# pandashield12-lga.net
KiCad netlist of a schematic drawn in EAGLE
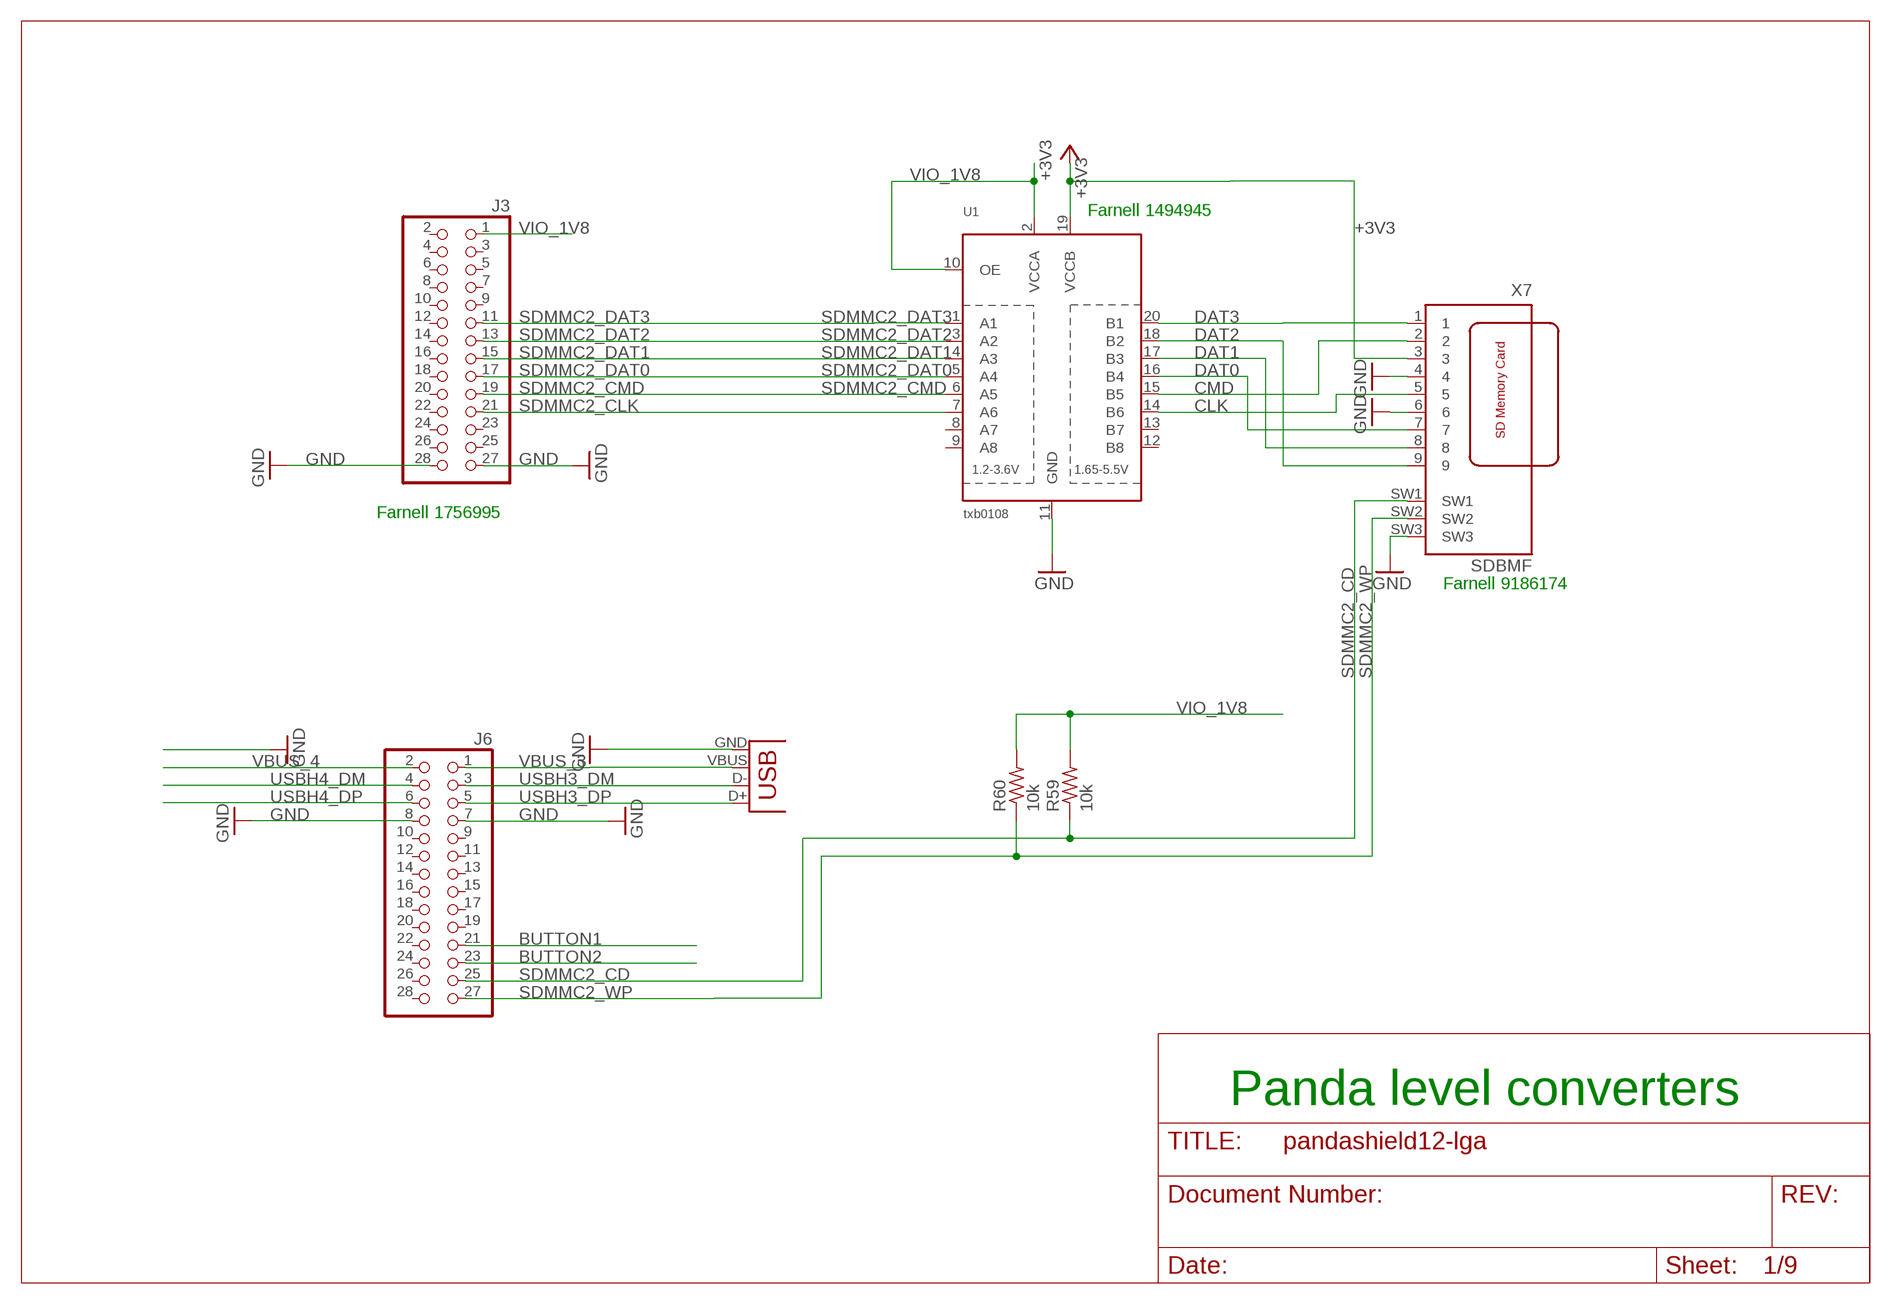
[diagram p0: schematic, sheet 1]
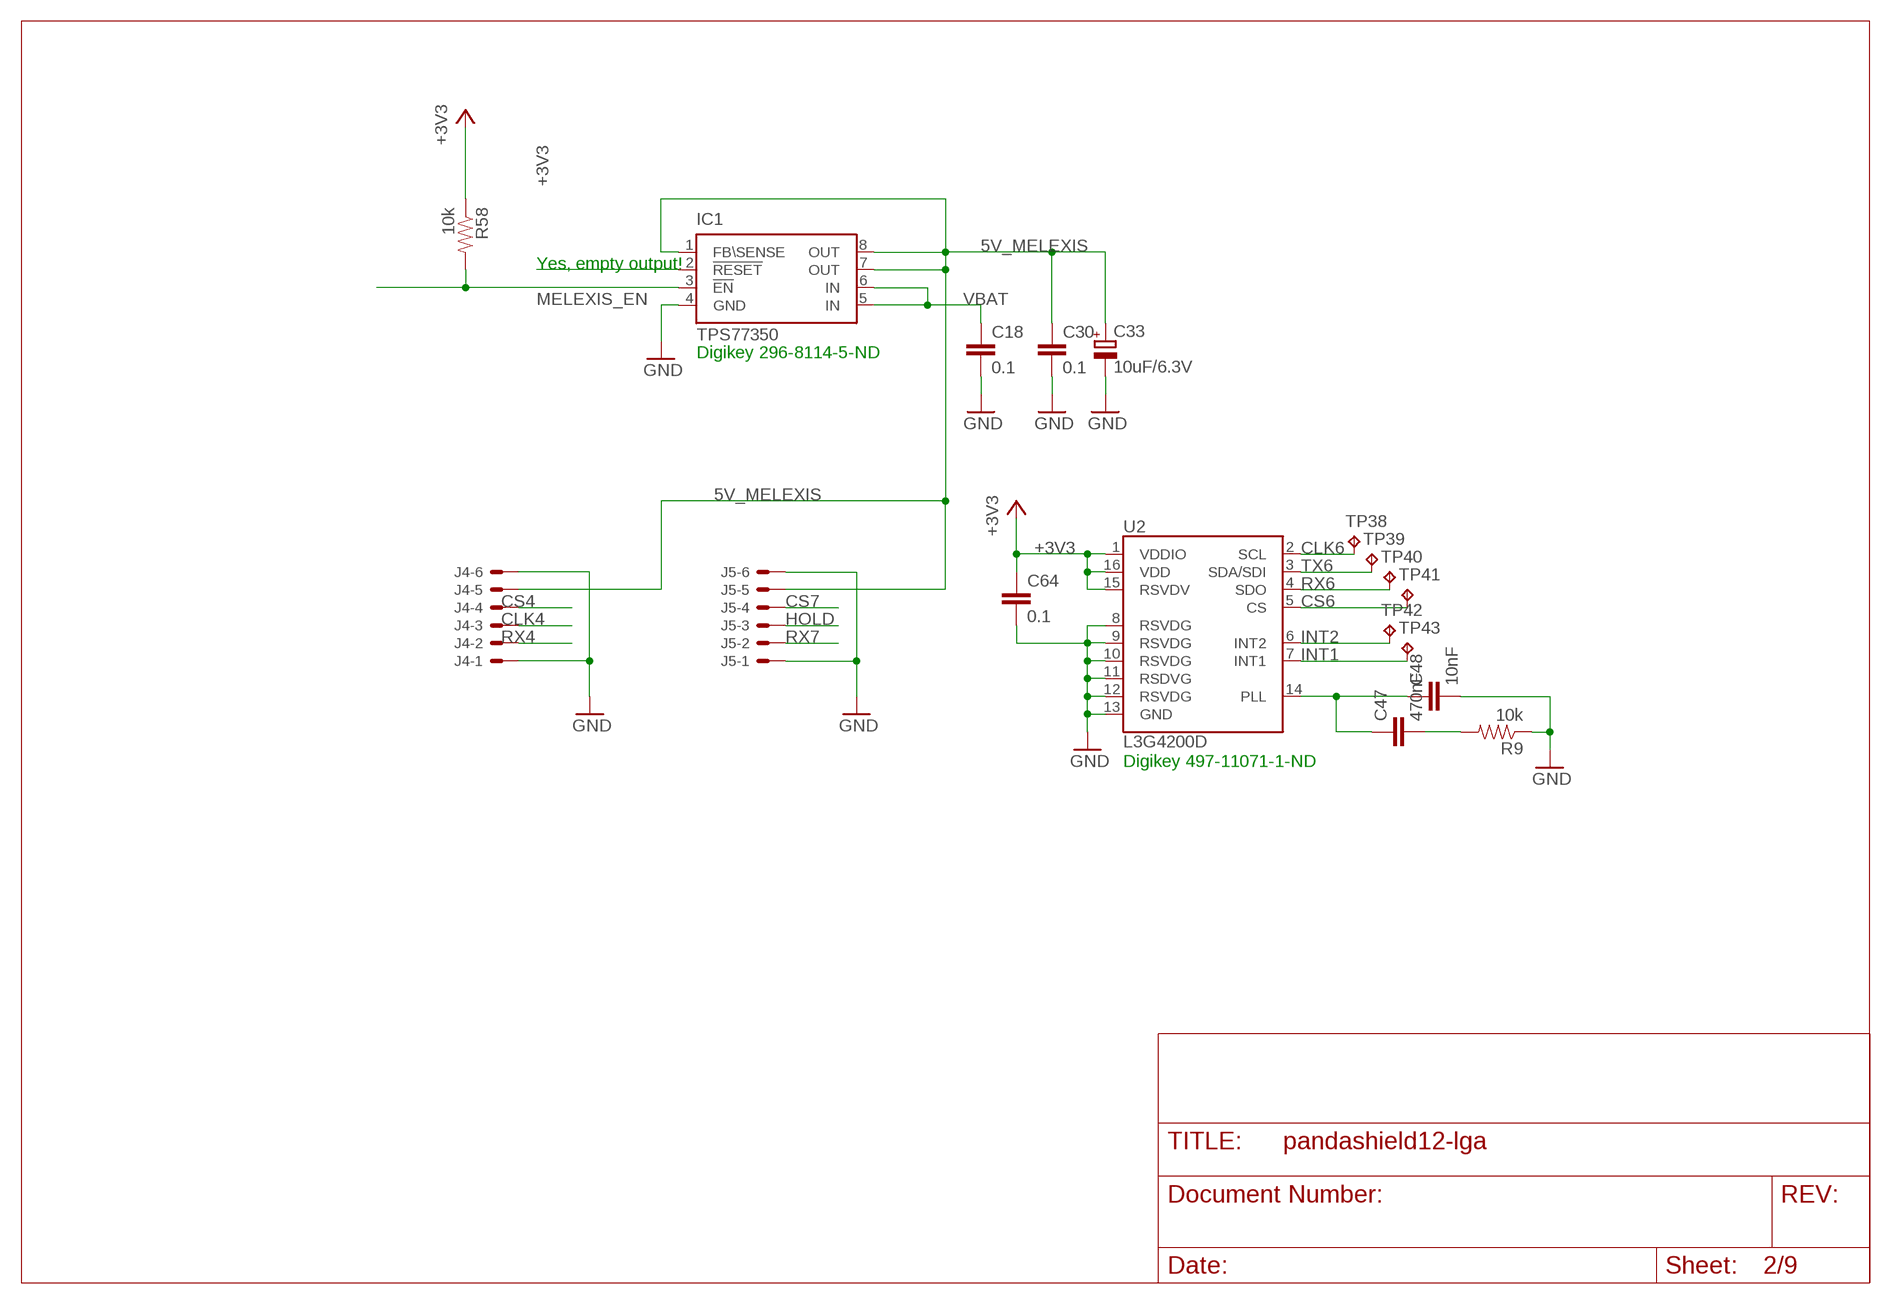
[diagram p1: schematic, sheet 2]
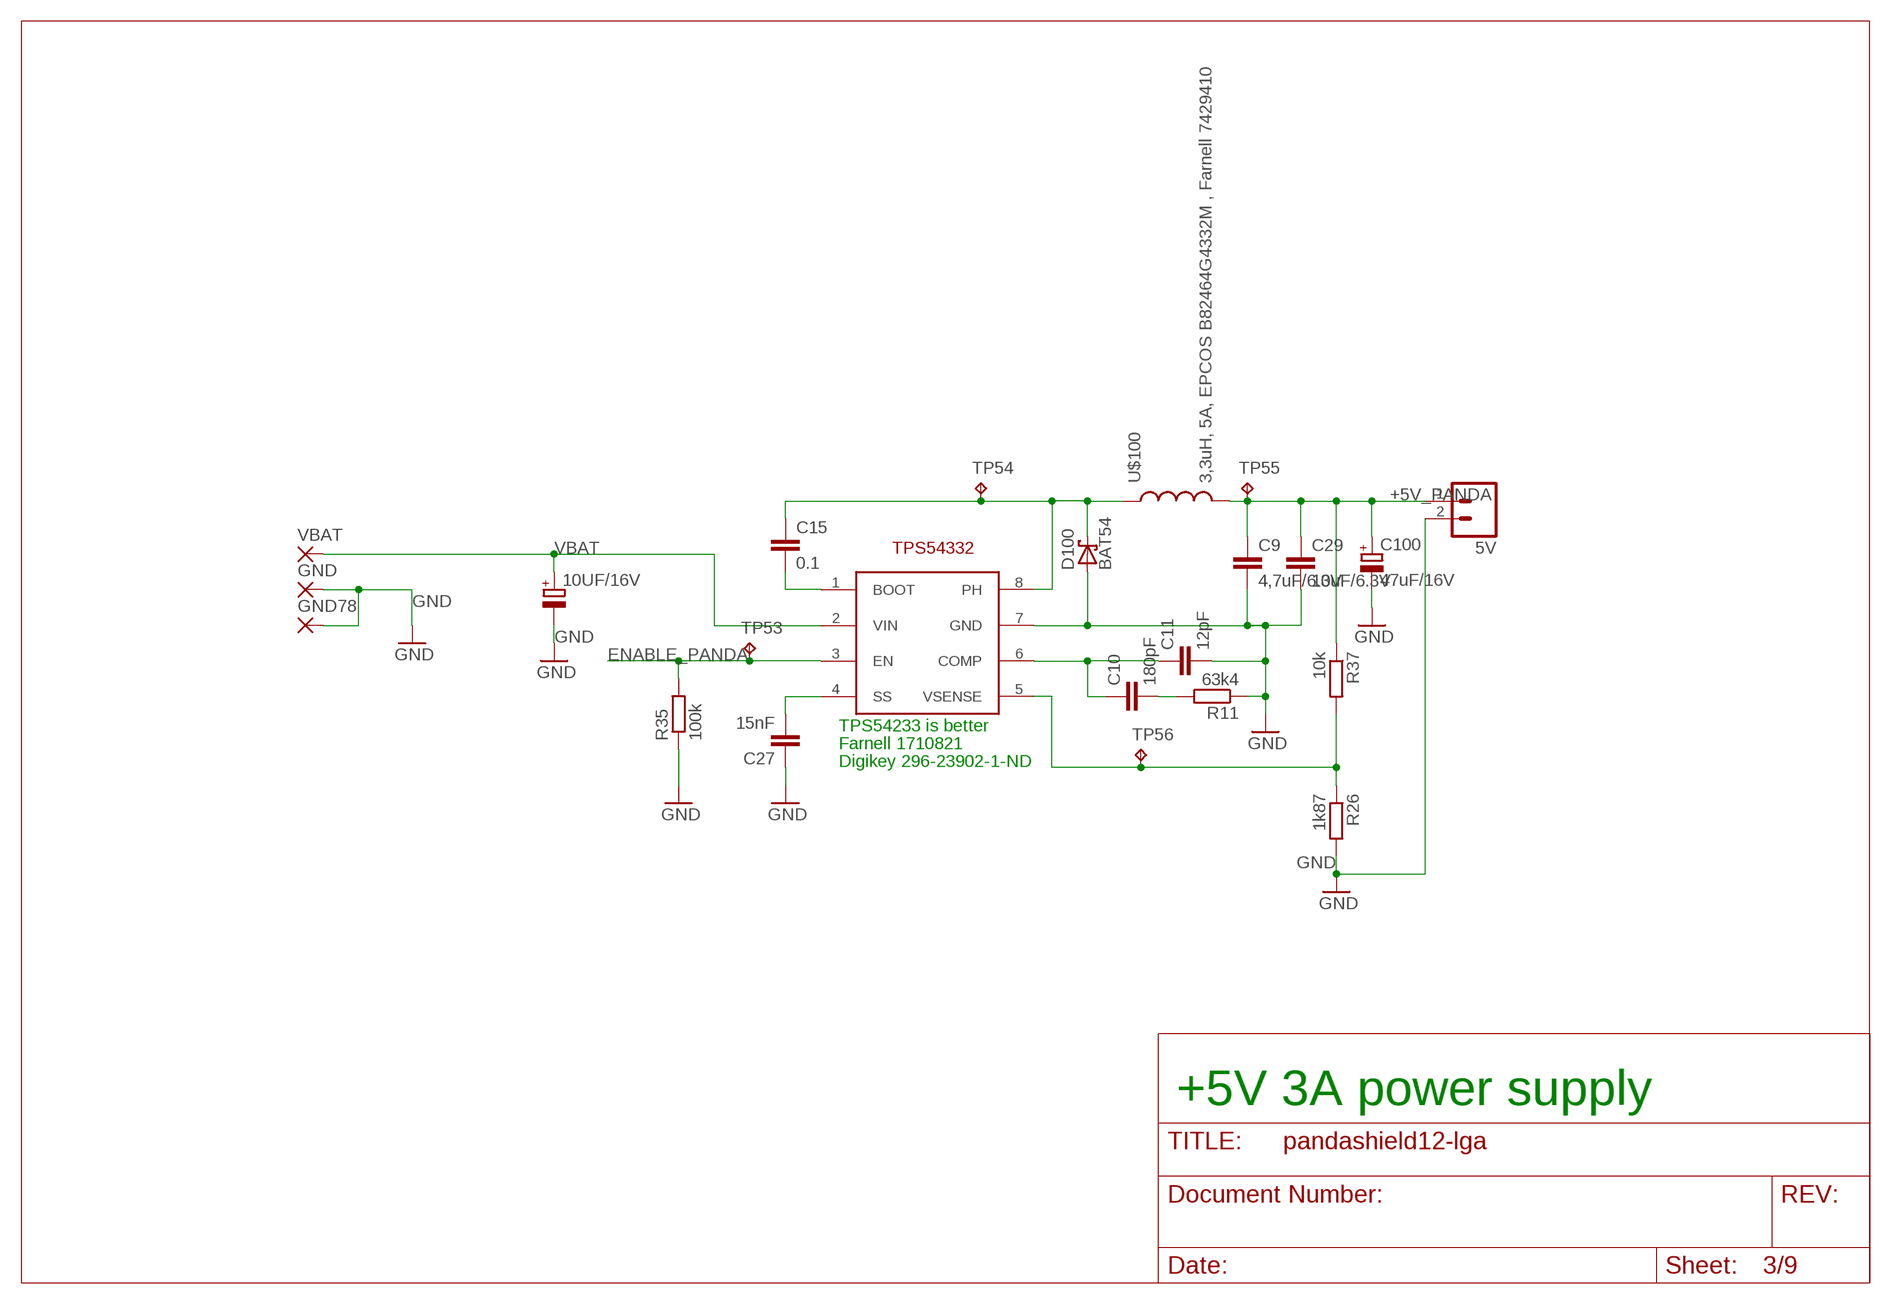
[diagram p2: schematic, sheet 3]
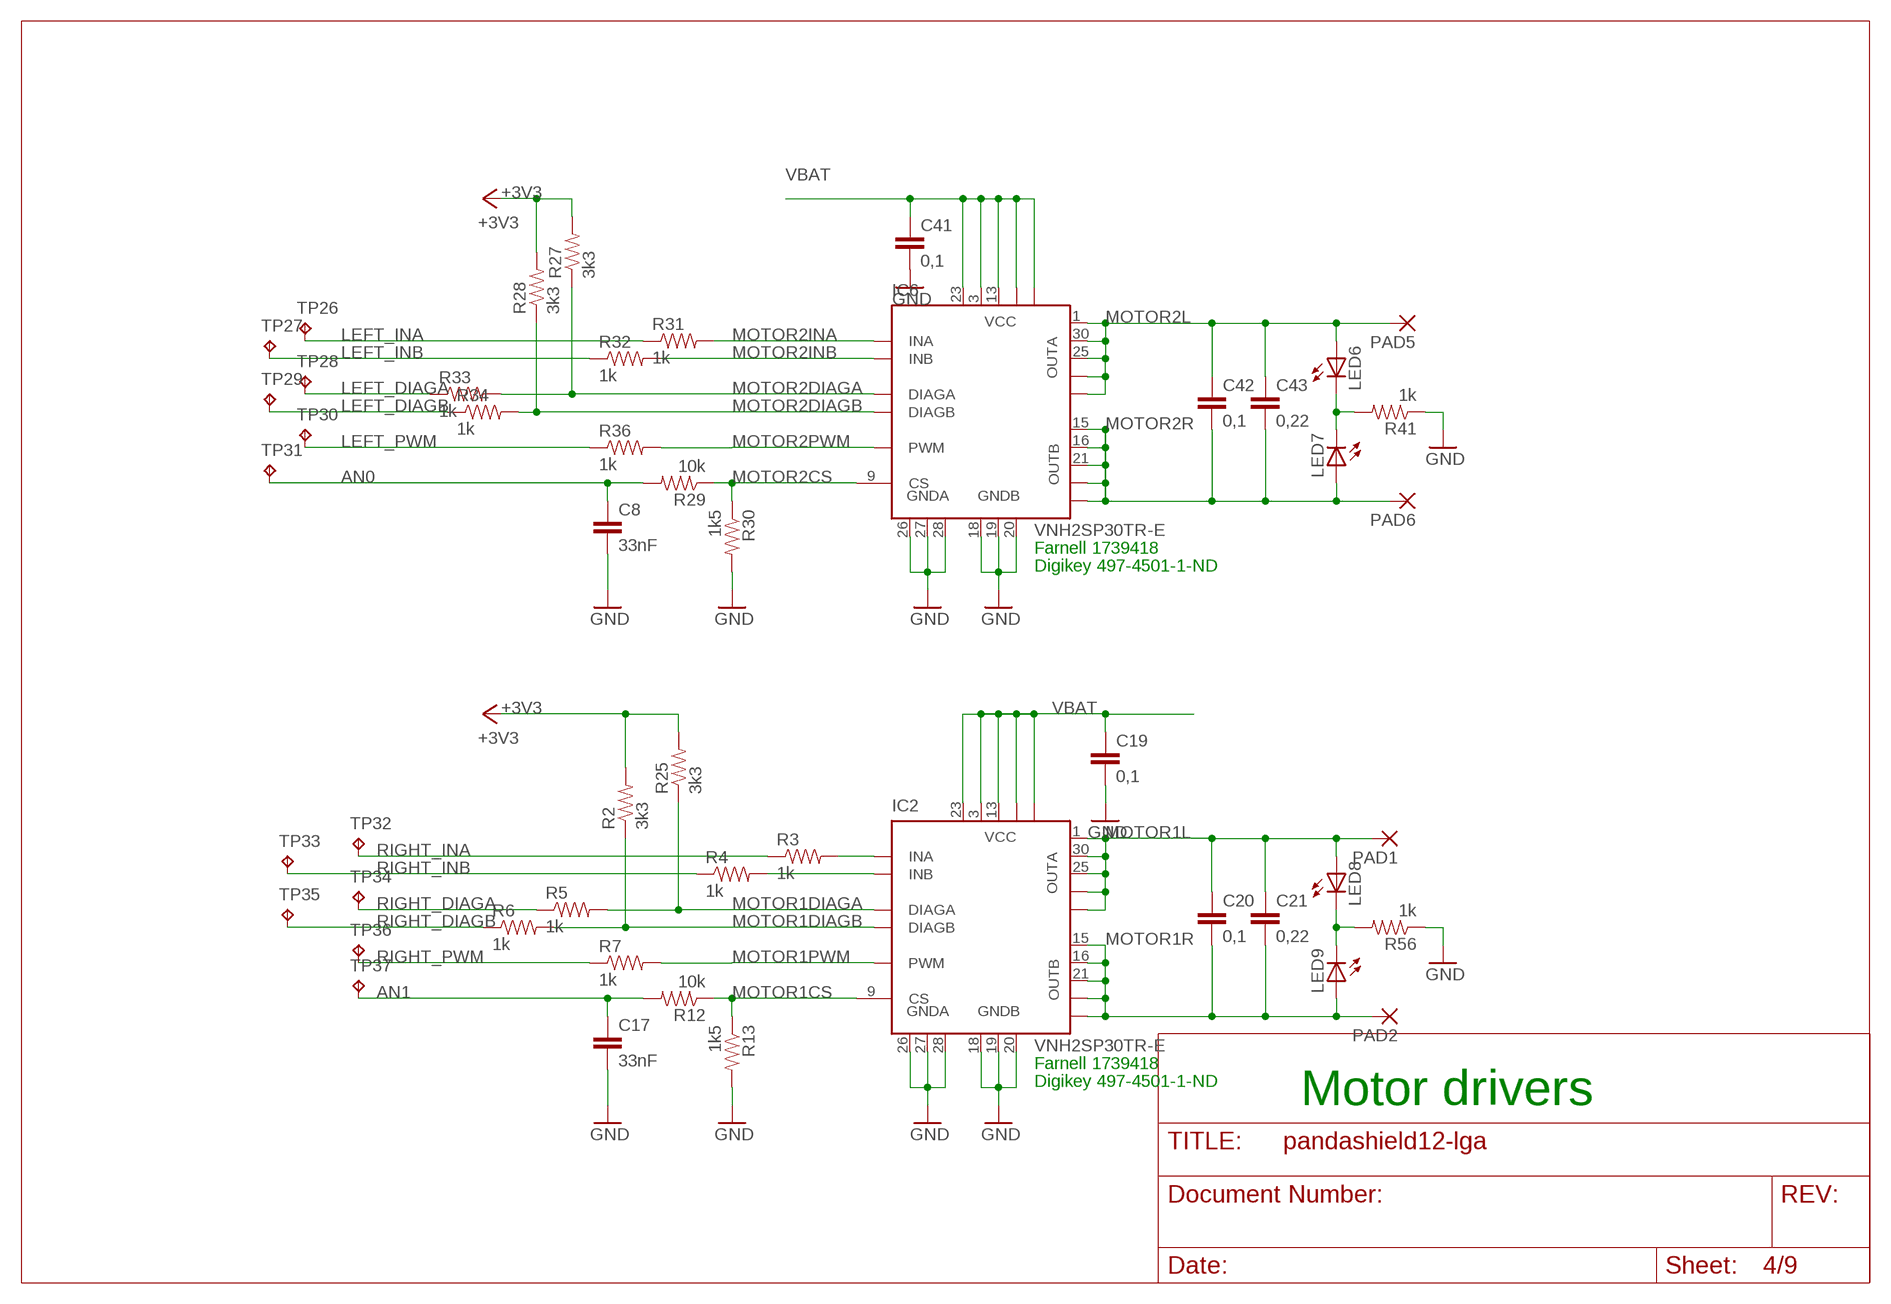
[diagram p3: schematic, sheet 4]
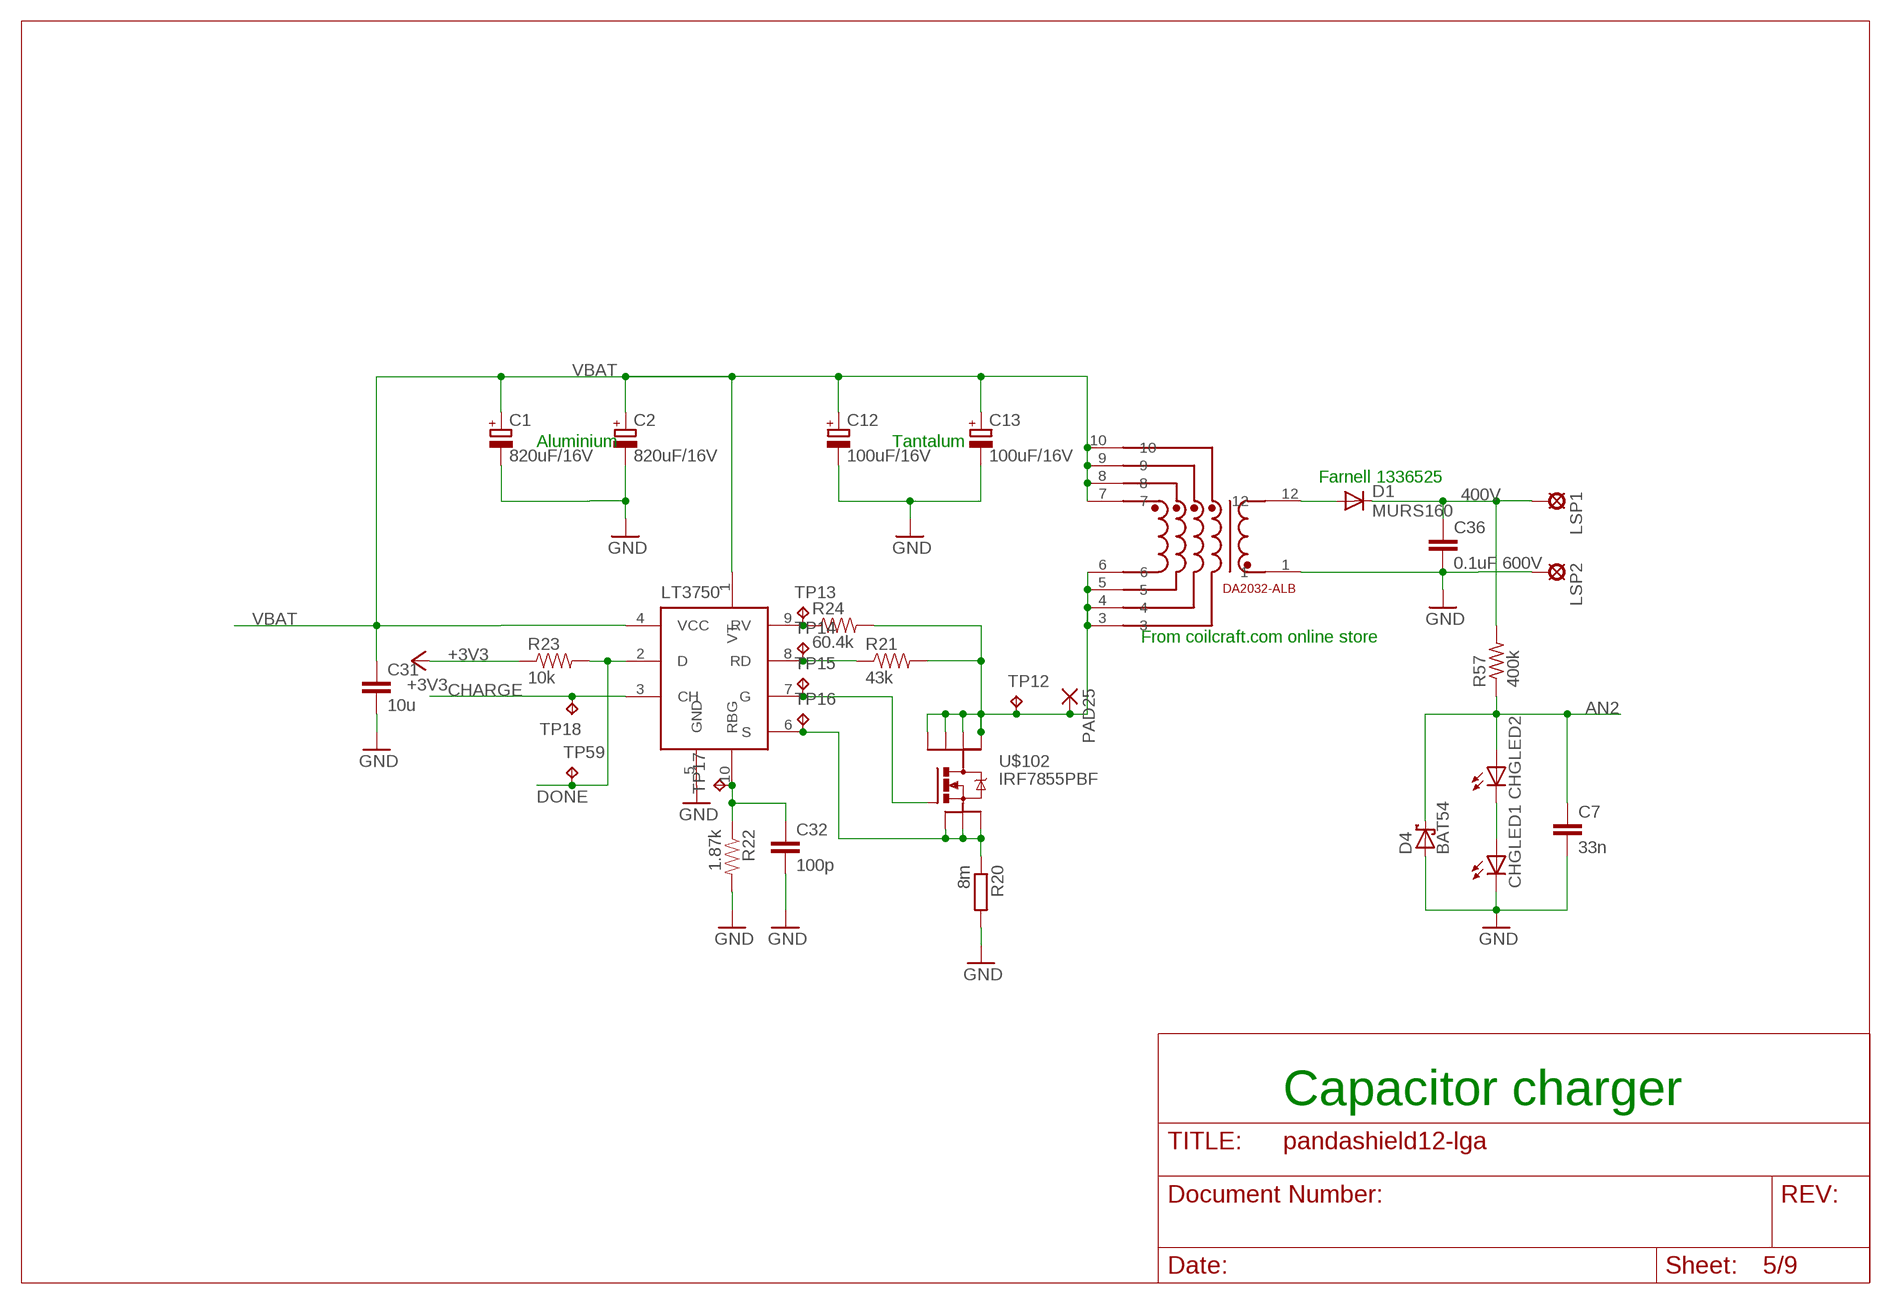
[diagram p4: schematic, sheet 5]
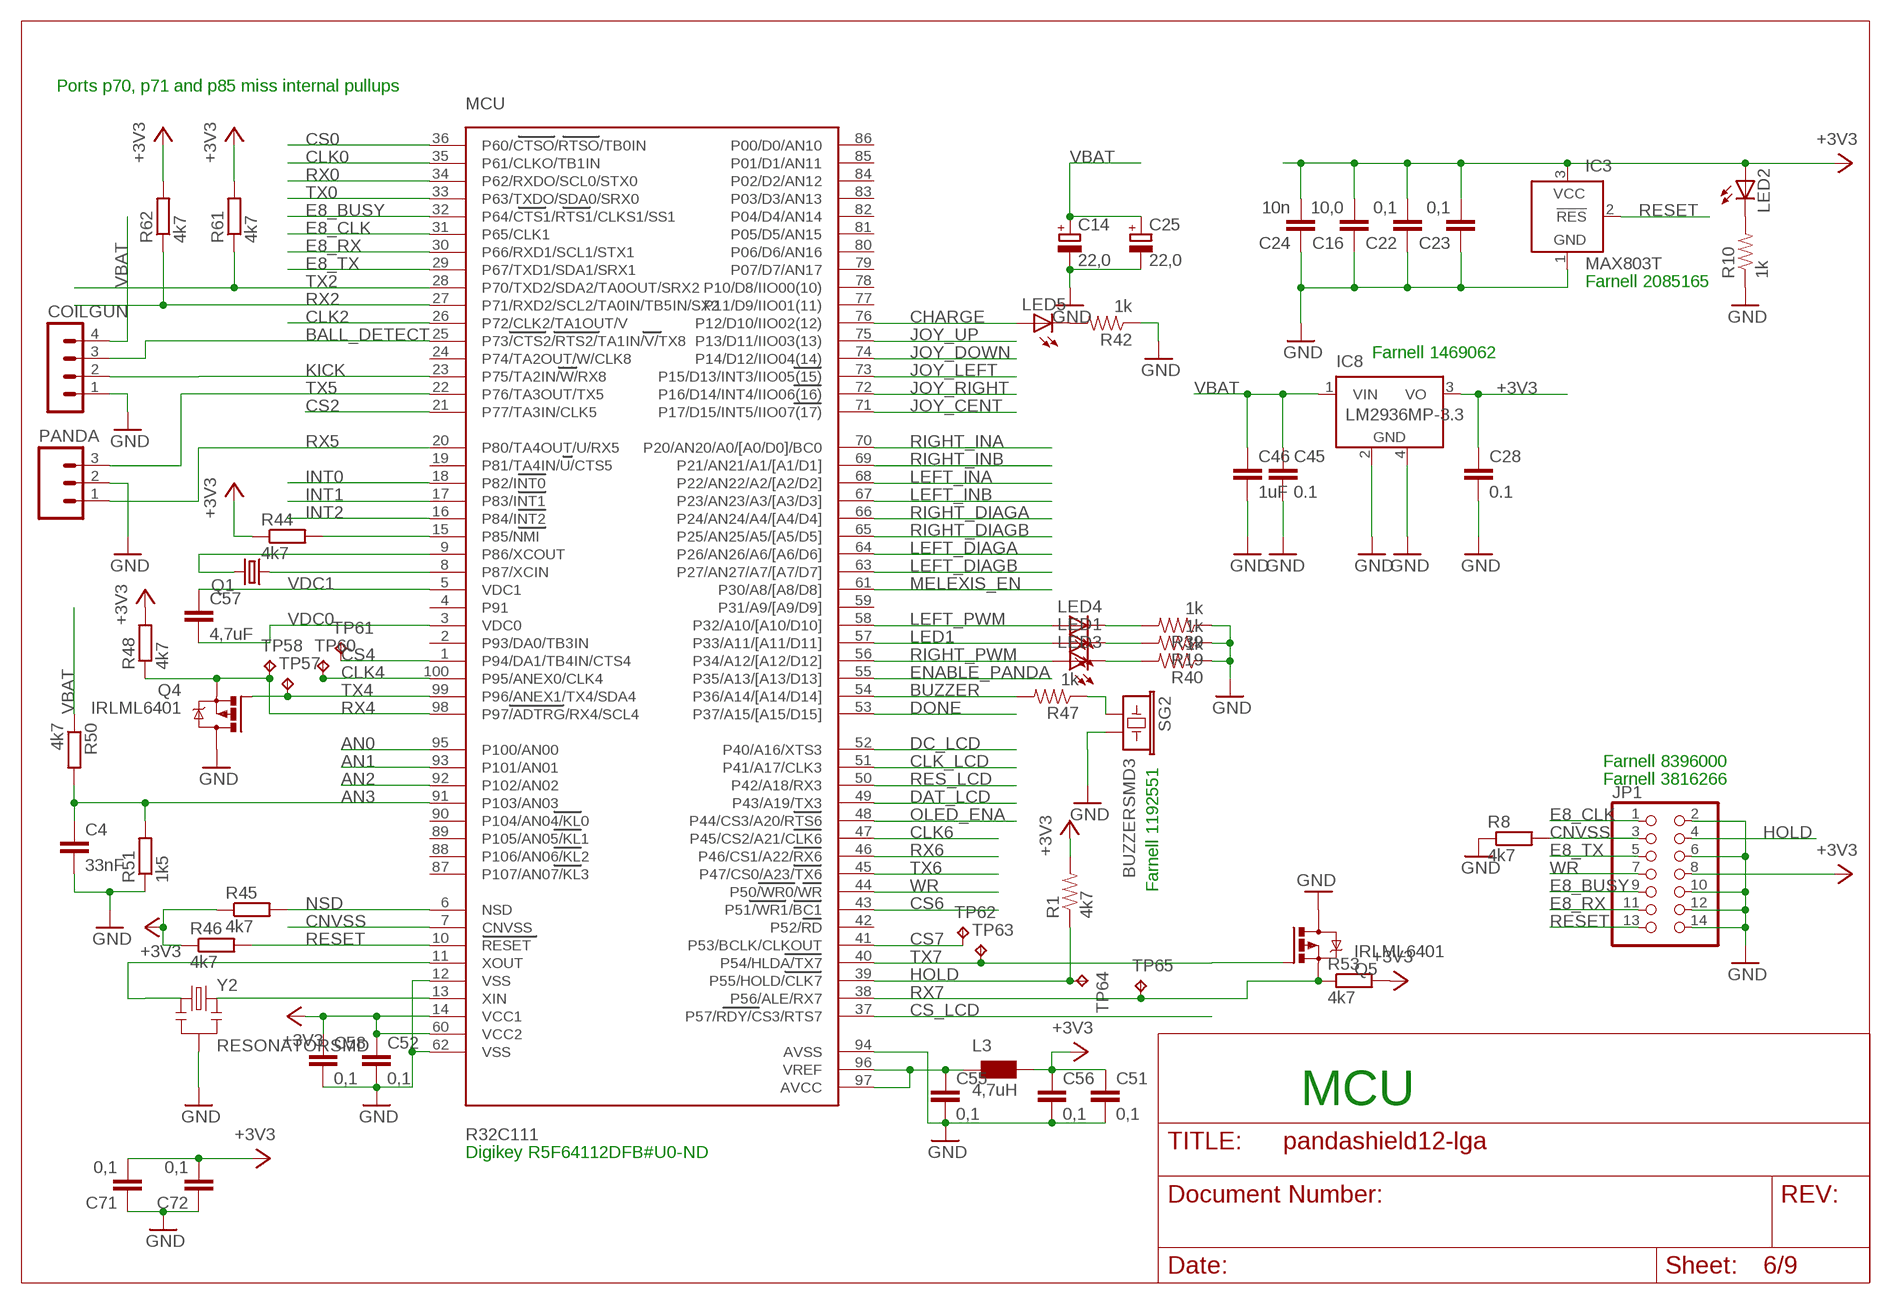
[diagram p5: schematic, sheet 6]
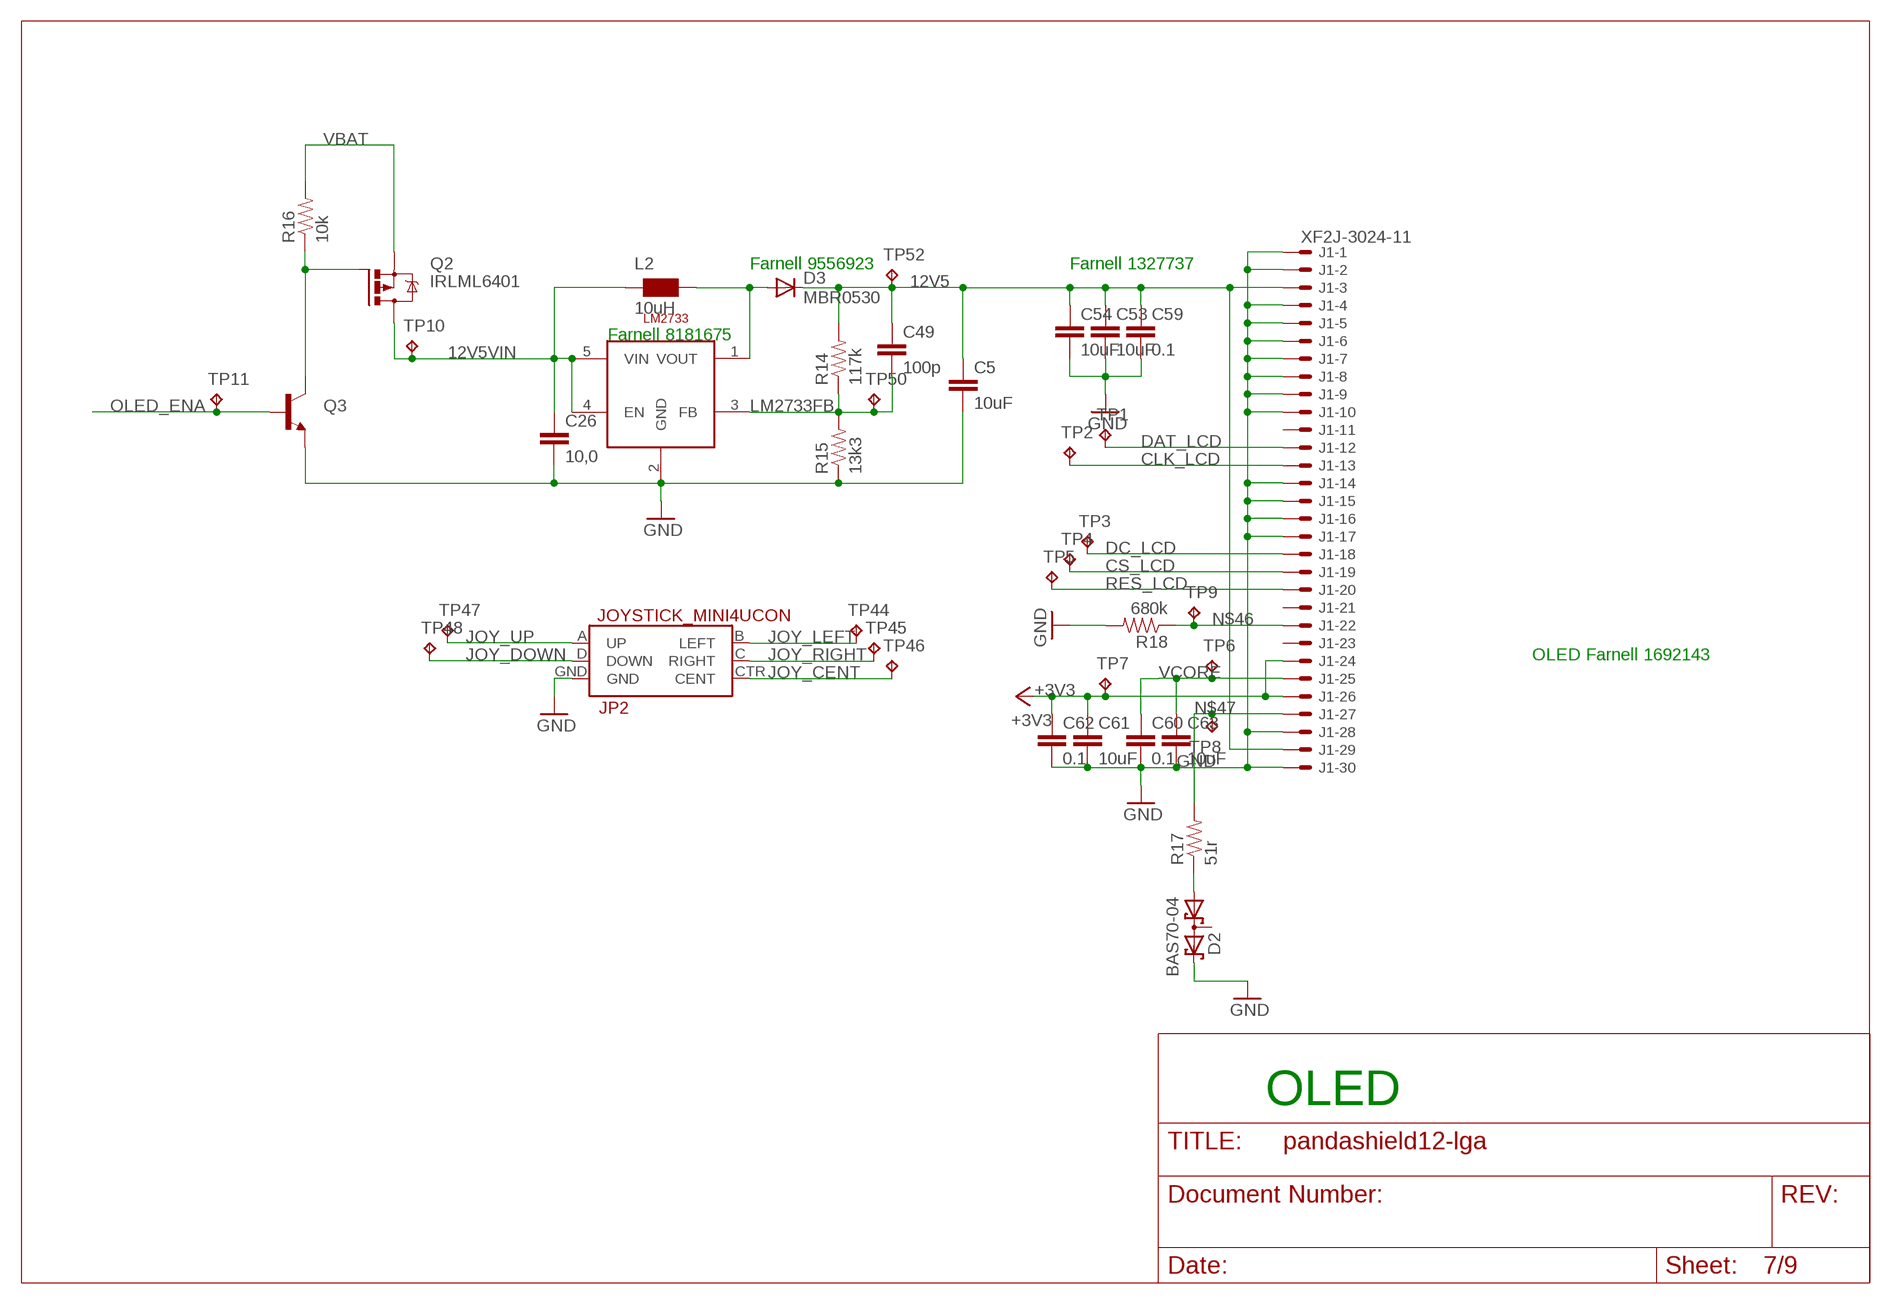
[diagram p6: schematic, sheet 7]
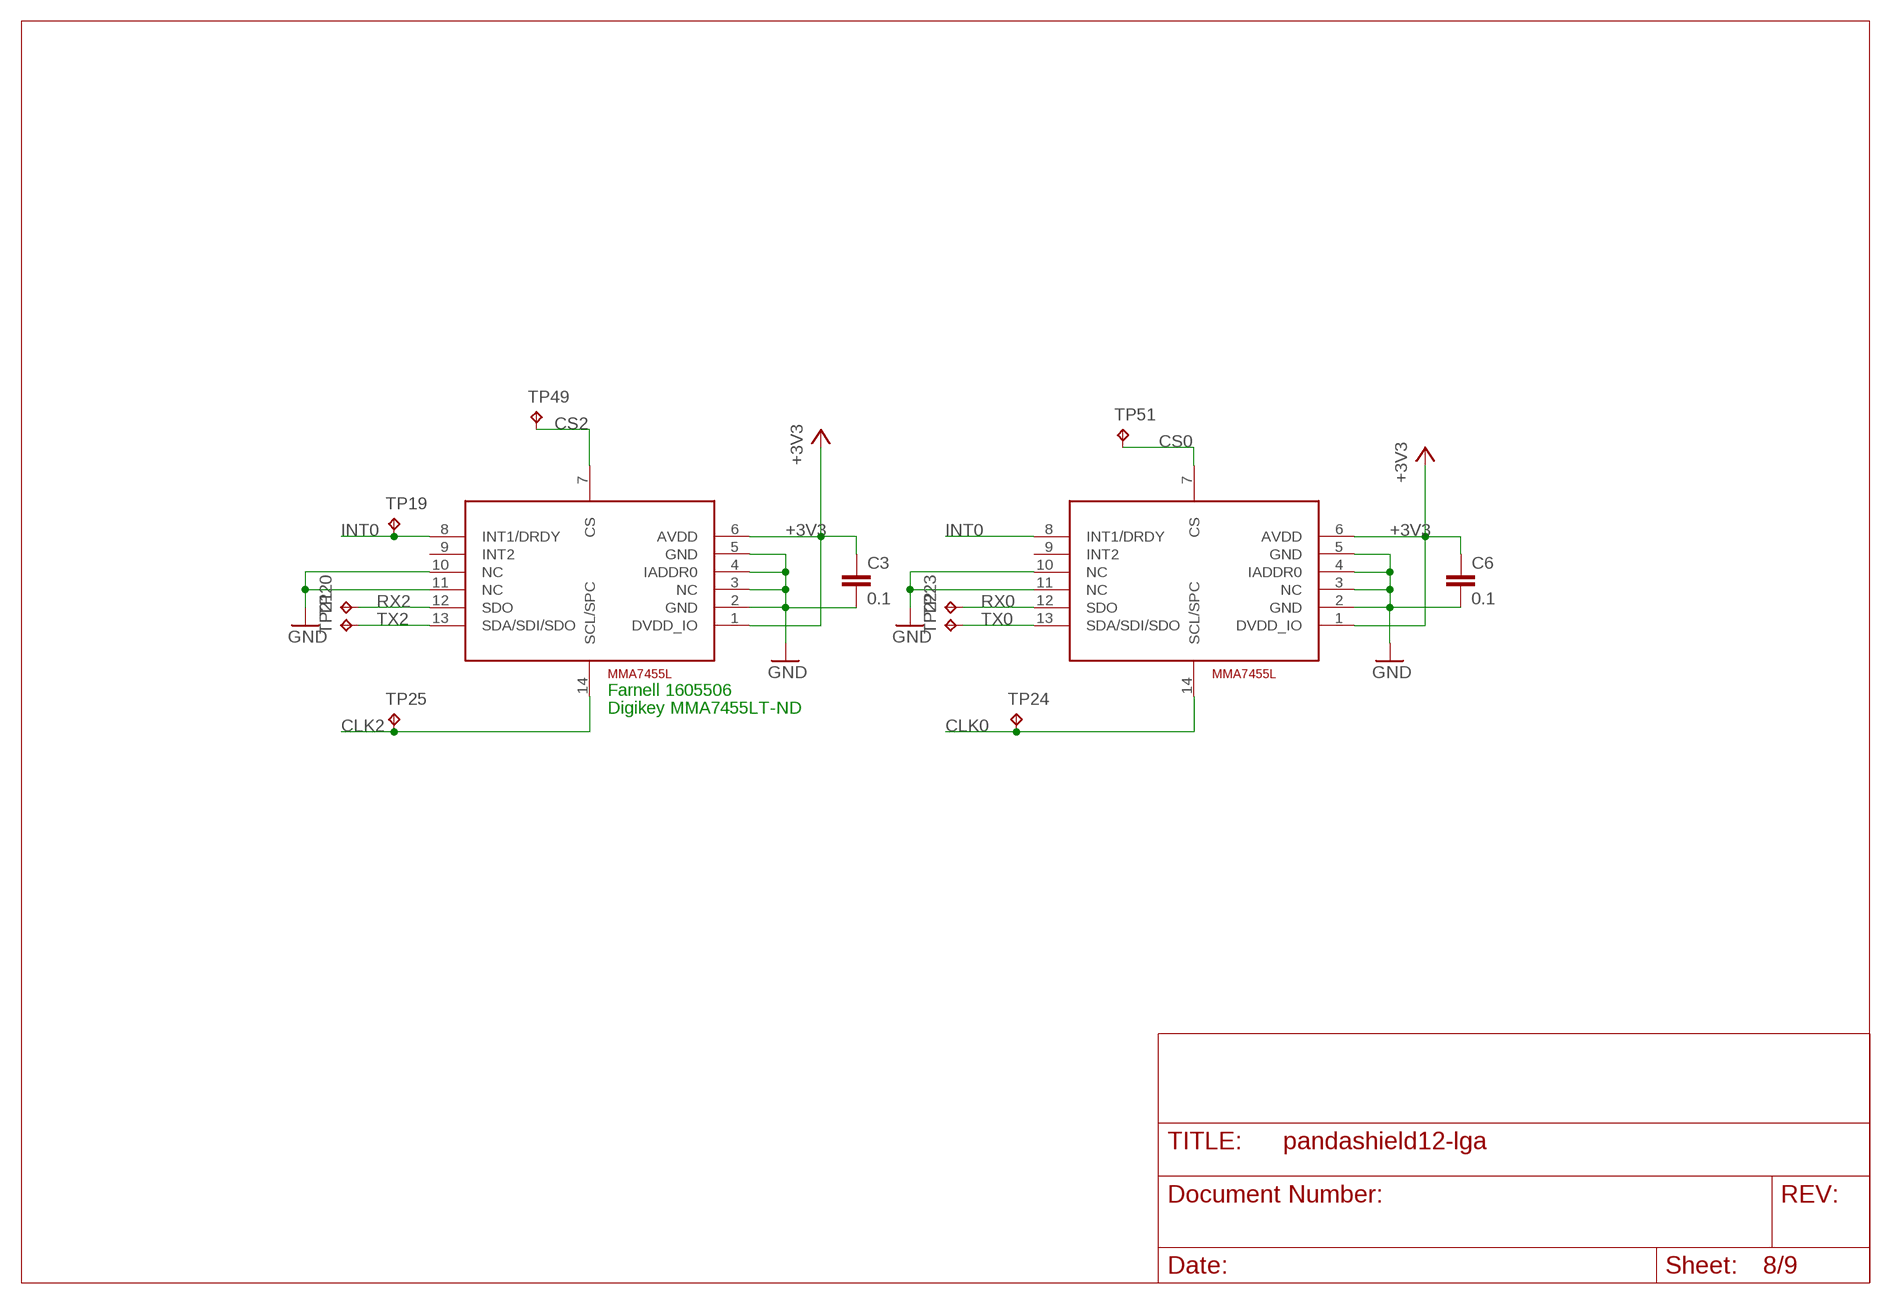
[diagram p7: schematic, sheet 8]
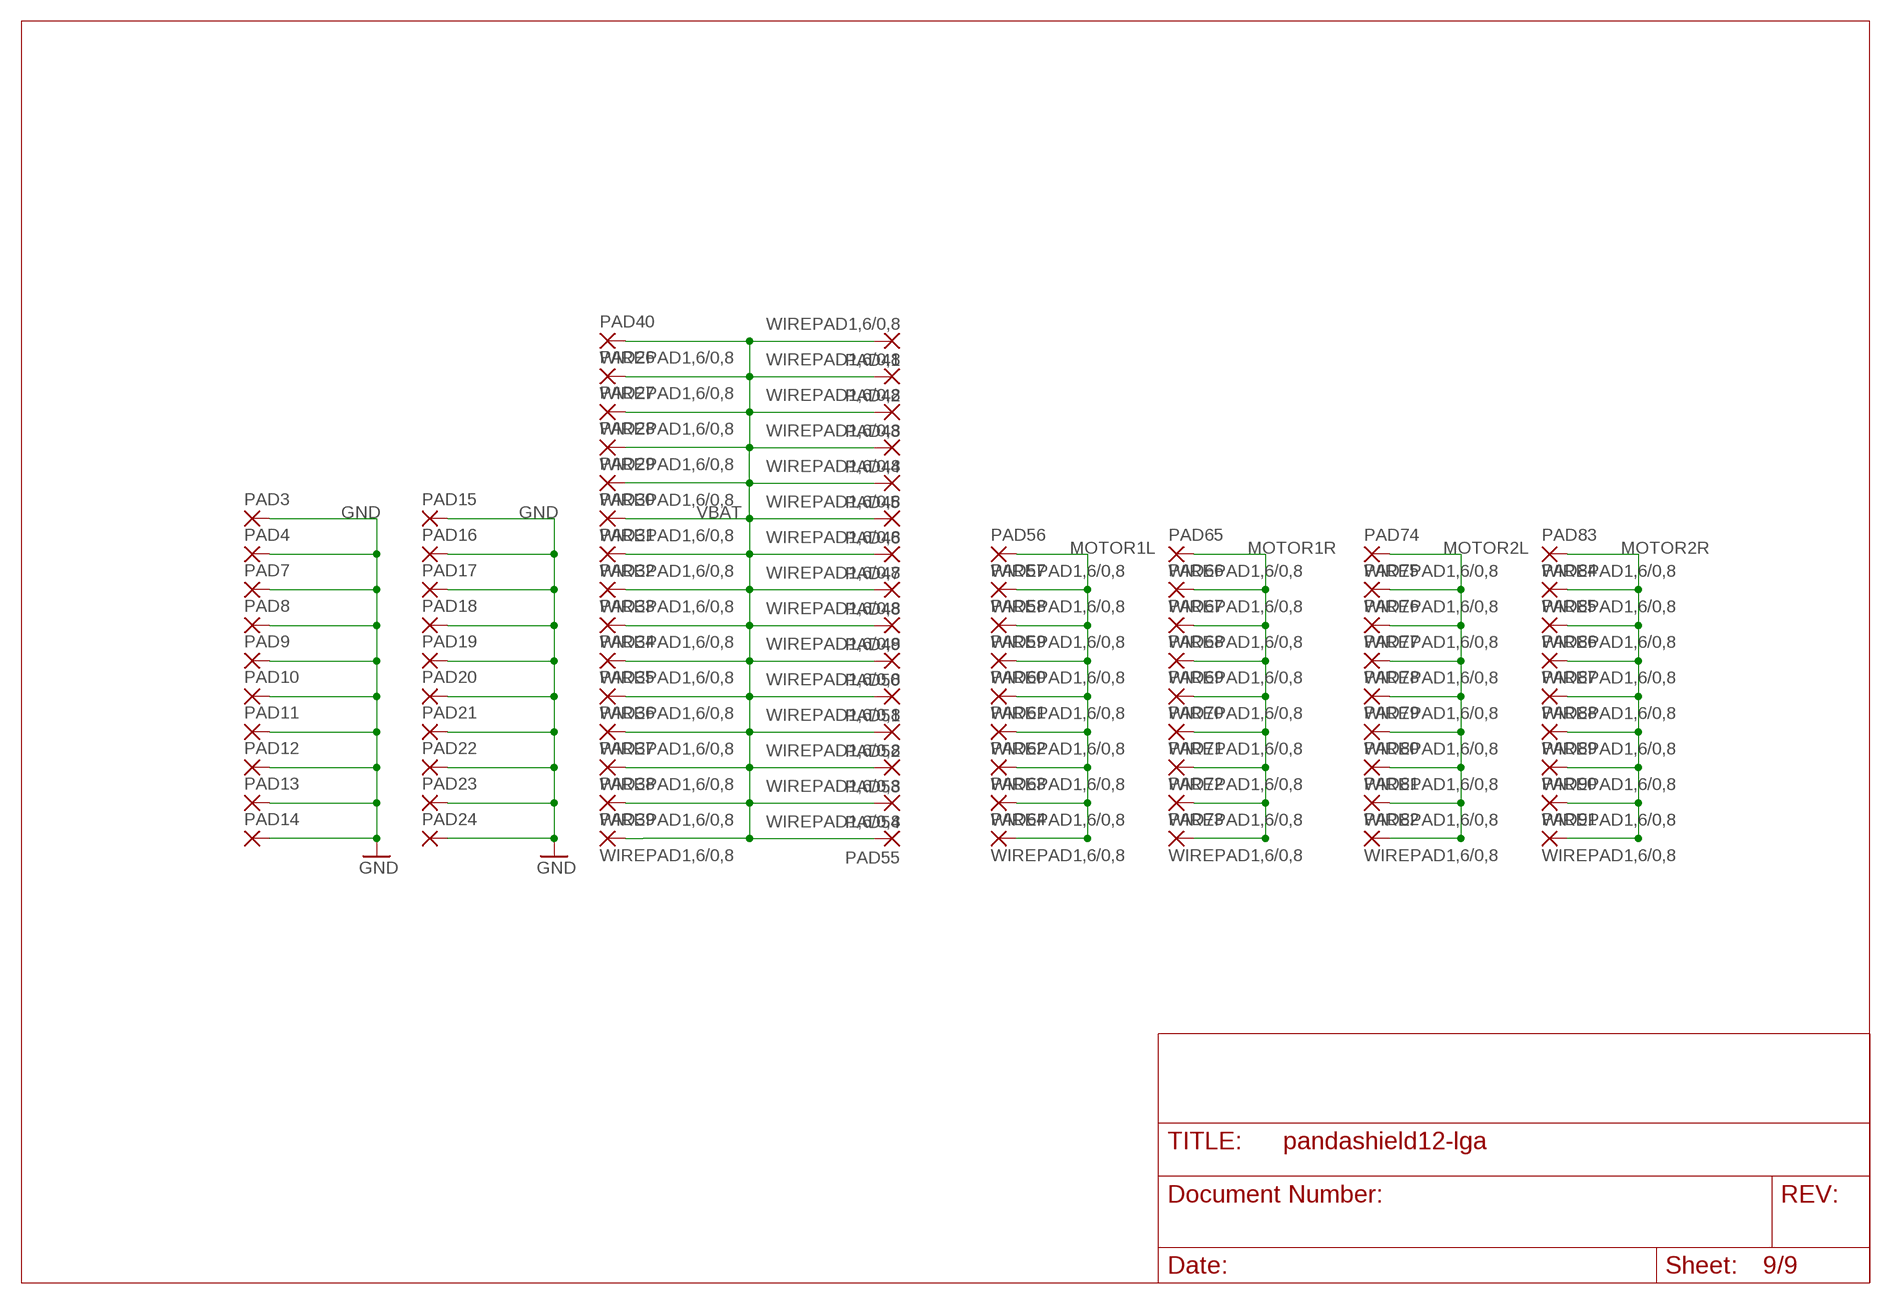
[diagram p8: schematic, sheet 9]

(export (version "E")
  (design (tool "Eeschema 10.0.6"))
  (components
    (comp (ref "C8")
      (value "33nF")
      (footprint "eagle-import:0603-CAP")
      (libsource (lib "eagle-import") (part "CAP0603-CAP"))
    )
    (comp (ref "C17")
      (value "33nF")
      (footprint "eagle-import:0603-CAP")
      (libsource (lib "eagle-import") (part "CAP0603-CAP"))
    )
    (comp (ref "C19")
      (value "0,1")
      (footprint "eagle-import:0603-CAP")
      (libsource (lib "eagle-import") (part "CAP0603-CAP"))
    )
    (comp (ref "C20")
      (value "0,1")
      (footprint "eagle-import:0603-CAP")
      (libsource (lib "eagle-import") (part "CAP0603-CAP"))
    )
    (comp (ref "C21")
      (value "0,22")
      (footprint "eagle-import:0603-CAP")
      (libsource (lib "eagle-import") (part "CAP0603-CAP"))
    )
    (comp (ref "C41")
      (value "0,1")
      (footprint "eagle-import:0603-CAP")
      (libsource (lib "eagle-import") (part "CAP0603-CAP"))
    )
    (comp (ref "C42")
      (value "0,1")
      (footprint "eagle-import:0603-CAP")
      (libsource (lib "eagle-import") (part "CAP0603-CAP"))
    )
    (comp (ref "C43")
      (value "0,22")
      (footprint "eagle-import:0603-CAP")
      (libsource (lib "eagle-import") (part "CAP0603-CAP"))
    )
    (comp (ref "IC2")
      (value "VNH2SP30TR-E")
      (footprint "eagle-import:MULTIPOWERSO-30")
      (libsource (lib "eagle-import") (part "VNH3ASP30-E"))
    )
    (comp (ref "IC6")
      (value "VNH2SP30TR-E")
      (footprint "eagle-import:MULTIPOWERSO-30")
      (libsource (lib "eagle-import") (part "VNH3ASP30-E"))
    )
    (comp (ref "LED6")
      (value "LEDCHIP-LED0603")
      (footprint "eagle-import:CHIP-LED0603")
      (libsource (lib "eagle-import") (part "LEDCHIP-LED0603"))
    )
    (comp (ref "LED7")
      (value "LEDCHIP-LED0603")
      (footprint "eagle-import:CHIP-LED0603")
      (libsource (lib "eagle-import") (part "LEDCHIP-LED0603"))
    )
    (comp (ref "LED8")
      (value "LEDCHIP-LED0603")
      (footprint "eagle-import:CHIP-LED0603")
      (libsource (lib "eagle-import") (part "LEDCHIP-LED0603"))
    )
    (comp (ref "LED9")
      (value "LEDCHIP-LED0603")
      (footprint "eagle-import:CHIP-LED0603")
      (libsource (lib "eagle-import") (part "LEDCHIP-LED0603"))
    )
    (comp (ref "PAD1")
      (value "3,81/1,4")
      (footprint "eagle-import:3,81_1,4")
      (libsource (lib "eagle-import") (part "3,81/1,4"))
    )
    (comp (ref "PAD2")
      (value "3,81/1,4")
      (footprint "eagle-import:3,81_1,4")
      (libsource (lib "eagle-import") (part "3,81/1,4"))
    )
    (comp (ref "PAD5")
      (value "3,81/1,4")
      (footprint "eagle-import:3,81_1,4")
      (libsource (lib "eagle-import") (part "3,81/1,4"))
    )
    (comp (ref "PAD6")
      (value "3,81/1,4")
      (footprint "eagle-import:3,81_1,4")
      (libsource (lib "eagle-import") (part "3,81/1,4"))
    )
    (comp (ref "R2")
      (value "3k3")
      (footprint "eagle-import:0603-RES")
      (libsource (lib "eagle-import") (part "RESISTOR0603-RES"))
    )
    (comp (ref "R3")
      (value "1k")
      (footprint "eagle-import:0603-RES")
      (libsource (lib "eagle-import") (part "RESISTOR0603-RES"))
    )
    (comp (ref "R4")
      (value "1k")
      (footprint "eagle-import:0603-RES")
      (libsource (lib "eagle-import") (part "RESISTOR0603-RES"))
    )
    (comp (ref "R5")
      (value "1k")
      (footprint "eagle-import:0603-RES")
      (libsource (lib "eagle-import") (part "RESISTOR0603-RES"))
    )
    (comp (ref "R6")
      (value "1k")
      (footprint "eagle-import:0603-RES")
      (libsource (lib "eagle-import") (part "RESISTOR0603-RES"))
    )
    (comp (ref "R7")
      (value "1k")
      (footprint "eagle-import:0603-RES")
      (libsource (lib "eagle-import") (part "RESISTOR0603-RES"))
    )
    (comp (ref "R12")
      (value "10k")
      (footprint "eagle-import:0603-RES")
      (libsource (lib "eagle-import") (part "RESISTOR0603-RES"))
    )
    (comp (ref "R13")
      (value "1k5")
      (footprint "eagle-import:0603-RES")
      (libsource (lib "eagle-import") (part "RESISTOR0603-RES"))
    )
    (comp (ref "R25")
      (value "3k3")
      (footprint "eagle-import:0603-RES")
      (libsource (lib "eagle-import") (part "RESISTOR0603-RES"))
    )
    (comp (ref "R27")
      (value "3k3")
      (footprint "eagle-import:0603-RES")
      (libsource (lib "eagle-import") (part "RESISTOR0603-RES"))
    )
    (comp (ref "R28")
      (value "3k3")
      (footprint "eagle-import:0603-RES")
      (libsource (lib "eagle-import") (part "RESISTOR0603-RES"))
    )
    (comp (ref "R29")
      (value "10k")
      (footprint "eagle-import:0603-RES")
      (libsource (lib "eagle-import") (part "RESISTOR0603-RES"))
    )
    (comp (ref "R30")
      (value "1k5")
      (footprint "eagle-import:0603-RES")
      (libsource (lib "eagle-import") (part "RESISTOR0603-RES"))
    )
    (comp (ref "R31")
      (value "1k")
      (footprint "eagle-import:0603-RES")
      (libsource (lib "eagle-import") (part "RESISTOR0603-RES"))
    )
    (comp (ref "R32")
      (value "1k")
      (footprint "eagle-import:0603-RES")
      (libsource (lib "eagle-import") (part "RESISTOR0603-RES"))
    )
    (comp (ref "R33")
      (value "1k")
      (footprint "eagle-import:0603-RES")
      (libsource (lib "eagle-import") (part "RESISTOR0603-RES"))
    )
    (comp (ref "R34")
      (value "1k")
      (footprint "eagle-import:0603-RES")
      (libsource (lib "eagle-import") (part "RESISTOR0603-RES"))
    )
    (comp (ref "R36")
      (value "1k")
      (footprint "eagle-import:0603-RES")
      (libsource (lib "eagle-import") (part "RESISTOR0603-RES"))
    )
    (comp (ref "R41")
      (value "1k")
      (footprint "eagle-import:0603-RES")
      (libsource (lib "eagle-import") (part "RESISTOR0603-RES"))
    )
    (comp (ref "R56")
      (value "1k")
      (footprint "eagle-import:0603-RES")
      (libsource (lib "eagle-import") (part "RESISTOR0603-RES"))
    )
    (comp (ref "TP26")
      (value "TPB1,27")
      (footprint "eagle-import:B1,27")
      (libsource (lib "eagle-import") (part "TPB1,27"))
    )
    (comp (ref "TP27")
      (value "TPB1,27")
      (footprint "eagle-import:B1,27")
      (libsource (lib "eagle-import") (part "TPB1,27"))
    )
    (comp (ref "TP28")
      (value "TPB1,27")
      (footprint "eagle-import:B1,27")
      (libsource (lib "eagle-import") (part "TPB1,27"))
    )
    (comp (ref "TP29")
      (value "TPB1,27")
      (footprint "eagle-import:B1,27")
      (libsource (lib "eagle-import") (part "TPB1,27"))
    )
    (comp (ref "TP30")
      (value "TPB1,27")
      (footprint "eagle-import:B1,27")
      (libsource (lib "eagle-import") (part "TPB1,27"))
    )
    (comp (ref "TP31")
      (value "TPB1,27")
      (footprint "eagle-import:B1,27")
      (libsource (lib "eagle-import") (part "TPB1,27"))
    )
    (comp (ref "TP32")
      (value "TPB1,27")
      (footprint "eagle-import:B1,27")
      (libsource (lib "eagle-import") (part "TPB1,27"))
    )
    (comp (ref "TP33")
      (value "TPB1,27")
      (footprint "eagle-import:B1,27")
      (libsource (lib "eagle-import") (part "TPB1,27"))
    )
    (comp (ref "TP34")
      (value "TPB1,27")
      (footprint "eagle-import:B1,27")
      (libsource (lib "eagle-import") (part "TPB1,27"))
    )
    (comp (ref "TP35")
      (value "TPB1,27")
      (footprint "eagle-import:B1,27")
      (libsource (lib "eagle-import") (part "TPB1,27"))
    )
    (comp (ref "TP36")
      (value "TPB1,27")
      (footprint "eagle-import:B1,27")
      (libsource (lib "eagle-import") (part "TPB1,27"))
    )
    (comp (ref "TP37")
      (value "TPB1,27")
      (footprint "eagle-import:B1,27")
      (libsource (lib "eagle-import") (part "TPB1,27"))
    )
    (comp (ref "C3")
      (value "0.1")
      (footprint "eagle-import:0603-CAP")
      (libsource (lib "eagle-import") (part "CAP0603-CAP"))
    )
    (comp (ref "C6")
      (value "0.1")
      (footprint "eagle-import:0603-CAP")
      (libsource (lib "eagle-import") (part "CAP0603-CAP"))
    )
    (comp (ref "TP19")
      (value "TPB1,27")
      (footprint "eagle-import:B1,27")
      (libsource (lib "eagle-import") (part "TPB1,27"))
    )
    (comp (ref "TP20")
      (value "TPB1,27")
      (footprint "eagle-import:B1,27")
      (libsource (lib "eagle-import") (part "TPB1,27"))
    )
    (comp (ref "TP21")
      (value "TPB1,27")
      (footprint "eagle-import:B1,27")
      (libsource (lib "eagle-import") (part "TPB1,27"))
    )
    (comp (ref "TP22")
      (value "TPB1,27")
      (footprint "eagle-import:B1,27")
      (libsource (lib "eagle-import") (part "TPB1,27"))
    )
    (comp (ref "TP23")
      (value "TPB1,27")
      (footprint "eagle-import:B1,27")
      (libsource (lib "eagle-import") (part "TPB1,27"))
    )
    (comp (ref "TP24")
      (value "TPB1,27")
      (footprint "eagle-import:B1,27")
      (libsource (lib "eagle-import") (part "TPB1,27"))
    )
    (comp (ref "TP25")
      (value "TPB1,27")
      (footprint "eagle-import:B1,27")
      (libsource (lib "eagle-import") (part "TPB1,27"))
    )
    (comp (ref "TP49")
      (value "TPB1,27")
      (footprint "eagle-import:B1,27")
      (libsource (lib "eagle-import") (part "TPB1,27"))
    )
    (comp (ref "TP51")
      (value "TPB1,27")
      (footprint "eagle-import:B1,27")
      (libsource (lib "eagle-import") (part "TPB1,27"))
    )
    (comp (ref "U$5")
      (value "MMA7455L")
      (footprint "eagle-import:LGA14")
      (libsource (lib "eagle-import") (part "MMA7455L"))
    )
    (comp (ref "U$6")
      (value "MMA7455L")
      (footprint "eagle-import:LGA14")
      (libsource (lib "eagle-import") (part "MMA7455L"))
    )
    (comp (ref "C5")
      (value "10uF")
      (footprint "eagle-import:1210")
      (libsource (lib "eagle-import") (part "CAP1210"))
    )
    (comp (ref "C26")
      (value "10,0")
      (footprint "eagle-import:1210")
      (libsource (lib "eagle-import") (part "CAP1210"))
    )
    (comp (ref "C49")
      (value "100p")
      (footprint "eagle-import:0603-CAP")
      (libsource (lib "eagle-import") (part "CAP0603-CAP"))
    )
    (comp (ref "C53")
      (value "10uF")
      (footprint "eagle-import:1210")
      (libsource (lib "eagle-import") (part "CAP1210"))
    )
    (comp (ref "C54")
      (value "10uF")
      (footprint "eagle-import:1210")
      (libsource (lib "eagle-import") (part "CAP1210"))
    )
    (comp (ref "C59")
      (value "0.1")
      (footprint "eagle-import:0603-CAP")
      (libsource (lib "eagle-import") (part "CAP0603-CAP"))
    )
    (comp (ref "C60")
      (value "0.1")
      (footprint "eagle-import:0603-CAP")
      (libsource (lib "eagle-import") (part "CAP0603-CAP"))
    )
    (comp (ref "C61")
      (value "10uF")
      (footprint "eagle-import:1210")
      (libsource (lib "eagle-import") (part "CAP1210"))
    )
    (comp (ref "C62")
      (value "0.1")
      (footprint "eagle-import:0603-CAP")
      (libsource (lib "eagle-import") (part "CAP0603-CAP"))
    )
    (comp (ref "C63")
      (value "10uF")
      (footprint "eagle-import:1210")
      (libsource (lib "eagle-import") (part "CAP1210"))
    )
    (comp (ref "D2")
      (value "BAS70-04")
      (footprint "eagle-import:SOT23")
      (libsource (lib "eagle-import") (part "BAS70-04"))
    )
    (comp (ref "D3")
      (value "MBR0530")
      (footprint "eagle-import:SOD123")
      (libsource (lib "eagle-import") (part "MBR0520LT"))
    )
    (comp (ref "J1")
      (value "XF2J-3024-11")
      (footprint "eagle-import:XF2J-3024-11")
      (libsource (lib "eagle-import") (part "XF2-30?24-11J"))
    )
    (comp (ref "JP2")
      (value "JOYSTICK_MINI4UCON")
      (footprint "eagle-import:JOYSTICK_MINI")
      (libsource (lib "eagle-import") (part "JOYSTICK_MINI4UCON"))
    )
    (comp (ref "L2")
      (value "10uH")
      (footprint "eagle-import:WE-KI_0805_B")
      (libsource (lib "eagle-import") (part "WE-KIHQ_0805"))
    )
    (comp (ref "Q2")
      (value "IRLML6401")
      (footprint "eagle-import:MICRO3")
      (libsource (lib "eagle-import") (part "IRLML5203"))
    )
    (comp (ref "Q3")
      (value "TRANSISTOR_NPNSOT23-3")
      (footprint "eagle-import:SOT23-3")
      (libsource (lib "eagle-import") (part "TRANSISTOR_NPNSOT23-3"))
    )
    (comp (ref "R14")
      (value "117k")
      (footprint "eagle-import:0603-RES")
      (libsource (lib "eagle-import") (part "RESISTOR0603-RES"))
    )
    (comp (ref "R15")
      (value "13k3")
      (footprint "eagle-import:0603-RES")
      (libsource (lib "eagle-import") (part "RESISTOR0603-RES"))
    )
    (comp (ref "R16")
      (value "10k")
      (footprint "eagle-import:0603-RES")
      (libsource (lib "eagle-import") (part "RESISTOR0603-RES"))
    )
    (comp (ref "R17")
      (value "51r")
      (footprint "eagle-import:0603-RES")
      (libsource (lib "eagle-import") (part "RESISTOR0603-RES"))
    )
    (comp (ref "R18")
      (value "680k")
      (footprint "eagle-import:0603-RES")
      (libsource (lib "eagle-import") (part "RESISTOR0603-RES"))
    )
    (comp (ref "TP1")
      (value "TPB1,27")
      (footprint "eagle-import:B1,27")
      (libsource (lib "eagle-import") (part "TPB1,27"))
    )
    (comp (ref "TP2")
      (value "TPB1,27")
      (footprint "eagle-import:B1,27")
      (libsource (lib "eagle-import") (part "TPB1,27"))
    )
    (comp (ref "TP3")
      (value "TPB1,27")
      (footprint "eagle-import:B1,27")
      (libsource (lib "eagle-import") (part "TPB1,27"))
    )
    (comp (ref "TP4")
      (value "TPB1,27")
      (footprint "eagle-import:B1,27")
      (libsource (lib "eagle-import") (part "TPB1,27"))
    )
    (comp (ref "TP5")
      (value "TPB1,27")
      (footprint "eagle-import:B1,27")
      (libsource (lib "eagle-import") (part "TPB1,27"))
    )
    (comp (ref "TP6")
      (value "TPB1,27")
      (footprint "eagle-import:B1,27")
      (libsource (lib "eagle-import") (part "TPB1,27"))
    )
    (comp (ref "TP7")
      (value "TPB1,27")
      (footprint "eagle-import:B1,27")
      (libsource (lib "eagle-import") (part "TPB1,27"))
    )
    (comp (ref "TP8")
      (value "TPB1,27")
      (footprint "eagle-import:B1,27")
      (libsource (lib "eagle-import") (part "TPB1,27"))
    )
    (comp (ref "TP9")
      (value "TPB1,27")
      (footprint "eagle-import:B1,27")
      (libsource (lib "eagle-import") (part "TPB1,27"))
    )
    (comp (ref "TP10")
      (value "TPB1,27")
      (footprint "eagle-import:B1,27")
      (libsource (lib "eagle-import") (part "TPB1,27"))
    )
    (comp (ref "TP11")
      (value "TPB1,27")
      (footprint "eagle-import:B1,27")
      (libsource (lib "eagle-import") (part "TPB1,27"))
    )
    (comp (ref "TP44")
      (value "TPB1,27")
      (footprint "eagle-import:B1,27")
      (libsource (lib "eagle-import") (part "TPB1,27"))
    )
    (comp (ref "TP45")
      (value "TPB1,27")
      (footprint "eagle-import:B1,27")
      (libsource (lib "eagle-import") (part "TPB1,27"))
    )
    (comp (ref "TP46")
      (value "TPB1,27")
      (footprint "eagle-import:B1,27")
      (libsource (lib "eagle-import") (part "TPB1,27"))
    )
    (comp (ref "TP47")
      (value "TPB1,27")
      (footprint "eagle-import:B1,27")
      (libsource (lib "eagle-import") (part "TPB1,27"))
    )
    (comp (ref "TP48")
      (value "TPB1,27")
      (footprint "eagle-import:B1,27")
      (libsource (lib "eagle-import") (part "TPB1,27"))
    )
    (comp (ref "TP50")
      (value "TPB1,27")
      (footprint "eagle-import:B1,27")
      (libsource (lib "eagle-import") (part "TPB1,27"))
    )
    (comp (ref "TP52")
      (value "TPB1,27")
      (footprint "eagle-import:B1,27")
      (libsource (lib "eagle-import") (part "TPB1,27"))
    )
    (comp (ref "U$2")
      (value "LM2733")
      (footprint "eagle-import:SOT23-DBV")
      (libsource (lib "eagle-import") (part "LM2733"))
    )
    (comp (ref "C4")
      (value "33nF")
      (footprint "eagle-import:C0603")
      (libsource (lib "eagle-import") (part "C-EUC0603"))
    )
    (comp (ref "C14")
      (value "22,0")
      (footprint "eagle-import:SMC_C")
      (libsource (lib "eagle-import") (part "CPOL-EUSMCC"))
    )
    (comp (ref "C16")
      (value "10,0")
      (footprint "eagle-import:C1210")
      (libsource (lib "eagle-import") (part "C-EUC1210"))
    )
    (comp (ref "C22")
      (value "0,1")
      (footprint "eagle-import:C0603")
      (libsource (lib "eagle-import") (part "C-EUC0603"))
    )
    (comp (ref "C23")
      (value "0,1")
      (footprint "eagle-import:C0603")
      (libsource (lib "eagle-import") (part "C-EUC0603"))
    )
    (comp (ref "C24")
      (value "10n")
      (footprint "eagle-import:C0603")
      (libsource (lib "eagle-import") (part "C-EUC0603"))
    )
    (comp (ref "C25")
      (value "22,0")
      (footprint "eagle-import:SMC_C")
      (libsource (lib "eagle-import") (part "CPOL-EUSMCC"))
    )
    (comp (ref "C28")
      (value "0.1")
      (footprint "eagle-import:0603-CAP")
      (libsource (lib "eagle-import") (part "CAP0603-CAP"))
    )
    (comp (ref "C45")
      (value "0.1")
      (footprint "eagle-import:0603-CAP")
      (libsource (lib "eagle-import") (part "CAP0603-CAP"))
    )
    (comp (ref "C46")
      (value "1uF")
      (footprint "eagle-import:0603-CAP")
      (libsource (lib "eagle-import") (part "CAP0603-CAP"))
    )
    (comp (ref "C51")
      (value "0,1")
      (footprint "eagle-import:C0603")
      (libsource (lib "eagle-import") (part "C-EUC0603"))
    )
    (comp (ref "C52")
      (value "0,1")
      (footprint "eagle-import:C0603")
      (libsource (lib "eagle-import") (part "C-EUC0603"))
    )
    (comp (ref "C55")
      (value "0,1")
      (footprint "eagle-import:C0603")
      (libsource (lib "eagle-import") (part "C-EUC0603"))
    )
    (comp (ref "C56")
      (value "0,1")
      (footprint "eagle-import:C0603")
      (libsource (lib "eagle-import") (part "C-EUC0603"))
    )
    (comp (ref "C57")
      (value "4,7uF")
      (footprint "eagle-import:C0805K")
      (libsource (lib "eagle-import") (part "C-EUC0805K"))
    )
    (comp (ref "C58")
      (value "0,1")
      (footprint "eagle-import:C0603")
      (libsource (lib "eagle-import") (part "C-EUC0603"))
    )
    (comp (ref "C71")
      (value "0,1")
      (footprint "eagle-import:C0603")
      (libsource (lib "eagle-import") (part "C-EUC0603"))
    )
    (comp (ref "C72")
      (value "0,1")
      (footprint "eagle-import:C0603")
      (libsource (lib "eagle-import") (part "C-EUC0603"))
    )
    (comp (ref "COILGUN")
      (value "MA04-1")
      (footprint "eagle-import:MA04-1")
      (libsource (lib "eagle-import") (part "MA04-1"))
    )
    (comp (ref "IC3")
      (value "MAX803T")
      (footprint "eagle-import:SOT23B-3")
      (libsource (lib "eagle-import") (part "TCM809"))
    )
    (comp (ref "IC8")
      (value "LM2936MP-3.3")
      (footprint "eagle-import:SOT223")
      (fields (field (name "MF") "NATIONAL SEMICONDUCTOR") (field (name "MPN") "LM2936MP-3.0/NOPB"))
      (libsource (lib "eagle-import") (part "LM2936MP?-3.0"))
    )
    (comp (ref "JP1")
      (value "PINHD-2X7")
      (footprint "eagle-import:2X07")
      (libsource (lib "eagle-import") (part "PINHD-2X7"))
    )
    (comp (ref "L3")
      (value "4,7uH")
      (footprint "eagle-import:WE-KI_0805_B")
      (libsource (lib "eagle-import") (part "WE-KIHQ_0805"))
    )
    (comp (ref "LED1")
      (value "LEDCHIP-LED0603")
      (footprint "eagle-import:CHIP-LED0603")
      (libsource (lib "eagle-import") (part "LEDCHIP-LED0603"))
    )
    (comp (ref "LED2")
      (value "LEDCHIP-LED0603")
      (footprint "eagle-import:CHIP-LED0603")
      (libsource (lib "eagle-import") (part "LEDCHIP-LED0603"))
    )
    (comp (ref "LED3")
      (value "LEDCHIP-LED0603")
      (footprint "eagle-import:CHIP-LED0603")
      (libsource (lib "eagle-import") (part "LEDCHIP-LED0603"))
    )
    (comp (ref "LED4")
      (value "LEDCHIP-LED0603")
      (footprint "eagle-import:CHIP-LED0603")
      (libsource (lib "eagle-import") (part "LEDCHIP-LED0603"))
    )
    (comp (ref "LED5")
      (value "LEDCHIP-LED0603")
      (footprint "eagle-import:CHIP-LED0603")
      (libsource (lib "eagle-import") (part "LEDCHIP-LED0603"))
    )
    (comp (ref "MCU")
      (value "R32C111")
      (footprint "eagle-import:100P6Q-A")
      (libsource (lib "eagle-import") (part "R32C111"))
    )
    (comp (ref "PANDA")
      (value "MA03")
      (footprint "eagle-import:03P")
      (libsource (lib "eagle-import") (part "MA03"))
    )
    (comp (ref "Q1")
      (value "CRYSTALMM20SS")
      (footprint "eagle-import:MM20SS")
      (libsource (lib "eagle-import") (part "CRYSTALMM20SS"))
    )
    (comp (ref "Q4")
      (value "IRLML6401")
      (footprint "eagle-import:MICRO3")
      (libsource (lib "eagle-import") (part "IRLML5203"))
    )
    (comp (ref "Q5")
      (value "IRLML6401")
      (footprint "eagle-import:MICRO3")
      (libsource (lib "eagle-import") (part "IRLML5203"))
    )
    (comp (ref "R1")
      (value "4k7")
      (footprint "eagle-import:0603-RES")
      (libsource (lib "eagle-import") (part "RESISTOR0603-RES"))
    )
    (comp (ref "R8")
      (value "4k7")
      (footprint "eagle-import:R0603")
      (libsource (lib "eagle-import") (part "R-EU_R0603"))
    )
    (comp (ref "R10")
      (value "1k")
      (footprint "eagle-import:0603-RES")
      (libsource (lib "eagle-import") (part "RESISTOR0603-RES"))
    )
    (comp (ref "R19")
      (value "1k")
      (footprint "eagle-import:0603-RES")
      (libsource (lib "eagle-import") (part "RESISTOR0603-RES"))
    )
    (comp (ref "R39")
      (value "1k")
      (footprint "eagle-import:0603-RES")
      (libsource (lib "eagle-import") (part "RESISTOR0603-RES"))
    )
    (comp (ref "R40")
      (value "1k")
      (footprint "eagle-import:0603-RES")
      (libsource (lib "eagle-import") (part "RESISTOR0603-RES"))
    )
    (comp (ref "R42")
      (value "1k")
      (footprint "eagle-import:0603-RES")
      (libsource (lib "eagle-import") (part "RESISTOR0603-RES"))
    )
    (comp (ref "R44")
      (value "4k7")
      (footprint "eagle-import:R0603")
      (libsource (lib "eagle-import") (part "R-EU_R0603"))
    )
    (comp (ref "R45")
      (value "4k7")
      (footprint "eagle-import:R0603")
      (libsource (lib "eagle-import") (part "R-EU_R0603"))
    )
    (comp (ref "R46")
      (value "4k7")
      (footprint "eagle-import:R0603")
      (libsource (lib "eagle-import") (part "R-EU_R0603"))
    )
    (comp (ref "R47")
      (value "1k")
      (footprint "eagle-import:0603-RES")
      (libsource (lib "eagle-import") (part "RESISTOR0603-RES"))
    )
    (comp (ref "R48")
      (value "4k7")
      (footprint "eagle-import:R0603")
      (libsource (lib "eagle-import") (part "R-EU_R0603"))
    )
    (comp (ref "R50")
      (value "4k7")
      (footprint "eagle-import:R0603")
      (libsource (lib "eagle-import") (part "R-EU_R0603"))
    )
    (comp (ref "R51")
      (value "1k5")
      (footprint "eagle-import:R0603")
      (libsource (lib "eagle-import") (part "R-EU_R0603"))
    )
    (comp (ref "R53")
      (value "4k7")
      (footprint "eagle-import:R0603")
      (libsource (lib "eagle-import") (part "R-EU_R0603"))
    )
    (comp (ref "R61")
      (value "4k7")
      (footprint "eagle-import:R0603")
      (libsource (lib "eagle-import") (part "R-EU_R0603"))
    )
    (comp (ref "R62")
      (value "4k7")
      (footprint "eagle-import:R0603")
      (libsource (lib "eagle-import") (part "R-EU_R0603"))
    )
    (comp (ref "SG2")
      (value "BUZZERSMD3")
      (footprint "eagle-import:BUZZER-CMT1102")
      (libsource (lib "eagle-import") (part "BUZZERSMD3"))
    )
    (comp (ref "TP57")
      (value "TPB1,27")
      (footprint "eagle-import:B1,27")
      (libsource (lib "eagle-import") (part "TPB1,27"))
    )
    (comp (ref "TP58")
      (value "TPB1,27")
      (footprint "eagle-import:B1,27")
      (libsource (lib "eagle-import") (part "TPB1,27"))
    )
    (comp (ref "TP60")
      (value "TPB1,27")
      (footprint "eagle-import:B1,27")
      (libsource (lib "eagle-import") (part "TPB1,27"))
    )
    (comp (ref "TP61")
      (value "TPB1,27")
      (footprint "eagle-import:B1,27")
      (libsource (lib "eagle-import") (part "TPB1,27"))
    )
    (comp (ref "TP62")
      (value "TPB1,27")
      (footprint "eagle-import:B1,27")
      (libsource (lib "eagle-import") (part "TPB1,27"))
    )
    (comp (ref "TP63")
      (value "TPB1,27")
      (footprint "eagle-import:B1,27")
      (libsource (lib "eagle-import") (part "TPB1,27"))
    )
    (comp (ref "TP64")
      (value "TPB1,27")
      (footprint "eagle-import:B1,27")
      (libsource (lib "eagle-import") (part "TPB1,27"))
    )
    (comp (ref "TP65")
      (value "TPB1,27")
      (footprint "eagle-import:B1,27")
      (libsource (lib "eagle-import") (part "TPB1,27"))
    )
    (comp (ref "Y2")
      (value "RESONATORSMD")
      (footprint "eagle-import:RESONATOR-SMD")
      (libsource (lib "eagle-import") (part "RESONATORSMD"))
    )
    (comp (ref "J3")
      (value "PINHD-2X14")
      (footprint "eagle-import:2X14")
      (libsource (lib "eagle-import") (part "PINHD-2X14"))
    )
    (comp (ref "J6")
      (value "PINHD-2X14")
      (footprint "eagle-import:2X14")
      (libsource (lib "eagle-import") (part "PINHD-2X14"))
    )
    (comp (ref "R59")
      (value "10k")
      (footprint "eagle-import:R0603")
      (libsource (lib "eagle-import") (part "R-US_R0603"))
    )
    (comp (ref "R60")
      (value "10k")
      (footprint "eagle-import:R0603")
      (libsource (lib "eagle-import") (part "R-US_R0603"))
    )
    (comp (ref "U1")
      (value "txb0108")
      (footprint "eagle-import:TSSOP20")
      (libsource (lib "eagle-import") (part "TXB0108PWR"))
    )
    (comp (ref "X4")
      (value "USB-A-S")
      (footprint "eagle-import:USB-A-S")
      (libsource (lib "eagle-import") (part "USB-A-S"))
    )
    (comp (ref "X7")
      (value "SDBMF")
      (footprint "eagle-import:SDBMF-009XXBXX2")
      (libsource (lib "eagle-import") (part "SDBMF"))
    )
    (comp (ref "C1")
      (value "820uF/16V")
      (footprint "eagle-import:153CLV-1014")
      (libsource (lib "eagle-import") (part "CPOL-EU153CLV-1014"))
    )
    (comp (ref "C2")
      (value "820uF/16V")
      (footprint "eagle-import:153CLV-1014")
      (libsource (lib "eagle-import") (part "CPOL-EU153CLV-1014"))
    )
    (comp (ref "C7")
      (value "33n")
      (footprint "eagle-import:0603-CAP")
      (libsource (lib "eagle-import") (part "CAP0603-CAP"))
    )
    (comp (ref "C12")
      (value "100uF/16V")
      (footprint "eagle-import:C_6032-28R")
      (libsource (lib "eagle-import") (part "CPOL-EUC/6032-28R"))
    )
    (comp (ref "C13")
      (value "100uF/16V")
      (footprint "eagle-import:C_6032-28R")
      (libsource (lib "eagle-import") (part "CPOL-EUC/6032-28R"))
    )
    (comp (ref "C31")
      (value "10u")
      (footprint "eagle-import:C1210")
      (libsource (lib "eagle-import") (part "C-EUC1210"))
    )
    (comp (ref "C32")
      (value "100p")
      (footprint "eagle-import:0603-CAP")
      (libsource (lib "eagle-import") (part "CAP0603-CAP"))
    )
    (comp (ref "C36")
      (value "0.1uF 600V")
      (footprint "eagle-import:C1812")
      (libsource (lib "eagle-import") (part "C-EUC1812"))
    )
    (comp (ref "CHGLED1")
      (value "LEDCHIPLED_0603")
      (footprint "eagle-import:CHIPLED_0603")
      (libsource (lib "eagle-import") (part "LEDCHIPLED_0603"))
    )
    (comp (ref "CHGLED2")
      (value "LEDCHIPLED_0603")
      (footprint "eagle-import:CHIPLED_0603")
      (libsource (lib "eagle-import") (part "LEDCHIPLED_0603"))
    )
    (comp (ref "D1")
      (value "MURS160")
      (footprint "eagle-import:SMB")
      (libsource (lib "eagle-import") (part "ES2D"))
    )
    (comp (ref "D4")
      (value "BAT54")
      (footprint "eagle-import:SOT23")
      (libsource (lib "eagle-import") (part "BAT54"))
    )
    (comp (ref "LSP1")
      (value "LSP11")
      (footprint "eagle-import:LSP11")
      (libsource (lib "eagle-import") (part "LSP11"))
    )
    (comp (ref "LSP2")
      (value "LSP11")
      (footprint "eagle-import:LSP11")
      (libsource (lib "eagle-import") (part "LSP11"))
    )
    (comp (ref "LT3750")
      (value "LT3750")
      (footprint "eagle-import:MSOP")
      (libsource (lib "eagle-import") (part "LT3750"))
    )
    (comp (ref "PAD25")
      (value "1,6/0,9")
      (footprint "eagle-import:1,6_0,9")
      (libsource (lib "eagle-import") (part "1,6/0,9"))
    )
    (comp (ref "R20")
      (value "8m")
      (footprint "eagle-import:R1210")
      (libsource (lib "eagle-import") (part "R-EU_R1210"))
    )
    (comp (ref "R21")
      (value "43k")
      (footprint "eagle-import:0603-RES")
      (libsource (lib "eagle-import") (part "RESISTOR0603-RES"))
    )
    (comp (ref "R22")
      (value "1.87k")
      (footprint "eagle-import:0603-RES")
      (libsource (lib "eagle-import") (part "RESISTOR0603-RES"))
    )
    (comp (ref "R23")
      (value "10k")
      (footprint "eagle-import:0603-RES")
      (libsource (lib "eagle-import") (part "RESISTOR0603-RES"))
    )
    (comp (ref "R24")
      (value "60.4k")
      (footprint "eagle-import:0603-RES")
      (libsource (lib "eagle-import") (part "RESISTOR0603-RES"))
    )
    (comp (ref "R57")
      (value "400k")
      (footprint "eagle-import:R1210")
      (libsource (lib "eagle-import") (part "R-US_R1210"))
    )
    (comp (ref "TP12")
      (value "TPB1,27")
      (footprint "eagle-import:B1,27")
      (libsource (lib "eagle-import") (part "TPB1,27"))
    )
    (comp (ref "TP13")
      (value "TPB1,27")
      (footprint "eagle-import:B1,27")
      (libsource (lib "eagle-import") (part "TPB1,27"))
    )
    (comp (ref "TP14")
      (value "TPB1,27")
      (footprint "eagle-import:B1,27")
      (libsource (lib "eagle-import") (part "TPB1,27"))
    )
    (comp (ref "TP15")
      (value "TPB1,27")
      (footprint "eagle-import:B1,27")
      (libsource (lib "eagle-import") (part "TPB1,27"))
    )
    (comp (ref "TP16")
      (value "TPB1,27")
      (footprint "eagle-import:B1,27")
      (libsource (lib "eagle-import") (part "TPB1,27"))
    )
    (comp (ref "TP17")
      (value "TPB1,27")
      (footprint "eagle-import:B1,27")
      (libsource (lib "eagle-import") (part "TPB1,27"))
    )
    (comp (ref "TP18")
      (value "TPB1,27")
      (footprint "eagle-import:B1,27")
      (libsource (lib "eagle-import") (part "TPB1,27"))
    )
    (comp (ref "TP59")
      (value "TPB1,27")
      (footprint "eagle-import:B1,27")
      (libsource (lib "eagle-import") (part "TPB1,27"))
    )
    (comp (ref "U$1")
      (value "DA2032-ALBDA2032-ALB")
      (footprint "eagle-import:DA2032-ALB")
      (libsource (lib "eagle-import") (part "DA2032-ALBDA2032-ALB"))
    )
    (comp (ref "U$102")
      (value "IRF7855PBF")
      (footprint "eagle-import:SO8")
      (libsource (lib "eagle-import") (part "IRF8252"))
    )
    (comp (ref "C18")
      (value "0.1")
      (footprint "eagle-import:C0603")
      (libsource (lib "eagle-import") (part "C-EUC0603"))
    )
    (comp (ref "C30")
      (value "0.1")
      (footprint "eagle-import:C0603")
      (libsource (lib "eagle-import") (part "C-EUC0603"))
    )
    (comp (ref "C33")
      (value "10uF/6.3V")
      (footprint "eagle-import:C_6032-28R")
      (libsource (lib "eagle-import") (part "resistor_CPOL-EUC/6032-28R"))
    )
    (comp (ref "C47")
      (value "470nF")
      (footprint "eagle-import:0603-CAP")
      (libsource (lib "eagle-import") (part "CAP0603-CAP"))
    )
    (comp (ref "C48")
      (value "10nF")
      (footprint "eagle-import:0603-CAP")
      (libsource (lib "eagle-import") (part "CAP0603-CAP"))
    )
    (comp (ref "C64")
      (value "0.1")
      (footprint "eagle-import:0603-CAP")
      (libsource (lib "eagle-import") (part "CAP0603-CAP"))
    )
    (comp (ref "IC1")
      (value "TPS77350")
      (footprint "eagle-import:SOP-08")
      (fields (field (name "MF") "TEXAS INSTRUMENT CONNECTORS") (field (name "MPN") "TPS77350DGK"))
      (libsource (lib "eagle-import") (part "TPS77350"))
    )
    (comp (ref "J4")
      (value "XF2L-0625-1")
      (footprint "eagle-import:XF2L-0625-1")
      (fields (field (name "MF") "OMRON COMPONENTS USA"))
      (libsource (lib "eagle-import") (part "XF2-06?25-1L"))
    )
    (comp (ref "J5")
      (value "XF2L-0625-1")
      (footprint "eagle-import:XF2L-0625-1")
      (fields (field (name "MF") "OMRON COMPONENTS USA"))
      (libsource (lib "eagle-import") (part "XF2-06?25-1L"))
    )
    (comp (ref "R9")
      (value "10k")
      (footprint "eagle-import:0603-RES")
      (libsource (lib "eagle-import") (part "RESISTOR0603-RES"))
    )
    (comp (ref "R58")
      (value "10k")
      (footprint "eagle-import:0603-RES")
      (libsource (lib "eagle-import") (part "RESISTOR0603-RES"))
    )
    (comp (ref "TP38")
      (value "TPB1,27")
      (footprint "eagle-import:B1,27")
      (libsource (lib "eagle-import") (part "TPB1,27"))
    )
    (comp (ref "TP39")
      (value "TPB1,27")
      (footprint "eagle-import:B1,27")
      (libsource (lib "eagle-import") (part "TPB1,27"))
    )
    (comp (ref "TP40")
      (value "TPB1,27")
      (footprint "eagle-import:B1,27")
      (libsource (lib "eagle-import") (part "TPB1,27"))
    )
    (comp (ref "TP41")
      (value "TPB1,27")
      (footprint "eagle-import:B1,27")
      (libsource (lib "eagle-import") (part "TPB1,27"))
    )
    (comp (ref "TP42")
      (value "TPB1,27")
      (footprint "eagle-import:B1,27")
      (libsource (lib "eagle-import") (part "TPB1,27"))
    )
    (comp (ref "TP43")
      (value "TPB1,27")
      (footprint "eagle-import:B1,27")
      (libsource (lib "eagle-import") (part "TPB1,27"))
    )
    (comp (ref "U2")
      (value "L3G4200D")
      (footprint "eagle-import:LGA16-4X4")
      (libsource (lib "eagle-import") (part "L3G4200D"))
    )
    (comp (ref "5V")
      (value "M02")
      (footprint "eagle-import:02P")
      (libsource (lib "eagle-import") (part "M02"))
    )
    (comp (ref "10UF/16V")
      (value "CPOL-EUC/6032-28R")
      (footprint "eagle-import:C_6032-28R")
      (libsource (lib "eagle-import") (part "CPOL-EUC/6032-28R"))
    )
    (comp (ref "C9")
      (value "4,7uF/6.3V")
      (footprint "eagle-import:C0805")
      (libsource (lib "eagle-import") (part "C-EUC0805"))
    )
    (comp (ref "C10")
      (value "180pF")
      (footprint "eagle-import:C0805K")
      (libsource (lib "eagle-import") (part "C-EUC0805K"))
    )
    (comp (ref "C11")
      (value "12pF")
      (footprint "eagle-import:C0805K")
      (libsource (lib "eagle-import") (part "C-EUC0805K"))
    )
    (comp (ref "C15")
      (value "0.1")
      (footprint "eagle-import:C0805K")
      (libsource (lib "eagle-import") (part "C-EUC0805K"))
    )
    (comp (ref "C27")
      (value "15nF")
      (footprint "eagle-import:C0805K")
      (libsource (lib "eagle-import") (part "C-EUC0805K"))
    )
    (comp (ref "C29")
      (value "10uF/6.3V")
      (footprint "eagle-import:1210")
      (libsource (lib "eagle-import") (part "CAP1210"))
    )
    (comp (ref "C100")
      (value "47uF/16V")
      (footprint "eagle-import:C_6032-28R")
      (libsource (lib "eagle-import") (part "CPOL-EUC/6032-28R"))
    )
    (comp (ref "D100")
      (value "BAT54")
      (footprint "eagle-import:SOT23")
      (libsource (lib "eagle-import") (part "BAT54"))
    )
    (comp (ref "GND")
      (value "3,81/1,4")
      (footprint "eagle-import:3,81_1,4")
      (libsource (lib "eagle-import") (part "3,81/1,4"))
    )
    (comp (ref "GND78")
      (value "3,81/1,4")
      (footprint "eagle-import:3,81_1,4")
      (libsource (lib "eagle-import") (part "3,81/1,4"))
    )
    (comp (ref "R11")
      (value "63k4")
      (footprint "eagle-import:R0805")
      (libsource (lib "eagle-import") (part "resistor_R-EU_R0805"))
    )
    (comp (ref "R26")
      (value "1k87")
      (footprint "eagle-import:R0805")
      (libsource (lib "eagle-import") (part "resistor_R-EU_R0805"))
    )
    (comp (ref "R35")
      (value "100k")
      (footprint "eagle-import:R0805")
      (libsource (lib "eagle-import") (part "resistor_R-EU_R0805"))
    )
    (comp (ref "R37")
      (value "10k")
      (footprint "eagle-import:R0805")
      (libsource (lib "eagle-import") (part "resistor_R-EU_R0805"))
    )
    (comp (ref "TP53")
      (value "TPB1,27")
      (footprint "eagle-import:B1,27")
      (libsource (lib "eagle-import") (part "TPB1,27"))
    )
    (comp (ref "TP54")
      (value "TPB1,27")
      (footprint "eagle-import:B1,27")
      (libsource (lib "eagle-import") (part "TPB1,27"))
    )
    (comp (ref "TP55")
      (value "TPB1,27")
      (footprint "eagle-import:B1,27")
      (libsource (lib "eagle-import") (part "TPB1,27"))
    )
    (comp (ref "TP56")
      (value "TPB1,27")
      (footprint "eagle-import:B1,27")
      (libsource (lib "eagle-import") (part "TPB1,27"))
    )
    (comp (ref "U$3")
      (value "TPS54233")
      (footprint "eagle-import:SO8")
      (libsource (lib "eagle-import") (part "TPS54332"))
    )
    (comp (ref "U$100")
      (value "3,3uH, 5A, EPCOS B82464G4332M , Farnell 7429410")
      (footprint "eagle-import:CR54")
      (libsource (lib "eagle-import") (part "INDUCTORCR54"))
    )
    (comp (ref "VBAT")
      (value "3,81/1,4")
      (footprint "eagle-import:3,81_1,4")
      (libsource (lib "eagle-import") (part "3,81/1,4"))
    )
    (comp (ref "PAD3")
      (value "1,6/0,9")
      (footprint "eagle-import:1,6_0,9")
      (libsource (lib "eagle-import") (part "1,6/0,9"))
    )
    (comp (ref "PAD4")
      (value "1,6/0,9")
      (footprint "eagle-import:1,6_0,9")
      (libsource (lib "eagle-import") (part "1,6/0,9"))
    )
    (comp (ref "PAD7")
      (value "1,6/0,9")
      (footprint "eagle-import:1,6_0,9")
      (libsource (lib "eagle-import") (part "1,6/0,9"))
    )
    (comp (ref "PAD8")
      (value "1,6/0,9")
      (footprint "eagle-import:1,6_0,9")
      (libsource (lib "eagle-import") (part "1,6/0,9"))
    )
    (comp (ref "PAD9")
      (value "1,6/0,9")
      (footprint "eagle-import:1,6_0,9")
      (libsource (lib "eagle-import") (part "1,6/0,9"))
    )
    (comp (ref "PAD10")
      (value "1,6/0,9")
      (footprint "eagle-import:1,6_0,9")
      (libsource (lib "eagle-import") (part "1,6/0,9"))
    )
    (comp (ref "PAD11")
      (value "1,6/0,9")
      (footprint "eagle-import:1,6_0,9")
      (libsource (lib "eagle-import") (part "1,6/0,9"))
    )
    (comp (ref "PAD12")
      (value "1,6/0,9")
      (footprint "eagle-import:1,6_0,9")
      (libsource (lib "eagle-import") (part "1,6/0,9"))
    )
    (comp (ref "PAD13")
      (value "1,6/0,9")
      (footprint "eagle-import:1,6_0,9")
      (libsource (lib "eagle-import") (part "1,6/0,9"))
    )
    (comp (ref "PAD14")
      (value "1,6/0,9")
      (footprint "eagle-import:1,6_0,9")
      (libsource (lib "eagle-import") (part "1,6/0,9"))
    )
    (comp (ref "PAD15")
      (value "1,6/0,9")
      (footprint "eagle-import:1,6_0,9")
      (libsource (lib "eagle-import") (part "1,6/0,9"))
    )
    (comp (ref "PAD16")
      (value "1,6/0,9")
      (footprint "eagle-import:1,6_0,9")
      (libsource (lib "eagle-import") (part "1,6/0,9"))
    )
    (comp (ref "PAD17")
      (value "1,6/0,9")
      (footprint "eagle-import:1,6_0,9")
      (libsource (lib "eagle-import") (part "1,6/0,9"))
    )
    (comp (ref "PAD18")
      (value "1,6/0,9")
      (footprint "eagle-import:1,6_0,9")
      (libsource (lib "eagle-import") (part "1,6/0,9"))
    )
    (comp (ref "PAD19")
      (value "1,6/0,9")
      (footprint "eagle-import:1,6_0,9")
      (libsource (lib "eagle-import") (part "1,6/0,9"))
    )
    (comp (ref "PAD20")
      (value "1,6/0,9")
      (footprint "eagle-import:1,6_0,9")
      (libsource (lib "eagle-import") (part "1,6/0,9"))
    )
    (comp (ref "PAD21")
      (value "1,6/0,9")
      (footprint "eagle-import:1,6_0,9")
      (libsource (lib "eagle-import") (part "1,6/0,9"))
    )
    (comp (ref "PAD22")
      (value "1,6/0,9")
      (footprint "eagle-import:1,6_0,9")
      (libsource (lib "eagle-import") (part "1,6/0,9"))
    )
    (comp (ref "PAD23")
      (value "1,6/0,9")
      (footprint "eagle-import:1,6_0,9")
      (libsource (lib "eagle-import") (part "1,6/0,9"))
    )
    (comp (ref "PAD24")
      (value "1,6/0,9")
      (footprint "eagle-import:1,6_0,9")
      (libsource (lib "eagle-import") (part "1,6/0,9"))
    )
    (comp (ref "PAD26")
      (value "WIREPAD1,6/0,8")
      (footprint "eagle-import:1,6_0,8")
      (libsource (lib "eagle-import") (part "WIREPAD1,6/0,8"))
    )
    (comp (ref "PAD27")
      (value "WIREPAD1,6/0,8")
      (footprint "eagle-import:1,6_0,8")
      (libsource (lib "eagle-import") (part "WIREPAD1,6/0,8"))
    )
    (comp (ref "PAD28")
      (value "WIREPAD1,6/0,8")
      (footprint "eagle-import:1,6_0,8")
      (libsource (lib "eagle-import") (part "WIREPAD1,6/0,8"))
    )
    (comp (ref "PAD29")
      (value "WIREPAD1,6/0,8")
      (footprint "eagle-import:1,6_0,8")
      (libsource (lib "eagle-import") (part "WIREPAD1,6/0,8"))
    )
    (comp (ref "PAD30")
      (value "WIREPAD1,6/0,8")
      (footprint "eagle-import:1,6_0,8")
      (libsource (lib "eagle-import") (part "WIREPAD1,6/0,8"))
    )
    (comp (ref "PAD31")
      (value "WIREPAD1,6/0,8")
      (footprint "eagle-import:1,6_0,8")
      (libsource (lib "eagle-import") (part "WIREPAD1,6/0,8"))
    )
    (comp (ref "PAD32")
      (value "WIREPAD1,6/0,8")
      (footprint "eagle-import:1,6_0,8")
      (libsource (lib "eagle-import") (part "WIREPAD1,6/0,8"))
    )
    (comp (ref "PAD33")
      (value "WIREPAD1,6/0,8")
      (footprint "eagle-import:1,6_0,8")
      (libsource (lib "eagle-import") (part "WIREPAD1,6/0,8"))
    )
    (comp (ref "PAD34")
      (value "WIREPAD1,6/0,8")
      (footprint "eagle-import:1,6_0,8")
      (libsource (lib "eagle-import") (part "WIREPAD1,6/0,8"))
    )
    (comp (ref "PAD35")
      (value "WIREPAD1,6/0,8")
      (footprint "eagle-import:1,6_0,8")
      (libsource (lib "eagle-import") (part "WIREPAD1,6/0,8"))
    )
    (comp (ref "PAD36")
      (value "WIREPAD1,6/0,8")
      (footprint "eagle-import:1,6_0,8")
      (libsource (lib "eagle-import") (part "WIREPAD1,6/0,8"))
    )
    (comp (ref "PAD37")
      (value "WIREPAD1,6/0,8")
      (footprint "eagle-import:1,6_0,8")
      (libsource (lib "eagle-import") (part "WIREPAD1,6/0,8"))
    )
    (comp (ref "PAD38")
      (value "WIREPAD1,6/0,8")
      (footprint "eagle-import:1,6_0,8")
      (libsource (lib "eagle-import") (part "WIREPAD1,6/0,8"))
    )
    (comp (ref "PAD39")
      (value "WIREPAD1,6/0,8")
      (footprint "eagle-import:1,6_0,8")
      (libsource (lib "eagle-import") (part "WIREPAD1,6/0,8"))
    )
    (comp (ref "PAD40")
      (value "WIREPAD1,6/0,8")
      (footprint "eagle-import:1,6_0,8")
      (libsource (lib "eagle-import") (part "WIREPAD1,6/0,8"))
    )
    (comp (ref "PAD41")
      (value "WIREPAD1,6/0,8")
      (footprint "eagle-import:1,6_0,8")
      (libsource (lib "eagle-import") (part "WIREPAD1,6/0,8"))
    )
    (comp (ref "PAD42")
      (value "WIREPAD1,6/0,8")
      (footprint "eagle-import:1,6_0,8")
      (libsource (lib "eagle-import") (part "WIREPAD1,6/0,8"))
    )
    (comp (ref "PAD43")
      (value "WIREPAD1,6/0,8")
      (footprint "eagle-import:1,6_0,8")
      (libsource (lib "eagle-import") (part "WIREPAD1,6/0,8"))
    )
    (comp (ref "PAD44")
      (value "WIREPAD1,6/0,8")
      (footprint "eagle-import:1,6_0,8")
      (libsource (lib "eagle-import") (part "WIREPAD1,6/0,8"))
    )
    (comp (ref "PAD45")
      (value "WIREPAD1,6/0,8")
      (footprint "eagle-import:1,6_0,8")
      (libsource (lib "eagle-import") (part "WIREPAD1,6/0,8"))
    )
    (comp (ref "PAD46")
      (value "WIREPAD1,6/0,8")
      (footprint "eagle-import:1,6_0,8")
      (libsource (lib "eagle-import") (part "WIREPAD1,6/0,8"))
    )
    (comp (ref "PAD47")
      (value "WIREPAD1,6/0,8")
      (footprint "eagle-import:1,6_0,8")
      (libsource (lib "eagle-import") (part "WIREPAD1,6/0,8"))
    )
    (comp (ref "PAD48")
      (value "WIREPAD1,6/0,8")
      (footprint "eagle-import:1,6_0,8")
      (libsource (lib "eagle-import") (part "WIREPAD1,6/0,8"))
    )
    (comp (ref "PAD49")
      (value "WIREPAD1,6/0,8")
      (footprint "eagle-import:1,6_0,8")
      (libsource (lib "eagle-import") (part "WIREPAD1,6/0,8"))
    )
    (comp (ref "PAD50")
      (value "WIREPAD1,6/0,8")
      (footprint "eagle-import:1,6_0,8")
      (libsource (lib "eagle-import") (part "WIREPAD1,6/0,8"))
    )
    (comp (ref "PAD51")
      (value "WIREPAD1,6/0,8")
      (footprint "eagle-import:1,6_0,8")
      (libsource (lib "eagle-import") (part "WIREPAD1,6/0,8"))
    )
    (comp (ref "PAD52")
      (value "WIREPAD1,6/0,8")
      (footprint "eagle-import:1,6_0,8")
      (libsource (lib "eagle-import") (part "WIREPAD1,6/0,8"))
    )
    (comp (ref "PAD53")
      (value "WIREPAD1,6/0,8")
      (footprint "eagle-import:1,6_0,8")
      (libsource (lib "eagle-import") (part "WIREPAD1,6/0,8"))
    )
    (comp (ref "PAD54")
      (value "WIREPAD1,6/0,8")
      (footprint "eagle-import:1,6_0,8")
      (libsource (lib "eagle-import") (part "WIREPAD1,6/0,8"))
    )
    (comp (ref "PAD55")
      (value "WIREPAD1,6/0,8")
      (footprint "eagle-import:1,6_0,8")
      (libsource (lib "eagle-import") (part "WIREPAD1,6/0,8"))
    )
    (comp (ref "PAD56")
      (value "WIREPAD1,6/0,8")
      (footprint "eagle-import:1,6_0,8")
      (libsource (lib "eagle-import") (part "WIREPAD1,6/0,8"))
    )
    (comp (ref "PAD57")
      (value "WIREPAD1,6/0,8")
      (footprint "eagle-import:1,6_0,8")
      (libsource (lib "eagle-import") (part "WIREPAD1,6/0,8"))
    )
    (comp (ref "PAD58")
      (value "WIREPAD1,6/0,8")
      (footprint "eagle-import:1,6_0,8")
      (libsource (lib "eagle-import") (part "WIREPAD1,6/0,8"))
    )
    (comp (ref "PAD59")
      (value "WIREPAD1,6/0,8")
      (footprint "eagle-import:1,6_0,8")
      (libsource (lib "eagle-import") (part "WIREPAD1,6/0,8"))
    )
    (comp (ref "PAD60")
      (value "WIREPAD1,6/0,8")
      (footprint "eagle-import:1,6_0,8")
      (libsource (lib "eagle-import") (part "WIREPAD1,6/0,8"))
    )
    (comp (ref "PAD61")
      (value "WIREPAD1,6/0,8")
      (footprint "eagle-import:1,6_0,8")
      (libsource (lib "eagle-import") (part "WIREPAD1,6/0,8"))
    )
    (comp (ref "PAD62")
      (value "WIREPAD1,6/0,8")
      (footprint "eagle-import:1,6_0,8")
      (libsource (lib "eagle-import") (part "WIREPAD1,6/0,8"))
    )
    (comp (ref "PAD63")
      (value "WIREPAD1,6/0,8")
      (footprint "eagle-import:1,6_0,8")
      (libsource (lib "eagle-import") (part "WIREPAD1,6/0,8"))
    )
    (comp (ref "PAD64")
      (value "WIREPAD1,6/0,8")
      (footprint "eagle-import:1,6_0,8")
      (libsource (lib "eagle-import") (part "WIREPAD1,6/0,8"))
    )
    (comp (ref "PAD65")
      (value "WIREPAD1,6/0,8")
      (footprint "eagle-import:1,6_0,8")
      (libsource (lib "eagle-import") (part "WIREPAD1,6/0,8"))
    )
    (comp (ref "PAD66")
      (value "WIREPAD1,6/0,8")
      (footprint "eagle-import:1,6_0,8")
      (libsource (lib "eagle-import") (part "WIREPAD1,6/0,8"))
    )
    (comp (ref "PAD67")
      (value "WIREPAD1,6/0,8")
      (footprint "eagle-import:1,6_0,8")
      (libsource (lib "eagle-import") (part "WIREPAD1,6/0,8"))
    )
    (comp (ref "PAD68")
      (value "WIREPAD1,6/0,8")
      (footprint "eagle-import:1,6_0,8")
      (libsource (lib "eagle-import") (part "WIREPAD1,6/0,8"))
    )
    (comp (ref "PAD69")
      (value "WIREPAD1,6/0,8")
      (footprint "eagle-import:1,6_0,8")
      (libsource (lib "eagle-import") (part "WIREPAD1,6/0,8"))
    )
    (comp (ref "PAD70")
      (value "WIREPAD1,6/0,8")
      (footprint "eagle-import:1,6_0,8")
      (libsource (lib "eagle-import") (part "WIREPAD1,6/0,8"))
    )
    (comp (ref "PAD71")
      (value "WIREPAD1,6/0,8")
      (footprint "eagle-import:1,6_0,8")
      (libsource (lib "eagle-import") (part "WIREPAD1,6/0,8"))
    )
    (comp (ref "PAD72")
      (value "WIREPAD1,6/0,8")
      (footprint "eagle-import:1,6_0,8")
      (libsource (lib "eagle-import") (part "WIREPAD1,6/0,8"))
    )
    (comp (ref "PAD73")
      (value "WIREPAD1,6/0,8")
      (footprint "eagle-import:1,6_0,8")
      (libsource (lib "eagle-import") (part "WIREPAD1,6/0,8"))
    )
    (comp (ref "PAD74")
      (value "WIREPAD1,6/0,8")
      (footprint "eagle-import:1,6_0,8")
      (libsource (lib "eagle-import") (part "WIREPAD1,6/0,8"))
    )
    (comp (ref "PAD75")
      (value "WIREPAD1,6/0,8")
      (footprint "eagle-import:1,6_0,8")
      (libsource (lib "eagle-import") (part "WIREPAD1,6/0,8"))
    )
    (comp (ref "PAD76")
      (value "WIREPAD1,6/0,8")
      (footprint "eagle-import:1,6_0,8")
      (libsource (lib "eagle-import") (part "WIREPAD1,6/0,8"))
    )
    (comp (ref "PAD77")
      (value "WIREPAD1,6/0,8")
      (footprint "eagle-import:1,6_0,8")
      (libsource (lib "eagle-import") (part "WIREPAD1,6/0,8"))
    )
    (comp (ref "PAD78")
      (value "WIREPAD1,6/0,8")
      (footprint "eagle-import:1,6_0,8")
      (libsource (lib "eagle-import") (part "WIREPAD1,6/0,8"))
    )
    (comp (ref "PAD79")
      (value "WIREPAD1,6/0,8")
      (footprint "eagle-import:1,6_0,8")
      (libsource (lib "eagle-import") (part "WIREPAD1,6/0,8"))
    )
    (comp (ref "PAD80")
      (value "WIREPAD1,6/0,8")
      (footprint "eagle-import:1,6_0,8")
      (libsource (lib "eagle-import") (part "WIREPAD1,6/0,8"))
    )
    (comp (ref "PAD81")
      (value "WIREPAD1,6/0,8")
      (footprint "eagle-import:1,6_0,8")
      (libsource (lib "eagle-import") (part "WIREPAD1,6/0,8"))
    )
    (comp (ref "PAD82")
      (value "WIREPAD1,6/0,8")
      (footprint "eagle-import:1,6_0,8")
      (libsource (lib "eagle-import") (part "WIREPAD1,6/0,8"))
    )
    (comp (ref "PAD83")
      (value "WIREPAD1,6/0,8")
      (footprint "eagle-import:1,6_0,8")
      (libsource (lib "eagle-import") (part "WIREPAD1,6/0,8"))
    )
    (comp (ref "PAD84")
      (value "WIREPAD1,6/0,8")
      (footprint "eagle-import:1,6_0,8")
      (libsource (lib "eagle-import") (part "WIREPAD1,6/0,8"))
    )
    (comp (ref "PAD85")
      (value "WIREPAD1,6/0,8")
      (footprint "eagle-import:1,6_0,8")
      (libsource (lib "eagle-import") (part "WIREPAD1,6/0,8"))
    )
    (comp (ref "PAD86")
      (value "WIREPAD1,6/0,8")
      (footprint "eagle-import:1,6_0,8")
      (libsource (lib "eagle-import") (part "WIREPAD1,6/0,8"))
    )
    (comp (ref "PAD87")
      (value "WIREPAD1,6/0,8")
      (footprint "eagle-import:1,6_0,8")
      (libsource (lib "eagle-import") (part "WIREPAD1,6/0,8"))
    )
    (comp (ref "PAD88")
      (value "WIREPAD1,6/0,8")
      (footprint "eagle-import:1,6_0,8")
      (libsource (lib "eagle-import") (part "WIREPAD1,6/0,8"))
    )
    (comp (ref "PAD89")
      (value "WIREPAD1,6/0,8")
      (footprint "eagle-import:1,6_0,8")
      (libsource (lib "eagle-import") (part "WIREPAD1,6/0,8"))
    )
    (comp (ref "PAD90")
      (value "WIREPAD1,6/0,8")
      (footprint "eagle-import:1,6_0,8")
      (libsource (lib "eagle-import") (part "WIREPAD1,6/0,8"))
    )
    (comp (ref "PAD91")
      (value "WIREPAD1,6/0,8")
      (footprint "eagle-import:1,6_0,8")
      (libsource (lib "eagle-import") (part "WIREPAD1,6/0,8"))
    )
  )
  (nets
    (net (code "1") (name "+3V3") (class "Default")
      (node (ref "C16") (pin "2") (pinfunction "2_2") (pintype "passive"))
      (node (ref "C22") (pin "2") (pinfunction "2_2") (pintype "passive"))
      (node (ref "C23") (pin "2") (pinfunction "2_2") (pintype "passive"))
      (node (ref "C24") (pin "2") (pinfunction "2_2") (pintype "passive"))
      (node (ref "C28") (pin "1") (pinfunction "1_1") (pintype "passive"))
      (node (ref "C3") (pin "1") (pinfunction "1_1") (pintype "passive"))
      (node (ref "C51") (pin "1") (pinfunction "1_1") (pintype "passive"))
      (node (ref "C52") (pin "1") (pinfunction "1_1") (pintype "passive"))
      (node (ref "C56") (pin "1") (pinfunction "1_1") (pintype "passive"))
      (node (ref "C58") (pin "1") (pinfunction "1_1") (pintype "passive"))
      (node (ref "C6") (pin "1") (pinfunction "1_1") (pintype "passive"))
      (node (ref "C61") (pin "1") (pinfunction "1_1") (pintype "passive"))
      (node (ref "C62") (pin "1") (pinfunction "1_1") (pintype "passive"))
      (node (ref "C64") (pin "1") (pinfunction "1_1") (pintype "passive"))
      (node (ref "C71") (pin "2") (pinfunction "2_2") (pintype "passive"))
      (node (ref "C72") (pin "2") (pinfunction "2_2") (pintype "passive"))
      (node (ref "IC3") (pin "3") (pinfunction "VCC_3") (pintype "power_in"))
      (node (ref "IC8") (pin "3") (pinfunction "VO_3") (pintype "passive"))
      (node (ref "J1") (pin "24") (pinfunction "MS_24") (pintype "passive"))
      (node (ref "J1") (pin "26") (pinfunction "MS_26") (pintype "passive"))
      (node (ref "JP1") (pin "8") (pinfunction "8_8") (pintype "passive"))
      (node (ref "L3") (pin "1") (pinfunction "2_1") (pintype "passive"))
      (node (ref "LED2") (pin "A") (pinfunction "A_A") (pintype "passive"))
      (node (ref "MCU") (pin "14") (pinfunction "VCC1_14") (pintype "power_in"))
      (node (ref "MCU") (pin "60") (pinfunction "VCC2_60") (pintype "power_in"))
      (node (ref "R1") (pin "2") (pinfunction "2_2") (pintype "passive"))
      (node (ref "R2") (pin "2") (pinfunction "2_2") (pintype "passive"))
      (node (ref "R23") (pin "1") (pinfunction "1_1") (pintype "passive"))
      (node (ref "R25") (pin "2") (pinfunction "2_2") (pintype "passive"))
      (node (ref "R27") (pin "2") (pinfunction "2_2") (pintype "passive"))
      (node (ref "R28") (pin "2") (pinfunction "2_2") (pintype "passive"))
      (node (ref "R44") (pin "1") (pinfunction "1_1") (pintype "passive"))
      (node (ref "R45") (pin "1") (pinfunction "1_1") (pintype "passive"))
      (node (ref "R46") (pin "1") (pinfunction "1_1") (pintype "passive"))
      (node (ref "R48") (pin "2") (pinfunction "2_2") (pintype "passive"))
      (node (ref "R53") (pin "2") (pinfunction "2_2") (pintype "passive"))
      (node (ref "R58") (pin "1") (pinfunction "1_1") (pintype "passive"))
      (node (ref "R61") (pin "2") (pinfunction "2_2") (pintype "passive"))
      (node (ref "R62") (pin "2") (pinfunction "2_2") (pintype "passive"))
      (node (ref "TP7") (pin "TP") (pinfunction "TP_TP") (pintype "input"))
      (node (ref "U$5") (pin "1") (pinfunction "DVDD_IO_1") (pintype "bidirectional"))
      (node (ref "U$5") (pin "6") (pinfunction "AVDD_6") (pintype "bidirectional"))
      (node (ref "U$6") (pin "1") (pinfunction "DVDD_IO_1") (pintype "bidirectional"))
      (node (ref "U$6") (pin "6") (pinfunction "AVDD_6") (pintype "bidirectional"))
      (node (ref "U1") (pin "19") (pinfunction "VCCB_19") (pintype "bidirectional"))
      (node (ref "U2") (pin "1") (pinfunction "VDDIO_1") (pintype "bidirectional"))
      (node (ref "U2") (pin "15") (pinfunction "RSVDV_15") (pintype "bidirectional"))
      (node (ref "U2") (pin "16") (pinfunction "VDD_16") (pintype "bidirectional"))
      (node (ref "X7") (pin "3") (pinfunction "3_3") (pintype "passive"))
    )
    (net (code "2") (name "+5V_PANDA") (class "Default")
      (node (ref "5V") (pin "1") (pinfunction "1_1") (pintype "passive"))
      (node (ref "C100") (pin "+") (pinfunction "+_+") (pintype "passive"))
      (node (ref "C29") (pin "1") (pinfunction "1_1") (pintype "passive"))
      (node (ref "C9") (pin "1") (pinfunction "1_1") (pintype "passive"))
      (node (ref "R37") (pin "1") (pinfunction "1_1") (pintype "passive"))
      (node (ref "TP55") (pin "TP") (pinfunction "TP_TP") (pintype "input"))
      (node (ref "U$100") (pin "P$2") (pinfunction "2_P$2") (pintype "passive"))
    )
    (net (code "3") (name "5V_MELEXIS") (class "Default")
      (node (ref "C30") (pin "1") (pinfunction "1_1") (pintype "passive"))
      (node (ref "C33") (pin "+") (pinfunction "+_+") (pintype "passive"))
      (node (ref "IC1") (pin "1") (pinfunction "FB\\SENSE_1") (pintype "input"))
      (node (ref "IC1") (pin "7") (pinfunction "OUT_7") (pintype "output"))
      (node (ref "IC1") (pin "8") (pinfunction "OUT_8") (pintype "passive"))
      (node (ref "J4") (pin "5") (pinfunction "MS_5") (pintype "passive"))
      (node (ref "J5") (pin "5") (pinfunction "MS_5") (pintype "passive"))
    )
    (net (code "4") (name "12V5") (class "Default")
      (node (ref "C49") (pin "1") (pinfunction "1_1") (pintype "passive"))
      (node (ref "C5") (pin "1") (pinfunction "1_1") (pintype "passive"))
      (node (ref "C53") (pin "1") (pinfunction "1_1") (pintype "passive"))
      (node (ref "C54") (pin "1") (pinfunction "1_1") (pintype "passive"))
      (node (ref "C59") (pin "1") (pinfunction "1_1") (pintype "passive"))
      (node (ref "D3") (pin "C") (pinfunction "C_C") (pintype "passive"))
      (node (ref "J1") (pin "29") (pinfunction "MS_29") (pintype "passive"))
      (node (ref "J1") (pin "3") (pinfunction "MS_3") (pintype "passive"))
      (node (ref "R14") (pin "2") (pinfunction "2_2") (pintype "passive"))
      (node (ref "TP52") (pin "TP") (pinfunction "TP_TP") (pintype "input"))
    )
    (net (code "5") (name "12V5VIN") (class "Default")
      (node (ref "C26") (pin "1") (pinfunction "1_1") (pintype "passive"))
      (node (ref "L2") (pin "2") (pinfunction "1_2") (pintype "passive"))
      (node (ref "Q2") (pin "3") (pinfunction "D_3") (pintype "passive"))
      (node (ref "TP10") (pin "TP") (pinfunction "TP_TP") (pintype "input"))
      (node (ref "U$2") (pin "4") (pinfunction "EN_4") (pintype "input"))
      (node (ref "U$2") (pin "5") (pinfunction "VIN_5") (pintype "power_in"))
    )
    (net (code "6") (name "400V") (class "Default")
      (node (ref "C36") (pin "1") (pinfunction "1_1") (pintype "passive"))
      (node (ref "D1") (pin "C") (pinfunction "C_C") (pintype "passive"))
      (node (ref "LSP1") (pin "MP") (pinfunction "MP_MP") (pintype "passive"))
      (node (ref "R57") (pin "2") (pinfunction "2_2") (pintype "passive"))
    )
    (net (code "7") (name "AN0") (class "Default")
      (node (ref "C8") (pin "1") (pinfunction "1_1") (pintype "passive"))
      (node (ref "MCU") (pin "95") (pinfunction "P100/AN00_95") (pintype "bidirectional"))
      (node (ref "R29") (pin "2") (pinfunction "2_2") (pintype "passive"))
      (node (ref "TP31") (pin "TP") (pinfunction "TP_TP") (pintype "input"))
    )
    (net (code "8") (name "AN1") (class "Default")
      (node (ref "C17") (pin "1") (pinfunction "1_1") (pintype "passive"))
      (node (ref "MCU") (pin "93") (pinfunction "P101/AN01_93") (pintype "bidirectional"))
      (node (ref "R12") (pin "2") (pinfunction "2_2") (pintype "passive"))
      (node (ref "TP37") (pin "TP") (pinfunction "TP_TP") (pintype "input"))
    )
    (net (code "9") (name "AN2") (class "Default")
      (node (ref "C7") (pin "1") (pinfunction "1_1") (pintype "passive"))
      (node (ref "CHGLED2") (pin "A") (pinfunction "A_A") (pintype "passive"))
      (node (ref "D4") (pin "3") (pinfunction "C_3") (pintype "passive"))
      (node (ref "MCU") (pin "92") (pinfunction "P102/AN02_92") (pintype "bidirectional"))
      (node (ref "R57") (pin "1") (pinfunction "1_1") (pintype "passive"))
    )
    (net (code "10") (name "AN3") (class "Default")
      (node (ref "C4") (pin "1") (pinfunction "1_1") (pintype "passive"))
      (node (ref "MCU") (pin "91") (pinfunction "P103/AN03_91") (pintype "bidirectional"))
      (node (ref "R50") (pin "2") (pinfunction "2_2") (pintype "passive"))
      (node (ref "R51") (pin "2") (pinfunction "2_2") (pintype "passive"))
    )
    (net (code "11") (name "BALL_DETECT") (class "Default")
      (node (ref "COILGUN") (pin "3") (pinfunction "3_3") (pintype "passive"))
      (node (ref "MCU") (pin "25") (pinfunction "P73/CTS2/RTS2/TA1IN/V/TX8_25") (pintype "bidirectional"))
    )
    (net (code "12") (name "BUTTON1") (class "Default")
      (node (ref "J6") (pin "21") (pinfunction "21_21") (pintype "passive"))
    )
    (net (code "13") (name "BUTTON2") (class "Default")
      (node (ref "J6") (pin "23") (pinfunction "23_23") (pintype "passive"))
    )
    (net (code "14") (name "BUZZER") (class "Default")
      (node (ref "MCU") (pin "54") (pinfunction "P36/A14/[A14/D14]_54") (pintype "bidirectional"))
      (node (ref "R47") (pin "2") (pinfunction "2_2") (pintype "passive"))
    )
    (net (code "15") (name "CHARGE") (class "Default")
      (node (ref "LED5") (pin "A") (pinfunction "A_A") (pintype "passive"))
      (node (ref "LT3750") (pin "3") (pinfunction "CH_3") (pintype "bidirectional"))
      (node (ref "MCU") (pin "76") (pinfunction "P12/D10/IIO02(12)_76") (pintype "bidirectional"))
      (node (ref "TP18") (pin "TP") (pinfunction "TP_TP") (pintype "input"))
    )
    (net (code "16") (name "CLK") (class "Default")
      (node (ref "U1") (pin "14") (pinfunction "B6_14") (pintype "bidirectional"))
      (node (ref "X7") (pin "5") (pinfunction "5_5") (pintype "passive"))
    )
    (net (code "17") (name "CLK0") (class "Default")
      (node (ref "MCU") (pin "35") (pinfunction "P61/CLKO/TB1IN_35") (pintype "bidirectional"))
      (node (ref "TP24") (pin "TP") (pinfunction "TP_TP") (pintype "input"))
      (node (ref "U$6") (pin "14") (pinfunction "SCL/SPC_14") (pintype "bidirectional"))
    )
    (net (code "18") (name "CLK2") (class "Default")
      (node (ref "MCU") (pin "26") (pinfunction "P72/CLK2/TA1OUT/V_26") (pintype "bidirectional"))
      (node (ref "TP25") (pin "TP") (pinfunction "TP_TP") (pintype "input"))
      (node (ref "U$5") (pin "14") (pinfunction "SCL/SPC_14") (pintype "bidirectional"))
    )
    (net (code "19") (name "CLK4") (class "Default")
      (node (ref "J4") (pin "3") (pinfunction "MS_3") (pintype "passive"))
      (node (ref "MCU") (pin "100") (pinfunction "P95/ANEX0/CLK4_100") (pintype "bidirectional"))
      (node (ref "TP60") (pin "TP") (pinfunction "TP_TP") (pintype "input"))
    )
    (net (code "20") (name "CLK6") (class "Default")
      (node (ref "MCU") (pin "47") (pinfunction "P45/CS2/A21/CLK6_47") (pintype "bidirectional"))
      (node (ref "TP38") (pin "TP") (pinfunction "TP_TP") (pintype "input"))
      (node (ref "U2") (pin "2") (pinfunction "SCL_2") (pintype "bidirectional"))
    )
    (net (code "21") (name "CLK_LCD") (class "Default")
      (node (ref "J1") (pin "13") (pinfunction "MS_13") (pintype "passive"))
      (node (ref "MCU") (pin "51") (pinfunction "P41/A17/CLK3_51") (pintype "bidirectional"))
      (node (ref "TP2") (pin "TP") (pinfunction "TP_TP") (pintype "input"))
    )
    (net (code "22") (name "CMD") (class "Default")
      (node (ref "U1") (pin "15") (pinfunction "B5_15") (pintype "bidirectional"))
      (node (ref "X7") (pin "2") (pinfunction "2_2") (pintype "passive"))
    )
    (net (code "23") (name "CNVSS") (class "Default")
      (node (ref "JP1") (pin "3") (pinfunction "3_3") (pintype "passive"))
      (node (ref "MCU") (pin "7") (pinfunction "CNVSS_7") (pintype "input"))
      (node (ref "R8") (pin "2") (pinfunction "2_2") (pintype "passive"))
    )
    (net (code "24") (name "CS0") (class "Default")
      (node (ref "MCU") (pin "36") (pinfunction "P60/CTSO/RTSO/TB0IN_36") (pintype "bidirectional"))
      (node (ref "TP51") (pin "TP") (pinfunction "TP_TP") (pintype "input"))
      (node (ref "U$6") (pin "7") (pinfunction "CS_7") (pintype "bidirectional"))
    )
    (net (code "25") (name "CS2") (class "Default")
      (node (ref "MCU") (pin "21") (pinfunction "P77/TA3IN/CLK5_21") (pintype "bidirectional"))
      (node (ref "TP49") (pin "TP") (pinfunction "TP_TP") (pintype "input"))
      (node (ref "U$5") (pin "7") (pinfunction "CS_7") (pintype "bidirectional"))
    )
    (net (code "26") (name "CS4") (class "Default")
      (node (ref "J4") (pin "4") (pinfunction "MS_4") (pintype "passive"))
      (node (ref "MCU") (pin "1") (pinfunction "P94/DA1/TB4IN/CTS4_1") (pintype "bidirectional"))
      (node (ref "TP61") (pin "TP") (pinfunction "TP_TP") (pintype "input"))
    )
    (net (code "27") (name "CS6") (class "Default")
      (node (ref "MCU") (pin "43") (pinfunction "P51/WR1/BC1_43") (pintype "bidirectional"))
      (node (ref "TP41") (pin "TP") (pinfunction "TP_TP") (pintype "input"))
      (node (ref "U2") (pin "5") (pinfunction "CS_5") (pintype "bidirectional"))
    )
    (net (code "28") (name "CS7") (class "Default")
      (node (ref "J5") (pin "4") (pinfunction "MS_4") (pintype "passive"))
      (node (ref "MCU") (pin "41") (pinfunction "P53/BCLK/CLKOUT_41") (pintype "bidirectional"))
      (node (ref "TP62") (pin "TP") (pinfunction "TP_TP") (pintype "input"))
    )
    (net (code "29") (name "CS_LCD") (class "Default")
      (node (ref "J1") (pin "19") (pinfunction "MS_19") (pintype "passive"))
      (node (ref "MCU") (pin "37") (pinfunction "P57/RDY/CS3/RTS7_37") (pintype "bidirectional"))
      (node (ref "TP4") (pin "TP") (pinfunction "TP_TP") (pintype "input"))
    )
    (net (code "30") (name "DAT0") (class "Default")
      (node (ref "U1") (pin "16") (pinfunction "B4_16") (pintype "bidirectional"))
      (node (ref "X7") (pin "7") (pinfunction "7_7") (pintype "passive"))
    )
    (net (code "31") (name "DAT1") (class "Default")
      (node (ref "U1") (pin "17") (pinfunction "B3_17") (pintype "bidirectional"))
      (node (ref "X7") (pin "8") (pinfunction "8_8") (pintype "passive"))
    )
    (net (code "32") (name "DAT2") (class "Default")
      (node (ref "U1") (pin "18") (pinfunction "B2_18") (pintype "bidirectional"))
      (node (ref "X7") (pin "9") (pinfunction "9_9") (pintype "passive"))
    )
    (net (code "33") (name "DAT3") (class "Default")
      (node (ref "U1") (pin "20") (pinfunction "B1_20") (pintype "bidirectional"))
      (node (ref "X7") (pin "1") (pinfunction "1_1") (pintype "passive"))
    )
    (net (code "34") (name "DAT_LCD") (class "Default")
      (node (ref "J1") (pin "12") (pinfunction "MS_12") (pintype "passive"))
      (node (ref "MCU") (pin "49") (pinfunction "P43/A19/TX3_49") (pintype "bidirectional"))
      (node (ref "TP1") (pin "TP") (pinfunction "TP_TP") (pintype "input"))
    )
    (net (code "35") (name "DC_LCD") (class "Default")
      (node (ref "J1") (pin "18") (pinfunction "MS_18") (pintype "passive"))
      (node (ref "MCU") (pin "52") (pinfunction "P40/A16/XTS3_52") (pintype "bidirectional"))
      (node (ref "TP3") (pin "TP") (pinfunction "TP_TP") (pintype "input"))
    )
    (net (code "36") (name "DONE") (class "Default")
      (node (ref "LT3750") (pin "2") (pinfunction "D_2") (pintype "bidirectional"))
      (node (ref "MCU") (pin "53") (pinfunction "P37/A15/[A15/D15]_53") (pintype "bidirectional"))
      (node (ref "R23") (pin "2") (pinfunction "2_2") (pintype "passive"))
      (node (ref "TP59") (pin "TP") (pinfunction "TP_TP") (pintype "input"))
    )
    (net (code "37") (name "E8_BUSY") (class "Default")
      (node (ref "JP1") (pin "9") (pinfunction "9_9") (pintype "passive"))
      (node (ref "MCU") (pin "32") (pinfunction "P64/CTS1/RTS1/CLKS1/SS1_32") (pintype "bidirectional"))
    )
    (net (code "38") (name "E8_CLK") (class "Default")
      (node (ref "JP1") (pin "1") (pinfunction "1_1") (pintype "passive"))
      (node (ref "MCU") (pin "31") (pinfunction "P65/CLK1_31") (pintype "bidirectional"))
    )
    (net (code "39") (name "E8_RX") (class "Default")
      (node (ref "JP1") (pin "11") (pinfunction "11_11") (pintype "passive"))
      (node (ref "MCU") (pin "30") (pinfunction "P66/RXD1/SCL1/STX1_30") (pintype "bidirectional"))
    )
    (net (code "40") (name "E8_TX") (class "Default")
      (node (ref "JP1") (pin "5") (pinfunction "5_5") (pintype "passive"))
      (node (ref "MCU") (pin "29") (pinfunction "P67/TXD1/SDA1/SRX1_29") (pintype "bidirectional"))
    )
    (net (code "41") (name "ENABLE_PANDA") (class "Default")
      (node (ref "MCU") (pin "55") (pinfunction "P35/A13/[A13/D13]_55") (pintype "bidirectional"))
      (node (ref "R35") (pin "2") (pinfunction "2_2") (pintype "passive"))
      (node (ref "TP53") (pin "TP") (pinfunction "TP_TP") (pintype "input"))
      (node (ref "U$3") (pin "3") (pinfunction "EN_3") (pintype "bidirectional"))
    )
    (net (code "42") (name "GND") (class "Default")
      (node (ref "10UF/16V") (pin "-") (pinfunction "-_-") (pintype "passive"))
      (node (ref "5V") (pin "2") (pinfunction "2_2") (pintype "passive"))
      (node (ref "C1") (pin "-") (pinfunction "-_-") (pintype "passive"))
      (node (ref "C100") (pin "-") (pinfunction "-_-") (pintype "passive"))
      (node (ref "C11") (pin "2") (pinfunction "2_2") (pintype "passive"))
      (node (ref "C12") (pin "-") (pinfunction "-_-") (pintype "passive"))
      (node (ref "C13") (pin "-") (pinfunction "-_-") (pintype "passive"))
      (node (ref "C14") (pin "-") (pinfunction "-_-") (pintype "passive"))
      (node (ref "C16") (pin "1") (pinfunction "1_1") (pintype "passive"))
      (node (ref "C17") (pin "2") (pinfunction "2_2") (pintype "passive"))
      (node (ref "C18") (pin "2") (pinfunction "2_2") (pintype "passive"))
      (node (ref "C19") (pin "2") (pinfunction "2_2") (pintype "passive"))
      (node (ref "C2") (pin "-") (pinfunction "-_-") (pintype "passive"))
      (node (ref "C22") (pin "1") (pinfunction "1_1") (pintype "passive"))
      (node (ref "C23") (pin "1") (pinfunction "1_1") (pintype "passive"))
      (node (ref "C24") (pin "1") (pinfunction "1_1") (pintype "passive"))
      (node (ref "C25") (pin "-") (pinfunction "-_-") (pintype "passive"))
      (node (ref "C26") (pin "2") (pinfunction "2_2") (pintype "passive"))
      (node (ref "C27") (pin "1") (pinfunction "1_1") (pintype "passive"))
      (node (ref "C28") (pin "2") (pinfunction "2_2") (pintype "passive"))
      (node (ref "C29") (pin "2") (pinfunction "2_2") (pintype "passive"))
      (node (ref "C3") (pin "2") (pinfunction "2_2") (pintype "passive"))
      (node (ref "C30") (pin "2") (pinfunction "2_2") (pintype "passive"))
      (node (ref "C31") (pin "2") (pinfunction "2_2") (pintype "passive"))
      (node (ref "C32") (pin "2") (pinfunction "2_2") (pintype "passive"))
      (node (ref "C33") (pin "-") (pinfunction "-_-") (pintype "passive"))
      (node (ref "C36") (pin "2") (pinfunction "2_2") (pintype "passive"))
      (node (ref "C4") (pin "2") (pinfunction "2_2") (pintype "passive"))
      (node (ref "C41") (pin "2") (pinfunction "2_2") (pintype "passive"))
      (node (ref "C45") (pin "2") (pinfunction "2_2") (pintype "passive"))
      (node (ref "C46") (pin "2") (pinfunction "2_2") (pintype "passive"))
      (node (ref "C48") (pin "2") (pinfunction "2_2") (pintype "passive"))
      (node (ref "C5") (pin "2") (pinfunction "2_2") (pintype "passive"))
      (node (ref "C51") (pin "2") (pinfunction "2_2") (pintype "passive"))
      (node (ref "C52") (pin "2") (pinfunction "2_2") (pintype "passive"))
      (node (ref "C53") (pin "2") (pinfunction "2_2") (pintype "passive"))
      (node (ref "C54") (pin "2") (pinfunction "2_2") (pintype "passive"))
      (node (ref "C55") (pin "2") (pinfunction "2_2") (pintype "passive"))
      (node (ref "C56") (pin "2") (pinfunction "2_2") (pintype "passive"))
      (node (ref "C58") (pin "2") (pinfunction "2_2") (pintype "passive"))
      (node (ref "C59") (pin "2") (pinfunction "2_2") (pintype "passive"))
      (node (ref "C6") (pin "2") (pinfunction "2_2") (pintype "passive"))
      (node (ref "C60") (pin "2") (pinfunction "2_2") (pintype "passive"))
      (node (ref "C61") (pin "2") (pinfunction "2_2") (pintype "passive"))
      (node (ref "C62") (pin "2") (pinfunction "2_2") (pintype "passive"))
      (node (ref "C63") (pin "2") (pinfunction "2_2") (pintype "passive"))
      (node (ref "C64") (pin "2") (pinfunction "2_2") (pintype "passive"))
      (node (ref "C7") (pin "2") (pinfunction "2_2") (pintype "passive"))
      (node (ref "C71") (pin "1") (pinfunction "1_1") (pintype "passive"))
      (node (ref "C72") (pin "1") (pinfunction "1_1") (pintype "passive"))
      (node (ref "C8") (pin "2") (pinfunction "2_2") (pintype "passive"))
      (node (ref "C9") (pin "2") (pinfunction "2_2") (pintype "passive"))
      (node (ref "CHGLED1") (pin "C") (pinfunction "C_C") (pintype "passive"))
      (node (ref "COILGUN") (pin "1") (pinfunction "1_1") (pintype "passive"))
      (node (ref "D100") (pin "1") (pinfunction "A_1") (pintype "passive"))
      (node (ref "D2") (pin "2") (pinfunction "C2_2") (pintype "passive"))
      (node (ref "D4") (pin "1") (pinfunction "A_1") (pintype "passive"))
      (node (ref "GND") (pin "1") (pinfunction "P_1") (pintype "passive"))
      (node (ref "GND78") (pin "1") (pinfunction "P_1") (pintype "passive"))
      (node (ref "IC1") (pin "4") (pinfunction "GND_4") (pintype "power_in"))
      (node (ref "IC2") (pin "18") (pinfunction "GNDB_18") (pintype "power_in"))
      (node (ref "IC2") (pin "19") (pinfunction "GNDB_19") (pintype "power_in"))
      (node (ref "IC2") (pin "20") (pinfunction "GNDB_20") (pintype "power_in"))
      (node (ref "IC2") (pin "26") (pinfunction "GNDA_26") (pintype "power_in"))
      (node (ref "IC2") (pin "27") (pinfunction "GNDA_27") (pintype "power_in"))
      (node (ref "IC2") (pin "28") (pinfunction "GNDA_28") (pintype "power_in"))
      (node (ref "IC3") (pin "1") (pinfunction "GND_1") (pintype "power_in"))
      (node (ref "IC6") (pin "18") (pinfunction "GNDB_18") (pintype "power_in"))
      (node (ref "IC6") (pin "19") (pinfunction "GNDB_19") (pintype "power_in"))
      (node (ref "IC6") (pin "20") (pinfunction "GNDB_20") (pintype "power_in"))
      (node (ref "IC6") (pin "26") (pinfunction "GNDA_26") (pintype "power_in"))
      (node (ref "IC6") (pin "27") (pinfunction "GNDA_27") (pintype "power_in"))
      (node (ref "IC6") (pin "28") (pinfunction "GNDA_28") (pintype "power_in"))
      (node (ref "IC8") (pin "2") (pinfunction "GND_2") (pintype "passive"))
      (node (ref "IC8") (pin "4") (pinfunction "GND_4") (pintype "passive"))
      (node (ref "J1") (pin "1") (pinfunction "MSV_1") (pintype "passive"))
      (node (ref "J1") (pin "10") (pinfunction "MS_10") (pintype "passive"))
      (node (ref "J1") (pin "14") (pinfunction "MS_14") (pintype "passive"))
      (node (ref "J1") (pin "15") (pinfunction "MS_15") (pintype "passive"))
      (node (ref "J1") (pin "16") (pinfunction "MS_16") (pintype "passive"))
      (node (ref "J1") (pin "17") (pinfunction "MS_17") (pintype "passive"))
      (node (ref "J1") (pin "2") (pinfunction "MS_2") (pintype "passive"))
      (node (ref "J1") (pin "28") (pinfunction "MS_28") (pintype "passive"))
      (node (ref "J1") (pin "30") (pinfunction "MS_30") (pintype "passive"))
      (node (ref "J1") (pin "4") (pinfunction "MS_4") (pintype "passive"))
      (node (ref "J1") (pin "5") (pinfunction "MS_5") (pintype "passive"))
      (node (ref "J1") (pin "6") (pinfunction "MS_6") (pintype "passive"))
      (node (ref "J1") (pin "7") (pinfunction "MS_7") (pintype "passive"))
      (node (ref "J1") (pin "8") (pinfunction "MS_8") (pintype "passive"))
      (node (ref "J1") (pin "9") (pinfunction "MS_9") (pintype "passive"))
      (node (ref "J3") (pin "27") (pinfunction "27_27") (pintype "passive"))
      (node (ref "J3") (pin "28") (pinfunction "28_28") (pintype "passive"))
      (node (ref "J4") (pin "1") (pinfunction "MS_1") (pintype "passive"))
      (node (ref "J4") (pin "6") (pinfunction "MS_6") (pintype "passive"))
      (node (ref "J5") (pin "1") (pinfunction "MS_1") (pintype "passive"))
      (node (ref "J5") (pin "6") (pinfunction "MS_6") (pintype "passive"))
      (node (ref "J6") (pin "7") (pinfunction "7_7") (pintype "passive"))
      (node (ref "J6") (pin "8") (pinfunction "8_8") (pintype "passive"))
      (node (ref "JP1") (pin "10") (pinfunction "10_10") (pintype "passive"))
      (node (ref "JP1") (pin "12") (pinfunction "12_12") (pintype "passive"))
      (node (ref "JP1") (pin "14") (pinfunction "14_14") (pintype "passive"))
      (node (ref "JP1") (pin "2") (pinfunction "2_2") (pintype "passive"))
      (node (ref "JP1") (pin "6") (pinfunction "6_6") (pintype "passive"))
      (node (ref "JP2") (pin "GND") (pinfunction "GND_GND") (pintype "bidirectional"))
      (node (ref "LSP2") (pin "MP") (pinfunction "MP_MP") (pintype "passive"))
      (node (ref "LT3750") (pin "5") (pinfunction "GND_5") (pintype "bidirectional"))
      (node (ref "MCU") (pin "12") (pinfunction "VSS_12") (pintype "power_in"))
      (node (ref "MCU") (pin "62") (pinfunction "VSS_62") (pintype "power_in"))
      (node (ref "MCU") (pin "94") (pinfunction "AVSS_94") (pintype "input"))
      (node (ref "PAD10") (pin "1") (pinfunction "P_1") (pintype "passive"))
      (node (ref "PAD11") (pin "1") (pinfunction "P_1") (pintype "passive"))
      (node (ref "PAD12") (pin "1") (pinfunction "P_1") (pintype "passive"))
      (node (ref "PAD13") (pin "1") (pinfunction "P_1") (pintype "passive"))
      (node (ref "PAD14") (pin "1") (pinfunction "P_1") (pintype "passive"))
      (node (ref "PAD15") (pin "1") (pinfunction "P_1") (pintype "passive"))
      (node (ref "PAD16") (pin "1") (pinfunction "P_1") (pintype "passive"))
      (node (ref "PAD17") (pin "1") (pinfunction "P_1") (pintype "passive"))
      (node (ref "PAD18") (pin "1") (pinfunction "P_1") (pintype "passive"))
      (node (ref "PAD19") (pin "1") (pinfunction "P_1") (pintype "passive"))
      (node (ref "PAD20") (pin "1") (pinfunction "P_1") (pintype "passive"))
      (node (ref "PAD21") (pin "1") (pinfunction "P_1") (pintype "passive"))
      (node (ref "PAD22") (pin "1") (pinfunction "P_1") (pintype "passive"))
      (node (ref "PAD23") (pin "1") (pinfunction "P_1") (pintype "passive"))
      (node (ref "PAD24") (pin "1") (pinfunction "P_1") (pintype "passive"))
      (node (ref "PAD3") (pin "1") (pinfunction "P_1") (pintype "passive"))
      (node (ref "PAD4") (pin "1") (pinfunction "P_1") (pintype "passive"))
      (node (ref "PAD7") (pin "1") (pinfunction "P_1") (pintype "passive"))
      (node (ref "PAD8") (pin "1") (pinfunction "P_1") (pintype "passive"))
      (node (ref "PAD9") (pin "1") (pinfunction "P_1") (pintype "passive"))
      (node (ref "PANDA") (pin "2") (pinfunction "2_2") (pintype "passive"))
      (node (ref "Q3") (pin "2") (pinfunction "E_2") (pintype "passive"))
      (node (ref "Q4") (pin "3") (pinfunction "D_3") (pintype "passive"))
      (node (ref "Q5") (pin "3") (pinfunction "D_3") (pintype "passive"))
      (node (ref "R10") (pin "1") (pinfunction "1_1") (pintype "passive"))
      (node (ref "R11") (pin "1") (pinfunction "1_1") (pintype "passive"))
      (node (ref "R13") (pin "2") (pinfunction "2_2") (pintype "passive"))
      (node (ref "R15") (pin "1") (pinfunction "1_1") (pintype "passive"))
      (node (ref "R18") (pin "2") (pinfunction "2_2") (pintype "passive"))
      (node (ref "R19") (pin "1") (pinfunction "1_1") (pintype "passive"))
      (node (ref "R20") (pin "2") (pinfunction "2_2") (pintype "passive"))
      (node (ref "R22") (pin "2") (pinfunction "2_2") (pintype "passive"))
      (node (ref "R26") (pin "2") (pinfunction "2_2") (pintype "passive"))
      (node (ref "R30") (pin "2") (pinfunction "2_2") (pintype "passive"))
      (node (ref "R35") (pin "1") (pinfunction "1_1") (pintype "passive"))
      (node (ref "R39") (pin "1") (pinfunction "1_1") (pintype "passive"))
      (node (ref "R40") (pin "1") (pinfunction "1_1") (pintype "passive"))
      (node (ref "R41") (pin "1") (pinfunction "1_1") (pintype "passive"))
      (node (ref "R42") (pin "1") (pinfunction "1_1") (pintype "passive"))
      (node (ref "R51") (pin "1") (pinfunction "1_1") (pintype "passive"))
      (node (ref "R56") (pin "1") (pinfunction "1_1") (pintype "passive"))
      (node (ref "R8") (pin "1") (pinfunction "1_1") (pintype "passive"))
      (node (ref "R9") (pin "1") (pinfunction "1_1") (pintype "passive"))
      (node (ref "SG2") (pin "2") (pinfunction "2_2") (pintype "passive"))
      (node (ref "U$1") (pin "1") (pinfunction "1_1") (pintype "bidirectional"))
      (node (ref "U$2") (pin "2") (pinfunction "GND_2") (pintype "power_in"))
      (node (ref "U$3") (pin "7") (pinfunction "GND_7") (pintype "bidirectional"))
      (node (ref "U$5") (pin "10") (pinfunction "NC_10") (pintype "bidirectional"))
      (node (ref "U$5") (pin "11") (pinfunction "NC_11") (pintype "bidirectional"))
      (node (ref "U$5") (pin "2") (pinfunction "GND_2") (pintype "bidirectional"))
      (node (ref "U$5") (pin "3") (pinfunction "NC_3") (pintype "bidirectional"))
      (node (ref "U$5") (pin "4") (pinfunction "IADDR0_4") (pintype "bidirectional"))
      (node (ref "U$5") (pin "5") (pinfunction "GND_5") (pintype "bidirectional"))
      (node (ref "U$6") (pin "10") (pinfunction "NC_10") (pintype "bidirectional"))
      (node (ref "U$6") (pin "11") (pinfunction "NC_11") (pintype "bidirectional"))
      (node (ref "U$6") (pin "2") (pinfunction "GND_2") (pintype "bidirectional"))
      (node (ref "U$6") (pin "3") (pinfunction "NC_3") (pintype "bidirectional"))
      (node (ref "U$6") (pin "4") (pinfunction "IADDR0_4") (pintype "bidirectional"))
      (node (ref "U$6") (pin "5") (pinfunction "GND_5") (pintype "bidirectional"))
      (node (ref "U1") (pin "11") (pinfunction "GND_11") (pintype "bidirectional"))
      (node (ref "U2") (pin "10") (pinfunction "RSVDG_10") (pintype "bidirectional"))
      (node (ref "U2") (pin "11") (pinfunction "RSDVG_11") (pintype "bidirectional"))
      (node (ref "U2") (pin "12") (pinfunction "RSVDG_12") (pintype "bidirectional"))
      (node (ref "U2") (pin "13") (pinfunction "GND_13") (pintype "bidirectional"))
      (node (ref "U2") (pin "8") (pinfunction "RSVDG_8") (pintype "bidirectional"))
      (node (ref "U2") (pin "9") (pinfunction "RSVDG_9") (pintype "bidirectional"))
      (node (ref "X4") (pin "GND") (pinfunction "GND_GND") (pintype "bidirectional"))
      (node (ref "X7") (pin "4") (pinfunction "4_4") (pintype "passive"))
      (node (ref "X7") (pin "6") (pinfunction "6_6") (pintype "passive"))
      (node (ref "X7") (pin "SW3") (pinfunction "SW3_SW3") (pintype "passive"))
      (node (ref "Y2") (pin "2") (pinfunction "2_2") (pintype "passive"))
    )
    (net (code "43") (name "HOLD") (class "Default")
      (node (ref "J5") (pin "3") (pinfunction "MS_3") (pintype "passive"))
      (node (ref "JP1") (pin "4") (pinfunction "4_4") (pintype "passive"))
      (node (ref "MCU") (pin "39") (pinfunction "P55/HOLD/CLK7_39") (pintype "bidirectional"))
      (node (ref "R1") (pin "1") (pinfunction "1_1") (pintype "passive"))
      (node (ref "TP64") (pin "TP") (pinfunction "TP_TP") (pintype "input"))
    )
    (net (code "44") (name "INT0") (class "Default")
      (node (ref "MCU") (pin "18") (pinfunction "P82/INT0_18") (pintype "bidirectional"))
      (node (ref "TP19") (pin "TP") (pinfunction "TP_TP") (pintype "input"))
      (node (ref "U$5") (pin "8") (pinfunction "INT1/DRDY_8") (pintype "bidirectional"))
      (node (ref "U$6") (pin "8") (pinfunction "INT1/DRDY_8") (pintype "bidirectional"))
    )
    (net (code "45") (name "INT1") (class "Default")
      (node (ref "MCU") (pin "17") (pinfunction "P83/INT1_17") (pintype "bidirectional"))
      (node (ref "TP43") (pin "TP") (pinfunction "TP_TP") (pintype "input"))
      (node (ref "U2") (pin "7") (pinfunction "INT1_7") (pintype "bidirectional"))
    )
    (net (code "46") (name "INT2") (class "Default")
      (node (ref "MCU") (pin "16") (pinfunction "P84/INT2_16") (pintype "bidirectional"))
      (node (ref "TP42") (pin "TP") (pinfunction "TP_TP") (pintype "input"))
      (node (ref "U2") (pin "6") (pinfunction "INT2_6") (pintype "bidirectional"))
    )
    (net (code "47") (name "JOY_CENT") (class "Default")
      (node (ref "JP2") (pin "CTR") (pinfunction "CENT_CTR") (pintype "bidirectional"))
      (node (ref "MCU") (pin "71") (pinfunction "P17/D15/INT5/IIO07(17)_71") (pintype "bidirectional"))
      (node (ref "TP46") (pin "TP") (pinfunction "TP_TP") (pintype "input"))
    )
    (net (code "48") (name "JOY_DOWN") (class "Default")
      (node (ref "JP2") (pin "D") (pinfunction "DOWN_D") (pintype "bidirectional"))
      (node (ref "MCU") (pin "74") (pinfunction "P14/D12/IIO04(14)_74") (pintype "bidirectional"))
      (node (ref "TP48") (pin "TP") (pinfunction "TP_TP") (pintype "input"))
    )
    (net (code "49") (name "JOY_LEFT") (class "Default")
      (node (ref "JP2") (pin "B") (pinfunction "LEFT_B") (pintype "bidirectional"))
      (node (ref "MCU") (pin "73") (pinfunction "P15/D13/INT3/IIO05(15)_73") (pintype "bidirectional"))
      (node (ref "TP44") (pin "TP") (pinfunction "TP_TP") (pintype "input"))
    )
    (net (code "50") (name "JOY_RIGHT") (class "Default")
      (node (ref "JP2") (pin "C") (pinfunction "RIGHT_C") (pintype "bidirectional"))
      (node (ref "MCU") (pin "72") (pinfunction "P16/D14/INT4/IIO06(16)_72") (pintype "bidirectional"))
      (node (ref "TP45") (pin "TP") (pinfunction "TP_TP") (pintype "input"))
    )
    (net (code "51") (name "JOY_UP") (class "Default")
      (node (ref "JP2") (pin "A") (pinfunction "UP_A") (pintype "bidirectional"))
      (node (ref "MCU") (pin "75") (pinfunction "P13/D11/IIO03(13)_75") (pintype "bidirectional"))
      (node (ref "TP47") (pin "TP") (pinfunction "TP_TP") (pintype "input"))
    )
    (net (code "52") (name "KICK") (class "Default")
      (node (ref "COILGUN") (pin "2") (pinfunction "2_2") (pintype "passive"))
      (node (ref "MCU") (pin "23") (pinfunction "P75/TA2IN/W/RX8_23") (pintype "bidirectional"))
    )
    (net (code "53") (name "LED1") (class "Default")
      (node (ref "LED1") (pin "A") (pinfunction "A_A") (pintype "passive"))
      (node (ref "MCU") (pin "57") (pinfunction "P33/A11/[A11/D11]_57") (pintype "bidirectional"))
    )
    (net (code "54") (name "LEFT_DIAGA") (class "Default")
      (node (ref "MCU") (pin "64") (pinfunction "P26/AN26/A6/[A6/D6]_64") (pintype "bidirectional"))
      (node (ref "R33") (pin "1") (pinfunction "1_1") (pintype "passive"))
      (node (ref "TP28") (pin "TP") (pinfunction "TP_TP") (pintype "input"))
    )
    (net (code "55") (name "LEFT_DIAGB") (class "Default")
      (node (ref "MCU") (pin "63") (pinfunction "P27/AN27/A7/[A7/D7]_63") (pintype "bidirectional"))
      (node (ref "R34") (pin "1") (pinfunction "1_1") (pintype "passive"))
      (node (ref "TP29") (pin "TP") (pinfunction "TP_TP") (pintype "input"))
    )
    (net (code "56") (name "LEFT_INA") (class "Default")
      (node (ref "MCU") (pin "68") (pinfunction "P22/AN22/A2/[A2/D2]_68") (pintype "bidirectional"))
      (node (ref "R31") (pin "1") (pinfunction "1_1") (pintype "passive"))
      (node (ref "TP26") (pin "TP") (pinfunction "TP_TP") (pintype "input"))
    )
    (net (code "57") (name "LEFT_INB") (class "Default")
      (node (ref "MCU") (pin "67") (pinfunction "P23/AN23/A3/[A3/D3]_67") (pintype "bidirectional"))
      (node (ref "R32") (pin "1") (pinfunction "1_1") (pintype "passive"))
      (node (ref "TP27") (pin "TP") (pinfunction "TP_TP") (pintype "input"))
    )
    (net (code "58") (name "LEFT_PWM") (class "Default")
      (node (ref "LED4") (pin "A") (pinfunction "A_A") (pintype "passive"))
      (node (ref "MCU") (pin "58") (pinfunction "P32/A10/[A10/D10]_58") (pintype "bidirectional"))
      (node (ref "R36") (pin "1") (pinfunction "1_1") (pintype "passive"))
      (node (ref "TP30") (pin "TP") (pinfunction "TP_TP") (pintype "input"))
    )
    (net (code "59") (name "LM2733FB") (class "Default")
      (node (ref "C49") (pin "2") (pinfunction "2_2") (pintype "passive"))
      (node (ref "R14") (pin "1") (pinfunction "1_1") (pintype "passive"))
      (node (ref "R15") (pin "2") (pinfunction "2_2") (pintype "passive"))
      (node (ref "TP50") (pin "TP") (pinfunction "TP_TP") (pintype "input"))
      (node (ref "U$2") (pin "3") (pinfunction "FB_3") (pintype "input"))
    )
    (net (code "60") (name "MELEXIS_EN") (class "Default")
      (node (ref "IC1") (pin "3") (pinfunction "~{EN}_3") (pintype "input"))
      (node (ref "MCU") (pin "61") (pinfunction "P30/A8/[A8/D8]_61") (pintype "bidirectional"))
      (node (ref "R58") (pin "2") (pinfunction "2_2") (pintype "passive"))
    )
    (net (code "61") (name "MOTOR1CS") (class "Default")
      (node (ref "IC2") (pin "9") (pinfunction "CS_9") (pintype "bidirectional"))
      (node (ref "R12") (pin "1") (pinfunction "1_1") (pintype "passive"))
      (node (ref "R13") (pin "1") (pinfunction "1_1") (pintype "passive"))
    )
    (net (code "62") (name "MOTOR1DIAGA") (class "Default")
      (node (ref "IC2") (pin "6") (pinfunction "DIAGA_6") (pintype "open_collector"))
      (node (ref "R25") (pin "1") (pinfunction "1_1") (pintype "passive"))
      (node (ref "R5") (pin "2") (pinfunction "2_2") (pintype "passive"))
    )
    (net (code "63") (name "MOTOR1DIAGB") (class "Default")
      (node (ref "IC2") (pin "10") (pinfunction "DIAGB_10") (pintype "open_collector"))
      (node (ref "R2") (pin "1") (pinfunction "1_1") (pintype "passive"))
      (node (ref "R6") (pin "2") (pinfunction "2_2") (pintype "passive"))
    )
    (net (code "64") (name "MOTOR1L") (class "Default")
      (node (ref "C20") (pin "1") (pinfunction "1_1") (pintype "passive"))
      (node (ref "C21") (pin "1") (pinfunction "1_1") (pintype "passive"))
      (node (ref "IC2") (pin "1") (pinfunction "OUTA_1") (pintype "output"))
      (node (ref "IC2") (pin "25") (pinfunction "OUTA_25") (pintype "passive"))
      (node (ref "IC2") (pin "30") (pinfunction "OUTA_30") (pintype "passive"))
      (node (ref "IC2") (pin "OUTA") (pinfunction "OUTA_OUTA") (pintype "passive"))
      (node (ref "IC2") (pin "OUTA@1") (pinfunction "OUTA_OUTA@1") (pintype "passive"))
      (node (ref "LED8") (pin "A") (pinfunction "A_A") (pintype "passive"))
      (node (ref "PAD1") (pin "1") (pinfunction "P_1") (pintype "passive"))
      (node (ref "PAD56") (pin "1") (pinfunction "P_1") (pintype "passive"))
      (node (ref "PAD57") (pin "1") (pinfunction "P_1") (pintype "passive"))
      (node (ref "PAD58") (pin "1") (pinfunction "P_1") (pintype "passive"))
      (node (ref "PAD59") (pin "1") (pinfunction "P_1") (pintype "passive"))
      (node (ref "PAD60") (pin "1") (pinfunction "P_1") (pintype "passive"))
      (node (ref "PAD61") (pin "1") (pinfunction "P_1") (pintype "passive"))
      (node (ref "PAD62") (pin "1") (pinfunction "P_1") (pintype "passive"))
      (node (ref "PAD63") (pin "1") (pinfunction "P_1") (pintype "passive"))
      (node (ref "PAD64") (pin "1") (pinfunction "P_1") (pintype "passive"))
    )
    (net (code "65") (name "MOTOR1PWM") (class "Default")
      (node (ref "IC2") (pin "8") (pinfunction "PWM_8") (pintype "input"))
      (node (ref "R7") (pin "2") (pinfunction "2_2") (pintype "passive"))
    )
    (net (code "66") (name "MOTOR1R") (class "Default")
      (node (ref "C20") (pin "2") (pinfunction "2_2") (pintype "passive"))
      (node (ref "C21") (pin "2") (pinfunction "2_2") (pintype "passive"))
      (node (ref "IC2") (pin "15") (pinfunction "OUTB_15") (pintype "output"))
      (node (ref "IC2") (pin "16") (pinfunction "OUTB_16") (pintype "passive"))
      (node (ref "IC2") (pin "21") (pinfunction "OUTB_21") (pintype "passive"))
      (node (ref "IC2") (pin "OUTB") (pinfunction "OUTB_OUTB") (pintype "passive"))
      (node (ref "IC2") (pin "OUTB@1") (pinfunction "OUTB_OUTB@1") (pintype "passive"))
      (node (ref "LED9") (pin "A") (pinfunction "A_A") (pintype "passive"))
      (node (ref "PAD2") (pin "1") (pinfunction "P_1") (pintype "passive"))
      (node (ref "PAD65") (pin "1") (pinfunction "P_1") (pintype "passive"))
      (node (ref "PAD66") (pin "1") (pinfunction "P_1") (pintype "passive"))
      (node (ref "PAD67") (pin "1") (pinfunction "P_1") (pintype "passive"))
      (node (ref "PAD68") (pin "1") (pinfunction "P_1") (pintype "passive"))
      (node (ref "PAD69") (pin "1") (pinfunction "P_1") (pintype "passive"))
      (node (ref "PAD70") (pin "1") (pinfunction "P_1") (pintype "passive"))
      (node (ref "PAD71") (pin "1") (pinfunction "P_1") (pintype "passive"))
      (node (ref "PAD72") (pin "1") (pinfunction "P_1") (pintype "passive"))
      (node (ref "PAD73") (pin "1") (pinfunction "P_1") (pintype "passive"))
    )
    (net (code "67") (name "MOTOR2CS") (class "Default")
      (node (ref "IC6") (pin "9") (pinfunction "CS_9") (pintype "bidirectional"))
      (node (ref "R29") (pin "1") (pinfunction "1_1") (pintype "passive"))
      (node (ref "R30") (pin "1") (pinfunction "1_1") (pintype "passive"))
    )
    (net (code "68") (name "MOTOR2DIAGA") (class "Default")
      (node (ref "IC6") (pin "6") (pinfunction "DIAGA_6") (pintype "open_collector"))
      (node (ref "R27") (pin "1") (pinfunction "1_1") (pintype "passive"))
      (node (ref "R33") (pin "2") (pinfunction "2_2") (pintype "passive"))
    )
    (net (code "69") (name "MOTOR2DIAGB") (class "Default")
      (node (ref "IC6") (pin "10") (pinfunction "DIAGB_10") (pintype "open_collector"))
      (node (ref "R28") (pin "1") (pinfunction "1_1") (pintype "passive"))
      (node (ref "R34") (pin "2") (pinfunction "2_2") (pintype "passive"))
    )
    (net (code "70") (name "MOTOR2INA") (class "Default")
      (node (ref "IC6") (pin "5") (pinfunction "INA_5") (pintype "input"))
      (node (ref "R31") (pin "2") (pinfunction "2_2") (pintype "passive"))
    )
    (net (code "71") (name "MOTOR2INB") (class "Default")
      (node (ref "IC6") (pin "11") (pinfunction "INB_11") (pintype "input"))
      (node (ref "R32") (pin "2") (pinfunction "2_2") (pintype "passive"))
    )
    (net (code "72") (name "MOTOR2L") (class "Default")
      (node (ref "C42") (pin "1") (pinfunction "1_1") (pintype "passive"))
      (node (ref "C43") (pin "1") (pinfunction "1_1") (pintype "passive"))
      (node (ref "IC6") (pin "1") (pinfunction "OUTA_1") (pintype "output"))
      (node (ref "IC6") (pin "25") (pinfunction "OUTA_25") (pintype "passive"))
      (node (ref "IC6") (pin "30") (pinfunction "OUTA_30") (pintype "passive"))
      (node (ref "IC6") (pin "OUTA") (pinfunction "OUTA_OUTA") (pintype "passive"))
      (node (ref "IC6") (pin "OUTA@1") (pinfunction "OUTA_OUTA@1") (pintype "passive"))
      (node (ref "LED6") (pin "A") (pinfunction "A_A") (pintype "passive"))
      (node (ref "PAD5") (pin "1") (pinfunction "P_1") (pintype "passive"))
      (node (ref "PAD74") (pin "1") (pinfunction "P_1") (pintype "passive"))
      (node (ref "PAD75") (pin "1") (pinfunction "P_1") (pintype "passive"))
      (node (ref "PAD76") (pin "1") (pinfunction "P_1") (pintype "passive"))
      (node (ref "PAD77") (pin "1") (pinfunction "P_1") (pintype "passive"))
      (node (ref "PAD78") (pin "1") (pinfunction "P_1") (pintype "passive"))
      (node (ref "PAD79") (pin "1") (pinfunction "P_1") (pintype "passive"))
      (node (ref "PAD80") (pin "1") (pinfunction "P_1") (pintype "passive"))
      (node (ref "PAD81") (pin "1") (pinfunction "P_1") (pintype "passive"))
      (node (ref "PAD82") (pin "1") (pinfunction "P_1") (pintype "passive"))
    )
    (net (code "73") (name "MOTOR2PWM") (class "Default")
      (node (ref "IC6") (pin "8") (pinfunction "PWM_8") (pintype "input"))
      (node (ref "R36") (pin "2") (pinfunction "2_2") (pintype "passive"))
    )
    (net (code "74") (name "MOTOR2R") (class "Default")
      (node (ref "C42") (pin "2") (pinfunction "2_2") (pintype "passive"))
      (node (ref "C43") (pin "2") (pinfunction "2_2") (pintype "passive"))
      (node (ref "IC6") (pin "15") (pinfunction "OUTB_15") (pintype "output"))
      (node (ref "IC6") (pin "16") (pinfunction "OUTB_16") (pintype "passive"))
      (node (ref "IC6") (pin "21") (pinfunction "OUTB_21") (pintype "passive"))
      (node (ref "IC6") (pin "OUTB") (pinfunction "OUTB_OUTB") (pintype "passive"))
      (node (ref "IC6") (pin "OUTB@1") (pinfunction "OUTB_OUTB@1") (pintype "passive"))
      (node (ref "LED7") (pin "A") (pinfunction "A_A") (pintype "passive"))
      (node (ref "PAD6") (pin "1") (pinfunction "P_1") (pintype "passive"))
      (node (ref "PAD83") (pin "1") (pinfunction "P_1") (pintype "passive"))
      (node (ref "PAD84") (pin "1") (pinfunction "P_1") (pintype "passive"))
      (node (ref "PAD85") (pin "1") (pinfunction "P_1") (pintype "passive"))
      (node (ref "PAD86") (pin "1") (pinfunction "P_1") (pintype "passive"))
      (node (ref "PAD87") (pin "1") (pinfunction "P_1") (pintype "passive"))
      (node (ref "PAD88") (pin "1") (pinfunction "P_1") (pintype "passive"))
      (node (ref "PAD89") (pin "1") (pinfunction "P_1") (pintype "passive"))
      (node (ref "PAD90") (pin "1") (pinfunction "P_1") (pintype "passive"))
      (node (ref "PAD91") (pin "1") (pinfunction "P_1") (pintype "passive"))
    )
    (net (code "75") (name "N$46") (class "Default")
      (node (ref "J1") (pin "22") (pinfunction "MS_22") (pintype "passive"))
      (node (ref "R18") (pin "1") (pinfunction "1_1") (pintype "passive"))
      (node (ref "TP9") (pin "TP") (pinfunction "TP_TP") (pintype "input"))
    )
    (net (code "76") (name "N$47") (class "Default")
      (node (ref "J1") (pin "27") (pinfunction "MS_27") (pintype "passive"))
      (node (ref "R17") (pin "2") (pinfunction "2_2") (pintype "passive"))
      (node (ref "TP8") (pin "TP") (pinfunction "TP_TP") (pintype "input"))
    )
    (net (code "77") (name "NSD") (class "Default")
      (node (ref "MCU") (pin "6") (pinfunction "NSD_6") (pintype "input"))
      (node (ref "R45") (pin "2") (pinfunction "2_2") (pintype "passive"))
    )
    (net (code "78") (name "Net-(C10-Pad2)") (class "Default")
      (node (ref "C10") (pin "2") (pinfunction "2_2") (pintype "passive"))
      (node (ref "R11") (pin "2") (pinfunction "2_2") (pintype "passive"))
    )
    (net (code "79") (name "Net-(C47-Pad2)") (class "Default")
      (node (ref "C47") (pin "2") (pinfunction "2_2") (pintype "passive"))
      (node (ref "R9") (pin "2") (pinfunction "2_2") (pintype "passive"))
    )
    (net (code "80") (name "Net-(CHGLED1-PadA)") (class "Default")
      (node (ref "CHGLED1") (pin "A") (pinfunction "A_A") (pintype "passive"))
      (node (ref "CHGLED2") (pin "C") (pinfunction "C_C") (pintype "passive"))
    )
    (net (code "81") (name "Net-(D1-PadA)") (class "Default")
      (node (ref "D1") (pin "A") (pinfunction "A_A") (pintype "passive"))
      (node (ref "U$1") (pin "12") (pinfunction "12_12") (pintype "bidirectional"))
    )
    (net (code "82") (name "Net-(D2-A1)") (class "Default")
      (node (ref "D2") (pin "1") (pinfunction "A1_1") (pintype "passive"))
      (node (ref "R17") (pin "1") (pinfunction "1_1") (pintype "passive"))
    )
    (net (code "83") (name "Net-(D100-C)") (class "Default")
      (node (ref "C15") (pin "1") (pinfunction "1_1") (pintype "passive"))
      (node (ref "D100") (pin "3") (pinfunction "C_3") (pintype "passive"))
      (node (ref "TP54") (pin "TP") (pinfunction "TP_TP") (pintype "input"))
      (node (ref "U$100") (pin "P$1") (pinfunction "1_P$1") (pintype "passive"))
      (node (ref "U$3") (pin "8") (pinfunction "PH_8") (pintype "bidirectional"))
    )
    (net (code "84") (name "Net-(IC2-INA)") (class "Default")
      (node (ref "IC2") (pin "5") (pinfunction "INA_5") (pintype "input"))
      (node (ref "R3") (pin "2") (pinfunction "2_2") (pintype "passive"))
    )
    (net (code "85") (name "Net-(IC2-INB)") (class "Default")
      (node (ref "IC2") (pin "11") (pinfunction "INB_11") (pintype "input"))
      (node (ref "R4") (pin "2") (pinfunction "2_2") (pintype "passive"))
    )
    (net (code "86") (name "Net-(L2-2)") (class "Default")
      (node (ref "D3") (pin "A") (pinfunction "A_A") (pintype "passive"))
      (node (ref "L2") (pin "1") (pinfunction "2_1") (pintype "passive"))
      (node (ref "U$2") (pin "1") (pinfunction "VOUT_1") (pintype "output"))
    )
    (net (code "87") (name "Net-(L3-1)") (class "Default")
      (node (ref "C55") (pin "1") (pinfunction "1_1") (pintype "passive"))
      (node (ref "L3") (pin "2") (pinfunction "1_2") (pintype "passive"))
      (node (ref "MCU") (pin "96") (pinfunction "VREF_96") (pintype "input"))
      (node (ref "MCU") (pin "97") (pinfunction "AVCC_97") (pintype "input"))
    )
    (net (code "88") (name "Net-(LED1-PadC)") (class "Default")
      (node (ref "LED1") (pin "C") (pinfunction "C_C") (pintype "passive"))
      (node (ref "R19") (pin "2") (pinfunction "2_2") (pintype "passive"))
    )
    (net (code "89") (name "Net-(LED2-PadC)") (class "Default")
      (node (ref "LED2") (pin "C") (pinfunction "C_C") (pintype "passive"))
      (node (ref "R10") (pin "2") (pinfunction "2_2") (pintype "passive"))
    )
    (net (code "90") (name "Net-(LED3-PadC)") (class "Default")
      (node (ref "LED3") (pin "C") (pinfunction "C_C") (pintype "passive"))
      (node (ref "R40") (pin "2") (pinfunction "2_2") (pintype "passive"))
    )
    (net (code "91") (name "Net-(LED4-PadC)") (class "Default")
      (node (ref "LED4") (pin "C") (pinfunction "C_C") (pintype "passive"))
      (node (ref "R39") (pin "2") (pinfunction "2_2") (pintype "passive"))
    )
    (net (code "92") (name "Net-(LED5-PadC)") (class "Default")
      (node (ref "LED5") (pin "C") (pinfunction "C_C") (pintype "passive"))
      (node (ref "R42") (pin "2") (pinfunction "2_2") (pintype "passive"))
    )
    (net (code "93") (name "Net-(LED6-PadC)") (class "Default")
      (node (ref "LED6") (pin "C") (pinfunction "C_C") (pintype "passive"))
      (node (ref "LED7") (pin "C") (pinfunction "C_C") (pintype "passive"))
      (node (ref "R41") (pin "2") (pinfunction "2_2") (pintype "passive"))
    )
    (net (code "94") (name "Net-(LED8-PadC)") (class "Default")
      (node (ref "LED8") (pin "C") (pinfunction "C_C") (pintype "passive"))
      (node (ref "LED9") (pin "C") (pinfunction "C_C") (pintype "passive"))
      (node (ref "R56") (pin "2") (pinfunction "2_2") (pintype "passive"))
    )
    (net (code "95") (name "Net-(LT3750-G)") (class "Default")
      (node (ref "LT3750") (pin "7") (pinfunction "G_7") (pintype "bidirectional"))
      (node (ref "TP15") (pin "TP") (pinfunction "TP_TP") (pintype "input"))
      (node (ref "U$102") (pin "4") (pinfunction "G_4") (pintype "passive"))
    )
    (net (code "96") (name "Net-(LT3750-RBG)") (class "Default")
      (node (ref "C32") (pin "1") (pinfunction "1_1") (pintype "passive"))
      (node (ref "LT3750") (pin "10") (pinfunction "RBG_10") (pintype "bidirectional"))
      (node (ref "R22") (pin "1") (pinfunction "1_1") (pintype "passive"))
      (node (ref "TP17") (pin "TP") (pinfunction "TP_TP") (pintype "input"))
    )
    (net (code "97") (name "Net-(LT3750-RD)") (class "Default")
      (node (ref "LT3750") (pin "8") (pinfunction "RD_8") (pintype "bidirectional"))
      (node (ref "R21") (pin "1") (pinfunction "1_1") (pintype "passive"))
      (node (ref "TP14") (pin "TP") (pinfunction "TP_TP") (pintype "input"))
    )
    (net (code "98") (name "Net-(LT3750-RV)") (class "Default")
      (node (ref "LT3750") (pin "9") (pinfunction "RV_9") (pintype "bidirectional"))
      (node (ref "R24") (pin "1") (pinfunction "1_1") (pintype "passive"))
      (node (ref "TP13") (pin "TP") (pinfunction "TP_TP") (pintype "input"))
    )
    (net (code "99") (name "Net-(LT3750-S)") (class "Default")
      (node (ref "LT3750") (pin "6") (pinfunction "S_6") (pintype "bidirectional"))
      (node (ref "R20") (pin "1") (pinfunction "1_1") (pintype "passive"))
      (node (ref "TP16") (pin "TP") (pinfunction "TP_TP") (pintype "input"))
      (node (ref "U$102") (pin "1") (pinfunction "S_1") (pintype "passive"))
      (node (ref "U$102") (pin "2") (pinfunction "S_2") (pintype "passive"))
      (node (ref "U$102") (pin "3") (pinfunction "S_3") (pintype "passive"))
    )
    (net (code "100") (name "Net-(MCU-P85{slash}NMI)") (class "Default")
      (node (ref "MCU") (pin "15") (pinfunction "P85/NMI_15") (pintype "input"))
      (node (ref "R44") (pin "2") (pinfunction "2_2") (pintype "passive"))
    )
    (net (code "101") (name "Net-(MCU-P86{slash}XCOUT)") (class "Default")
      (node (ref "MCU") (pin "9") (pinfunction "P86/XCOUT_9") (pintype "bidirectional"))
      (node (ref "Q1") (pin "4") (pinfunction "2_4") (pintype "passive"))
    )
    (net (code "102") (name "Net-(MCU-P87{slash}XCIN)") (class "Default")
      (node (ref "MCU") (pin "8") (pinfunction "P87/XCIN_8") (pintype "bidirectional"))
      (node (ref "Q1") (pin "1") (pinfunction "1_1") (pintype "passive"))
    )
    (net (code "103") (name "Net-(MCU-XIN)") (class "Default")
      (node (ref "MCU") (pin "13") (pinfunction "XIN_13") (pintype "input"))
      (node (ref "Y2") (pin "3") (pinfunction "3_3") (pintype "passive"))
    )
    (net (code "104") (name "Net-(MCU-XOUT)") (class "Default")
      (node (ref "MCU") (pin "11") (pinfunction "XOUT_11") (pintype "output"))
      (node (ref "Y2") (pin "1") (pinfunction "1_1") (pintype "passive"))
    )
    (net (code "105") (name "Net-(PAD25-P)") (class "Default")
      (node (ref "PAD25") (pin "1") (pinfunction "P_1") (pintype "passive"))
      (node (ref "R21") (pin "2") (pinfunction "2_2") (pintype "passive"))
      (node (ref "R24") (pin "2") (pinfunction "2_2") (pintype "passive"))
      (node (ref "TP12") (pin "TP") (pinfunction "TP_TP") (pintype "input"))
      (node (ref "U$1") (pin "3") (pinfunction "3_3") (pintype "bidirectional"))
      (node (ref "U$1") (pin "4") (pinfunction "4_4") (pintype "bidirectional"))
      (node (ref "U$1") (pin "5") (pinfunction "5_5") (pintype "bidirectional"))
      (node (ref "U$1") (pin "6") (pinfunction "6_6") (pintype "bidirectional"))
      (node (ref "U$102") (pin "5") (pinfunction "D_5") (pintype "passive"))
      (node (ref "U$102") (pin "6") (pinfunction "D_6") (pintype "passive"))
      (node (ref "U$102") (pin "7") (pinfunction "D_7") (pintype "passive"))
      (node (ref "U$102") (pin "8") (pinfunction "D_8") (pintype "passive"))
    )
    (net (code "106") (name "Net-(Q2-G)") (class "Default")
      (node (ref "Q2") (pin "1") (pinfunction "G_1") (pintype "passive"))
      (node (ref "Q3") (pin "3") (pinfunction "C_3") (pintype "passive"))
      (node (ref "R16") (pin "1") (pinfunction "1_1") (pintype "passive"))
    )
    (net (code "107") (name "Net-(R47-Pad1)") (class "Default")
      (node (ref "R47") (pin "1") (pinfunction "1_1") (pintype "passive"))
      (node (ref "SG2") (pin "1") (pinfunction "1_1") (pintype "passive"))
    )
    (net (code "108") (name "Net-(U$3-BOOT)") (class "Default")
      (node (ref "C15") (pin "2") (pinfunction "2_2") (pintype "passive"))
      (node (ref "U$3") (pin "1") (pinfunction "BOOT_1") (pintype "bidirectional"))
    )
    (net (code "109") (name "Net-(U$3-COMP)") (class "Default")
      (node (ref "C10") (pin "1") (pinfunction "1_1") (pintype "passive"))
      (node (ref "C11") (pin "1") (pinfunction "1_1") (pintype "passive"))
      (node (ref "U$3") (pin "6") (pinfunction "COMP_6") (pintype "bidirectional"))
    )
    (net (code "110") (name "Net-(U$3-SS)") (class "Default")
      (node (ref "C27") (pin "2") (pinfunction "2_2") (pintype "passive"))
      (node (ref "U$3") (pin "4") (pinfunction "SS_4") (pintype "bidirectional"))
    )
    (net (code "111") (name "Net-(U$3-VSENSE)") (class "Default")
      (node (ref "R26") (pin "1") (pinfunction "1_1") (pintype "passive"))
      (node (ref "R37") (pin "2") (pinfunction "2_2") (pintype "passive"))
      (node (ref "TP56") (pin "TP") (pinfunction "TP_TP") (pintype "input"))
      (node (ref "U$3") (pin "5") (pinfunction "VSENSE_5") (pintype "bidirectional"))
    )
    (net (code "112") (name "Net-(U2-PLL)") (class "Default")
      (node (ref "C47") (pin "1") (pinfunction "1_1") (pintype "passive"))
      (node (ref "C48") (pin "1") (pinfunction "1_1") (pintype "passive"))
      (node (ref "U2") (pin "14") (pinfunction "PLL_14") (pintype "bidirectional"))
    )
    (net (code "113") (name "OLED_ENA") (class "Default")
      (node (ref "MCU") (pin "48") (pinfunction "P44/CS3/A20/RTS6_48") (pintype "bidirectional"))
      (node (ref "Q3") (pin "1") (pinfunction "B_1") (pintype "passive"))
      (node (ref "TP11") (pin "TP") (pinfunction "TP_TP") (pintype "input"))
    )
    (net (code "114") (name "RESET") (class "Default")
      (node (ref "IC3") (pin "2") (pinfunction "~{RES}_2") (pintype "output"))
      (node (ref "JP1") (pin "13") (pinfunction "13_13") (pintype "passive"))
      (node (ref "MCU") (pin "10") (pinfunction "RESET_10") (pintype "input"))
      (node (ref "R46") (pin "2") (pinfunction "2_2") (pintype "passive"))
    )
    (net (code "115") (name "RES_LCD") (class "Default")
      (node (ref "J1") (pin "20") (pinfunction "MS_20") (pintype "passive"))
      (node (ref "MCU") (pin "50") (pinfunction "P42/A18/RX3_50") (pintype "bidirectional"))
      (node (ref "TP5") (pin "TP") (pinfunction "TP_TP") (pintype "input"))
    )
    (net (code "116") (name "RIGHT_DIAGA") (class "Default")
      (node (ref "MCU") (pin "66") (pinfunction "P24/AN24/A4/[A4/D4]_66") (pintype "bidirectional"))
      (node (ref "R5") (pin "1") (pinfunction "1_1") (pintype "passive"))
      (node (ref "TP34") (pin "TP") (pinfunction "TP_TP") (pintype "input"))
    )
    (net (code "117") (name "RIGHT_DIAGB") (class "Default")
      (node (ref "MCU") (pin "65") (pinfunction "P25/AN25/A5/[A5/D5]_65") (pintype "bidirectional"))
      (node (ref "R6") (pin "1") (pinfunction "1_1") (pintype "passive"))
      (node (ref "TP35") (pin "TP") (pinfunction "TP_TP") (pintype "input"))
    )
    (net (code "118") (name "RIGHT_INA") (class "Default")
      (node (ref "MCU") (pin "70") (pinfunction "P20/AN20/A0/[A0/D0]/BC0_70") (pintype "bidirectional"))
      (node (ref "R3") (pin "1") (pinfunction "1_1") (pintype "passive"))
      (node (ref "TP32") (pin "TP") (pinfunction "TP_TP") (pintype "input"))
    )
    (net (code "119") (name "RIGHT_INB") (class "Default")
      (node (ref "MCU") (pin "69") (pinfunction "P21/AN21/A1/[A1/D1]_69") (pintype "bidirectional"))
      (node (ref "R4") (pin "1") (pinfunction "1_1") (pintype "passive"))
      (node (ref "TP33") (pin "TP") (pinfunction "TP_TP") (pintype "input"))
    )
    (net (code "120") (name "RIGHT_PWM") (class "Default")
      (node (ref "LED3") (pin "A") (pinfunction "A_A") (pintype "passive"))
      (node (ref "MCU") (pin "56") (pinfunction "P34/A12/[A12/D12]_56") (pintype "bidirectional"))
      (node (ref "R7") (pin "1") (pinfunction "1_1") (pintype "passive"))
      (node (ref "TP36") (pin "TP") (pinfunction "TP_TP") (pintype "input"))
    )
    (net (code "121") (name "RX0") (class "Default")
      (node (ref "MCU") (pin "34") (pinfunction "P62/RXDO/SCL0/STX0_34") (pintype "bidirectional"))
      (node (ref "TP23") (pin "TP") (pinfunction "TP_TP") (pintype "input"))
      (node (ref "U$6") (pin "12") (pinfunction "SDO_12") (pintype "bidirectional"))
    )
    (net (code "122") (name "RX2") (class "Default")
      (node (ref "MCU") (pin "27") (pinfunction "P71/RXD2/SCL2/TA0IN/TB5IN/SX2_27") (pintype "bidirectional"))
      (node (ref "R62") (pin "1") (pinfunction "1_1") (pintype "passive"))
      (node (ref "TP20") (pin "TP") (pinfunction "TP_TP") (pintype "input"))
      (node (ref "U$5") (pin "12") (pinfunction "SDO_12") (pintype "bidirectional"))
    )
    (net (code "123") (name "RX4") (class "Default")
      (node (ref "J4") (pin "2") (pinfunction "MS_2") (pintype "passive"))
      (node (ref "MCU") (pin "98") (pinfunction "P97/ADTRG/RX4/SCL4_98") (pintype "bidirectional"))
      (node (ref "Q4") (pin "2") (pinfunction "S_2") (pintype "passive"))
      (node (ref "R48") (pin "1") (pinfunction "1_1") (pintype "passive"))
      (node (ref "TP58") (pin "TP") (pinfunction "TP_TP") (pintype "input"))
    )
    (net (code "124") (name "RX5") (class "Default")
      (node (ref "MCU") (pin "20") (pinfunction "P80/TA4OUT/U/RX5_20") (pintype "bidirectional"))
      (node (ref "PANDA") (pin "1") (pinfunction "1_1") (pintype "passive"))
    )
    (net (code "125") (name "RX6") (class "Default")
      (node (ref "MCU") (pin "46") (pinfunction "P46/CS1/A22/RX6_46") (pintype "bidirectional"))
      (node (ref "TP40") (pin "TP") (pinfunction "TP_TP") (pintype "input"))
      (node (ref "U2") (pin "4") (pinfunction "SDO_4") (pintype "bidirectional"))
    )
    (net (code "126") (name "RX7") (class "Default")
      (node (ref "J5") (pin "2") (pinfunction "MS_2") (pintype "passive"))
      (node (ref "MCU") (pin "38") (pinfunction "P56/ALE/RX7_38") (pintype "bidirectional"))
      (node (ref "Q5") (pin "2") (pinfunction "S_2") (pintype "passive"))
      (node (ref "R53") (pin "1") (pinfunction "1_1") (pintype "passive"))
      (node (ref "TP65") (pin "TP") (pinfunction "TP_TP") (pintype "input"))
    )
    (net (code "127") (name "SDMMC2_CD") (class "Default")
      (node (ref "J6") (pin "25") (pinfunction "25_25") (pintype "passive"))
      (node (ref "R59") (pin "1") (pinfunction "1_1") (pintype "passive"))
      (node (ref "X7") (pin "SW1") (pinfunction "SW1_SW1") (pintype "passive"))
    )
    (net (code "128") (name "SDMMC2_CLK") (class "Default")
      (node (ref "J3") (pin "21") (pinfunction "21_21") (pintype "passive"))
      (node (ref "U1") (pin "7") (pinfunction "A6_7") (pintype "bidirectional"))
    )
    (net (code "129") (name "SDMMC2_CMD") (class "Default")
      (node (ref "J3") (pin "19") (pinfunction "19_19") (pintype "passive"))
      (node (ref "U1") (pin "6") (pinfunction "A5_6") (pintype "bidirectional"))
    )
    (net (code "130") (name "SDMMC2_DAT0") (class "Default")
      (node (ref "J3") (pin "17") (pinfunction "17_17") (pintype "passive"))
      (node (ref "U1") (pin "5") (pinfunction "A4_5") (pintype "bidirectional"))
    )
    (net (code "131") (name "SDMMC2_DAT1") (class "Default")
      (node (ref "J3") (pin "15") (pinfunction "15_15") (pintype "passive"))
      (node (ref "U1") (pin "4") (pinfunction "A3_4") (pintype "bidirectional"))
    )
    (net (code "132") (name "SDMMC2_DAT2") (class "Default")
      (node (ref "J3") (pin "13") (pinfunction "13_13") (pintype "passive"))
      (node (ref "U1") (pin "3") (pinfunction "A2_3") (pintype "bidirectional"))
    )
    (net (code "133") (name "SDMMC2_DAT3") (class "Default")
      (node (ref "J3") (pin "11") (pinfunction "11_11") (pintype "passive"))
      (node (ref "U1") (pin "1") (pinfunction "A1_1") (pintype "bidirectional"))
    )
    (net (code "134") (name "SDMMC2_WP") (class "Default")
      (node (ref "J6") (pin "27") (pinfunction "27_27") (pintype "passive"))
      (node (ref "R60") (pin "1") (pinfunction "1_1") (pintype "passive"))
      (node (ref "X7") (pin "SW2") (pinfunction "SW2_SW2") (pintype "passive"))
    )
    (net (code "135") (name "TX0") (class "Default")
      (node (ref "MCU") (pin "33") (pinfunction "P63/TXDO/SDA0/SRX0_33") (pintype "bidirectional"))
      (node (ref "TP22") (pin "TP") (pinfunction "TP_TP") (pintype "input"))
      (node (ref "U$6") (pin "13") (pinfunction "SDA/SDI/SDO_13") (pintype "bidirectional"))
    )
    (net (code "136") (name "TX2") (class "Default")
      (node (ref "MCU") (pin "28") (pinfunction "P70/TXD2/SDA2/TA0OUT/SRX2_28") (pintype "bidirectional"))
      (node (ref "R61") (pin "1") (pinfunction "1_1") (pintype "passive"))
      (node (ref "TP21") (pin "TP") (pinfunction "TP_TP") (pintype "input"))
      (node (ref "U$5") (pin "13") (pinfunction "SDA/SDI/SDO_13") (pintype "bidirectional"))
    )
    (net (code "137") (name "TX4") (class "Default")
      (node (ref "MCU") (pin "99") (pinfunction "P96/ANEX1/TX4/SDA4_99") (pintype "bidirectional"))
      (node (ref "Q4") (pin "1") (pinfunction "G_1") (pintype "passive"))
      (node (ref "TP57") (pin "TP") (pinfunction "TP_TP") (pintype "input"))
    )
    (net (code "138") (name "TX5") (class "Default")
      (node (ref "MCU") (pin "22") (pinfunction "P76/TA3OUT/TX5_22") (pintype "bidirectional"))
      (node (ref "PANDA") (pin "3") (pinfunction "3_3") (pintype "passive"))
    )
    (net (code "139") (name "TX6") (class "Default")
      (node (ref "MCU") (pin "45") (pinfunction "P47/CS0/A23/TX6_45") (pintype "bidirectional"))
      (node (ref "TP39") (pin "TP") (pinfunction "TP_TP") (pintype "input"))
      (node (ref "U2") (pin "3") (pinfunction "SDA/SDI_3") (pintype "bidirectional"))
    )
    (net (code "140") (name "TX7") (class "Default")
      (node (ref "MCU") (pin "40") (pinfunction "P54/HLDA/TX7_40") (pintype "bidirectional"))
      (node (ref "Q5") (pin "1") (pinfunction "G_1") (pintype "passive"))
      (node (ref "TP63") (pin "TP") (pinfunction "TP_TP") (pintype "input"))
    )
    (net (code "141") (name "USBH3_DM") (class "Default")
      (node (ref "J6") (pin "3") (pinfunction "3_3") (pintype "passive"))
      (node (ref "X4") (pin "D-") (pinfunction "D-_D-") (pintype "bidirectional"))
    )
    (net (code "142") (name "USBH3_DP") (class "Default")
      (node (ref "J6") (pin "5") (pinfunction "5_5") (pintype "passive"))
      (node (ref "X4") (pin "D+") (pinfunction "D+_D+") (pintype "bidirectional"))
    )
    (net (code "143") (name "USBH4_DM") (class "Default")
      (node (ref "J6") (pin "4") (pinfunction "4_4") (pintype "passive"))
    )
    (net (code "144") (name "USBH4_DP") (class "Default")
      (node (ref "J6") (pin "6") (pinfunction "6_6") (pintype "passive"))
    )
    (net (code "145") (name "VBAT") (class "Default")
      (node (ref "10UF/16V") (pin "+") (pinfunction "+_+") (pintype "passive"))
      (node (ref "C1") (pin "+") (pinfunction "+_+") (pintype "passive"))
      (node (ref "C12") (pin "+") (pinfunction "+_+") (pintype "passive"))
      (node (ref "C13") (pin "+") (pinfunction "+_+") (pintype "passive"))
      (node (ref "C14") (pin "+") (pinfunction "+_+") (pintype "passive"))
      (node (ref "C18") (pin "1") (pinfunction "1_1") (pintype "passive"))
      (node (ref "C19") (pin "1") (pinfunction "1_1") (pintype "passive"))
      (node (ref "C2") (pin "+") (pinfunction "+_+") (pintype "passive"))
      (node (ref "C25") (pin "+") (pinfunction "+_+") (pintype "passive"))
      (node (ref "C31") (pin "1") (pinfunction "1_1") (pintype "passive"))
      (node (ref "C41") (pin "1") (pinfunction "1_1") (pintype "passive"))
      (node (ref "C45") (pin "1") (pinfunction "1_1") (pintype "passive"))
      (node (ref "C46") (pin "1") (pinfunction "1_1") (pintype "passive"))
      (node (ref "COILGUN") (pin "4") (pinfunction "4_4") (pintype "passive"))
      (node (ref "IC1") (pin "5") (pinfunction "IN_5") (pintype "input"))
      (node (ref "IC1") (pin "6") (pinfunction "IN_6") (pintype "input"))
      (node (ref "IC2") (pin "13") (pinfunction "VCC_13") (pintype "power_in"))
      (node (ref "IC2") (pin "23") (pinfunction "VCC_23") (pintype "power_in"))
      (node (ref "IC2") (pin "3") (pinfunction "VCC_3") (pintype "power_in"))
      (node (ref "IC2") (pin "VCC") (pinfunction "VCC_VCC") (pintype "power_in"))
      (node (ref "IC2") (pin "VCC@1") (pinfunction "VCC_VCC@1") (pintype "power_in"))
      (node (ref "IC6") (pin "13") (pinfunction "VCC_13") (pintype "power_in"))
      (node (ref "IC6") (pin "23") (pinfunction "VCC_23") (pintype "power_in"))
      (node (ref "IC6") (pin "3") (pinfunction "VCC_3") (pintype "power_in"))
      (node (ref "IC6") (pin "VCC") (pinfunction "VCC_VCC") (pintype "power_in"))
      (node (ref "IC6") (pin "VCC@1") (pinfunction "VCC_VCC@1") (pintype "power_in"))
      (node (ref "IC8") (pin "1") (pinfunction "VIN_1") (pintype "input"))
      (node (ref "LT3750") (pin "1") (pinfunction "VT_1") (pintype "bidirectional"))
      (node (ref "LT3750") (pin "4") (pinfunction "VCC_4") (pintype "bidirectional"))
      (node (ref "PAD26") (pin "1") (pinfunction "P_1") (pintype "passive"))
      (node (ref "PAD27") (pin "1") (pinfunction "P_1") (pintype "passive"))
      (node (ref "PAD28") (pin "1") (pinfunction "P_1") (pintype "passive"))
      (node (ref "PAD29") (pin "1") (pinfunction "P_1") (pintype "passive"))
      (node (ref "PAD30") (pin "1") (pinfunction "P_1") (pintype "passive"))
      (node (ref "PAD31") (pin "1") (pinfunction "P_1") (pintype "passive"))
      (node (ref "PAD32") (pin "1") (pinfunction "P_1") (pintype "passive"))
      (node (ref "PAD33") (pin "1") (pinfunction "P_1") (pintype "passive"))
      (node (ref "PAD34") (pin "1") (pinfunction "P_1") (pintype "passive"))
      (node (ref "PAD35") (pin "1") (pinfunction "P_1") (pintype "passive"))
      (node (ref "PAD36") (pin "1") (pinfunction "P_1") (pintype "passive"))
      (node (ref "PAD37") (pin "1") (pinfunction "P_1") (pintype "passive"))
      (node (ref "PAD38") (pin "1") (pinfunction "P_1") (pintype "passive"))
      (node (ref "PAD39") (pin "1") (pinfunction "P_1") (pintype "passive"))
      (node (ref "PAD40") (pin "1") (pinfunction "P_1") (pintype "passive"))
      (node (ref "PAD41") (pin "1") (pinfunction "P_1") (pintype "passive"))
      (node (ref "PAD42") (pin "1") (pinfunction "P_1") (pintype "passive"))
      (node (ref "PAD43") (pin "1") (pinfunction "P_1") (pintype "passive"))
      (node (ref "PAD44") (pin "1") (pinfunction "P_1") (pintype "passive"))
      (node (ref "PAD45") (pin "1") (pinfunction "P_1") (pintype "passive"))
      (node (ref "PAD46") (pin "1") (pinfunction "P_1") (pintype "passive"))
      (node (ref "PAD47") (pin "1") (pinfunction "P_1") (pintype "passive"))
      (node (ref "PAD48") (pin "1") (pinfunction "P_1") (pintype "passive"))
      (node (ref "PAD49") (pin "1") (pinfunction "P_1") (pintype "passive"))
      (node (ref "PAD50") (pin "1") (pinfunction "P_1") (pintype "passive"))
      (node (ref "PAD51") (pin "1") (pinfunction "P_1") (pintype "passive"))
      (node (ref "PAD52") (pin "1") (pinfunction "P_1") (pintype "passive"))
      (node (ref "PAD53") (pin "1") (pinfunction "P_1") (pintype "passive"))
      (node (ref "PAD54") (pin "1") (pinfunction "P_1") (pintype "passive"))
      (node (ref "PAD55") (pin "1") (pinfunction "P_1") (pintype "passive"))
      (node (ref "Q2") (pin "2") (pinfunction "S_2") (pintype "passive"))
      (node (ref "R16") (pin "2") (pinfunction "2_2") (pintype "passive"))
      (node (ref "R50") (pin "1") (pinfunction "1_1") (pintype "passive"))
      (node (ref "U$1") (pin "10") (pinfunction "10_10") (pintype "bidirectional"))
      (node (ref "U$1") (pin "7") (pinfunction "7_7") (pintype "bidirectional"))
      (node (ref "U$1") (pin "8") (pinfunction "8_8") (pintype "bidirectional"))
      (node (ref "U$1") (pin "9") (pinfunction "9_9") (pintype "bidirectional"))
      (node (ref "U$3") (pin "2") (pinfunction "VIN_2") (pintype "bidirectional"))
      (node (ref "VBAT") (pin "1") (pinfunction "P_1") (pintype "passive"))
    )
    (net (code "146") (name "VBUS_3") (class "Default")
      (node (ref "J6") (pin "1") (pinfunction "1_1") (pintype "passive"))
      (node (ref "X4") (pin "VBUS") (pinfunction "VBUS_VBUS") (pintype "bidirectional"))
    )
    (net (code "147") (name "VBUS_4") (class "Default")
      (node (ref "J6") (pin "2") (pinfunction "2_2") (pintype "passive"))
    )
    (net (code "148") (name "VCORE") (class "Default")
      (node (ref "C60") (pin "1") (pinfunction "1_1") (pintype "passive"))
      (node (ref "C63") (pin "1") (pinfunction "1_1") (pintype "passive"))
      (node (ref "J1") (pin "25") (pinfunction "MS_25") (pintype "passive"))
      (node (ref "TP6") (pin "TP") (pinfunction "TP_TP") (pintype "input"))
    )
    (net (code "149") (name "VDC0") (class "Default")
      (node (ref "C57") (pin "2") (pinfunction "2_2") (pintype "passive"))
      (node (ref "MCU") (pin "3") (pinfunction "VDC0_3") (pintype "power_in"))
    )
    (net (code "150") (name "VDC1") (class "Default")
      (node (ref "C57") (pin "1") (pinfunction "1_1") (pintype "passive"))
      (node (ref "MCU") (pin "5") (pinfunction "VDC1_5") (pintype "power_in"))
    )
    (net (code "151") (name "VIO_1V8") (class "Default")
      (node (ref "J3") (pin "1") (pinfunction "1_1") (pintype "passive"))
      (node (ref "R59") (pin "2") (pinfunction "2_2") (pintype "passive"))
      (node (ref "R60") (pin "2") (pinfunction "2_2") (pintype "passive"))
      (node (ref "U1") (pin "10") (pinfunction "OE_10") (pintype "bidirectional"))
      (node (ref "U1") (pin "2") (pinfunction "VCCA_2") (pintype "bidirectional"))
    )
    (net (code "152") (name "WR") (class "Default")
      (node (ref "JP1") (pin "7") (pinfunction "7_7") (pintype "passive"))
      (node (ref "MCU") (pin "44") (pinfunction "P50/WR0/WR_44") (pintype "bidirectional"))
    )
    (net (code "153") (name "unconnected-(D2-C1A2-Pad3)") (class "Default")
      (node (ref "D2") (pin "3") (pinfunction "C1A2_3") (pintype "passive"))
    )
    (net (code "154") (name "unconnected-(IC1-~{RESET}-Pad2)") (class "Default")
      (node (ref "IC1") (pin "2") (pinfunction "~{RESET}_2") (pintype "input"))
    )
    (net (code "155") (name "unconnected-(J1C-MS-Pad11)") (class "Default")
      (node (ref "J1") (pin "11") (pinfunction "MS_11") (pintype "passive"))
    )
    (net (code "156") (name "unconnected-(J1N-MS-Pad21)") (class "Default")
      (node (ref "J1") (pin "21") (pinfunction "MS_21") (pintype "passive"))
    )
    (net (code "157") (name "unconnected-(J1P-MS-Pad23)") (class "Default")
      (node (ref "J1") (pin "23") (pinfunction "MS_23") (pintype "passive"))
    )
    (net (code "158") (name "unconnected-(J3-Pad2)") (class "Default")
      (node (ref "J3") (pin "2") (pinfunction "2_2") (pintype "passive"))
    )
    (net (code "159") (name "unconnected-(J3-Pad3)") (class "Default")
      (node (ref "J3") (pin "3") (pinfunction "3_3") (pintype "passive"))
    )
    (net (code "160") (name "unconnected-(J3-Pad4)") (class "Default")
      (node (ref "J3") (pin "4") (pinfunction "4_4") (pintype "passive"))
    )
    (net (code "161") (name "unconnected-(J3-Pad5)") (class "Default")
      (node (ref "J3") (pin "5") (pinfunction "5_5") (pintype "passive"))
    )
    (net (code "162") (name "unconnected-(J3-Pad6)") (class "Default")
      (node (ref "J3") (pin "6") (pinfunction "6_6") (pintype "passive"))
    )
    (net (code "163") (name "unconnected-(J3-Pad7)") (class "Default")
      (node (ref "J3") (pin "7") (pinfunction "7_7") (pintype "passive"))
    )
    (net (code "164") (name "unconnected-(J3-Pad8)") (class "Default")
      (node (ref "J3") (pin "8") (pinfunction "8_8") (pintype "passive"))
    )
    (net (code "165") (name "unconnected-(J3-Pad9)") (class "Default")
      (node (ref "J3") (pin "9") (pinfunction "9_9") (pintype "passive"))
    )
    (net (code "166") (name "unconnected-(J3-Pad10)") (class "Default")
      (node (ref "J3") (pin "10") (pinfunction "10_10") (pintype "passive"))
    )
    (net (code "167") (name "unconnected-(J3-Pad12)") (class "Default")
      (node (ref "J3") (pin "12") (pinfunction "12_12") (pintype "passive"))
    )
    (net (code "168") (name "unconnected-(J3-Pad14)") (class "Default")
      (node (ref "J3") (pin "14") (pinfunction "14_14") (pintype "passive"))
    )
    (net (code "169") (name "unconnected-(J3-Pad16)") (class "Default")
      (node (ref "J3") (pin "16") (pinfunction "16_16") (pintype "passive"))
    )
    (net (code "170") (name "unconnected-(J3-Pad18)") (class "Default")
      (node (ref "J3") (pin "18") (pinfunction "18_18") (pintype "passive"))
    )
    (net (code "171") (name "unconnected-(J3-Pad20)") (class "Default")
      (node (ref "J3") (pin "20") (pinfunction "20_20") (pintype "passive"))
    )
    (net (code "172") (name "unconnected-(J3-Pad22)") (class "Default")
      (node (ref "J3") (pin "22") (pinfunction "22_22") (pintype "passive"))
    )
    (net (code "173") (name "unconnected-(J3-Pad23)") (class "Default")
      (node (ref "J3") (pin "23") (pinfunction "23_23") (pintype "passive"))
    )
    (net (code "174") (name "unconnected-(J3-Pad24)") (class "Default")
      (node (ref "J3") (pin "24") (pinfunction "24_24") (pintype "passive"))
    )
    (net (code "175") (name "unconnected-(J3-Pad25)") (class "Default")
      (node (ref "J3") (pin "25") (pinfunction "25_25") (pintype "passive"))
    )
    (net (code "176") (name "unconnected-(J3-Pad26)") (class "Default")
      (node (ref "J3") (pin "26") (pinfunction "26_26") (pintype "passive"))
    )
    (net (code "177") (name "unconnected-(J6-Pad9)") (class "Default")
      (node (ref "J6") (pin "9") (pinfunction "9_9") (pintype "passive"))
    )
    (net (code "178") (name "unconnected-(J6-Pad10)") (class "Default")
      (node (ref "J6") (pin "10") (pinfunction "10_10") (pintype "passive"))
    )
    (net (code "179") (name "unconnected-(J6-Pad11)") (class "Default")
      (node (ref "J6") (pin "11") (pinfunction "11_11") (pintype "passive"))
    )
    (net (code "180") (name "unconnected-(J6-Pad12)") (class "Default")
      (node (ref "J6") (pin "12") (pinfunction "12_12") (pintype "passive"))
    )
    (net (code "181") (name "unconnected-(J6-Pad13)") (class "Default")
      (node (ref "J6") (pin "13") (pinfunction "13_13") (pintype "passive"))
    )
    (net (code "182") (name "unconnected-(J6-Pad14)") (class "Default")
      (node (ref "J6") (pin "14") (pinfunction "14_14") (pintype "passive"))
    )
    (net (code "183") (name "unconnected-(J6-Pad15)") (class "Default")
      (node (ref "J6") (pin "15") (pinfunction "15_15") (pintype "passive"))
    )
    (net (code "184") (name "unconnected-(J6-Pad16)") (class "Default")
      (node (ref "J6") (pin "16") (pinfunction "16_16") (pintype "passive"))
    )
    (net (code "185") (name "unconnected-(J6-Pad17)") (class "Default")
      (node (ref "J6") (pin "17") (pinfunction "17_17") (pintype "passive"))
    )
    (net (code "186") (name "unconnected-(J6-Pad18)") (class "Default")
      (node (ref "J6") (pin "18") (pinfunction "18_18") (pintype "passive"))
    )
    (net (code "187") (name "unconnected-(J6-Pad19)") (class "Default")
      (node (ref "J6") (pin "19") (pinfunction "19_19") (pintype "passive"))
    )
    (net (code "188") (name "unconnected-(J6-Pad20)") (class "Default")
      (node (ref "J6") (pin "20") (pinfunction "20_20") (pintype "passive"))
    )
    (net (code "189") (name "unconnected-(J6-Pad22)") (class "Default")
      (node (ref "J6") (pin "22") (pinfunction "22_22") (pintype "passive"))
    )
    (net (code "190") (name "unconnected-(J6-Pad24)") (class "Default")
      (node (ref "J6") (pin "24") (pinfunction "24_24") (pintype "passive"))
    )
    (net (code "191") (name "unconnected-(J6-Pad26)") (class "Default")
      (node (ref "J6") (pin "26") (pinfunction "26_26") (pintype "passive"))
    )
    (net (code "192") (name "unconnected-(J6-Pad28)") (class "Default")
      (node (ref "J6") (pin "28") (pinfunction "28_28") (pintype "passive"))
    )
    (net (code "193") (name "unconnected-(MCU-P00{slash}D0{slash}AN10-Pad86)") (class "Default")
      (node (ref "MCU") (pin "86") (pinfunction "P00/D0/AN10_86") (pintype "bidirectional"))
    )
    (net (code "194") (name "unconnected-(MCU-P01{slash}D1{slash}AN11-Pad85)") (class "Default")
      (node (ref "MCU") (pin "85") (pinfunction "P01/D1/AN11_85") (pintype "bidirectional"))
    )
    (net (code "195") (name "unconnected-(MCU-P02{slash}D2{slash}AN12-Pad84)") (class "Default")
      (node (ref "MCU") (pin "84") (pinfunction "P02/D2/AN12_84") (pintype "bidirectional"))
    )
    (net (code "196") (name "unconnected-(MCU-P03{slash}D3{slash}AN13-Pad83)") (class "Default")
      (node (ref "MCU") (pin "83") (pinfunction "P03/D3/AN13_83") (pintype "bidirectional"))
    )
    (net (code "197") (name "unconnected-(MCU-P04{slash}D4{slash}AN14-Pad82)") (class "Default")
      (node (ref "MCU") (pin "82") (pinfunction "P04/D4/AN14_82") (pintype "bidirectional"))
    )
    (net (code "198") (name "unconnected-(MCU-P05{slash}D5{slash}AN15-Pad81)") (class "Default")
      (node (ref "MCU") (pin "81") (pinfunction "P05/D5/AN15_81") (pintype "bidirectional"))
    )
    (net (code "199") (name "unconnected-(MCU-P06{slash}D6{slash}AN16-Pad80)") (class "Default")
      (node (ref "MCU") (pin "80") (pinfunction "P06/D6/AN16_80") (pintype "bidirectional"))
    )
    (net (code "200") (name "unconnected-(MCU-P07{slash}D7{slash}AN17-Pad79)") (class "Default")
      (node (ref "MCU") (pin "79") (pinfunction "P07/D7/AN17_79") (pintype "bidirectional"))
    )
    (net (code "201") (name "unconnected-(MCU-P10{slash}D8{slash}IIO00(10)-Pad78)") (class "Default")
      (node (ref "MCU") (pin "78") (pinfunction "P10/D8/IIO00(10)_78") (pintype "bidirectional"))
    )
    (net (code "202") (name "unconnected-(MCU-P11{slash}D9{slash}IIO01(11)-Pad77)") (class "Default")
      (node (ref "MCU") (pin "77") (pinfunction "P11/D9/IIO01(11)_77") (pintype "bidirectional"))
    )
    (net (code "203") (name "unconnected-(MCU-P31{slash}A9{slash}[A9{slash}D9]-Pad59)") (class "Default")
      (node (ref "MCU") (pin "59") (pinfunction "P31/A9/[A9/D9]_59") (pintype "bidirectional"))
    )
    (net (code "204") (name "unconnected-(MCU-P52{slash}RD-Pad42)") (class "Default")
      (node (ref "MCU") (pin "42") (pinfunction "P52/RD_42") (pintype "bidirectional"))
    )
    (net (code "205") (name "unconnected-(MCU-P74{slash}TA2OUT{slash}W{slash}CLK8-Pad24)") (class "Default")
      (node (ref "MCU") (pin "24") (pinfunction "P74/TA2OUT/W/CLK8_24") (pintype "bidirectional"))
    )
    (net (code "206") (name "unconnected-(MCU-P81{slash}TA4IN{slash}U{slash}CTS5-Pad19)") (class "Default")
      (node (ref "MCU") (pin "19") (pinfunction "P81/TA4IN/U/CTS5_19") (pintype "bidirectional"))
    )
    (net (code "207") (name "unconnected-(MCU-P91-Pad4)") (class "Default")
      (node (ref "MCU") (pin "4") (pinfunction "P91_4") (pintype "bidirectional"))
    )
    (net (code "208") (name "unconnected-(MCU-P93{slash}DA0{slash}TB3IN-Pad2)") (class "Default")
      (node (ref "MCU") (pin "2") (pinfunction "P93/DA0/TB3IN_2") (pintype "bidirectional"))
    )
    (net (code "209") (name "unconnected-(MCU-P104{slash}AN04{slash}KL0-Pad90)") (class "Default")
      (node (ref "MCU") (pin "90") (pinfunction "P104/AN04/KL0_90") (pintype "bidirectional"))
    )
    (net (code "210") (name "unconnected-(MCU-P105{slash}AN05{slash}KL1-Pad89)") (class "Default")
      (node (ref "MCU") (pin "89") (pinfunction "P105/AN05/KL1_89") (pintype "bidirectional"))
    )
    (net (code "211") (name "unconnected-(MCU-P106{slash}AN06{slash}KL2-Pad88)") (class "Default")
      (node (ref "MCU") (pin "88") (pinfunction "P106/AN06/KL2_88") (pintype "bidirectional"))
    )
    (net (code "212") (name "unconnected-(MCU-P107{slash}AN07{slash}KL3-Pad87)") (class "Default")
      (node (ref "MCU") (pin "87") (pinfunction "P107/AN07/KL3_87") (pintype "bidirectional"))
    )
    (net (code "213") (name "unconnected-(U$5-INT2-Pad9)") (class "Default")
      (node (ref "U$5") (pin "9") (pinfunction "INT2_9") (pintype "bidirectional"))
    )
    (net (code "214") (name "unconnected-(U$6-INT2-Pad9)") (class "Default")
      (node (ref "U$6") (pin "9") (pinfunction "INT2_9") (pintype "bidirectional"))
    )
    (net (code "215") (name "unconnected-(U1-A7-Pad8)") (class "Default")
      (node (ref "U1") (pin "8") (pinfunction "A7_8") (pintype "bidirectional"))
    )
    (net (code "216") (name "unconnected-(U1-A8-Pad9)") (class "Default")
      (node (ref "U1") (pin "9") (pinfunction "A8_9") (pintype "bidirectional"))
    )
    (net (code "217") (name "unconnected-(U1-B7-Pad13)") (class "Default")
      (node (ref "U1") (pin "13") (pinfunction "B7_13") (pintype "bidirectional"))
    )
    (net (code "218") (name "unconnected-(U1-B8-Pad12)") (class "Default")
      (node (ref "U1") (pin "12") (pinfunction "B8_12") (pintype "bidirectional"))
    )
  )
)
